# Mini_VFD_RevA.net
KiCad netlist of a schematic drawn in EAGLE
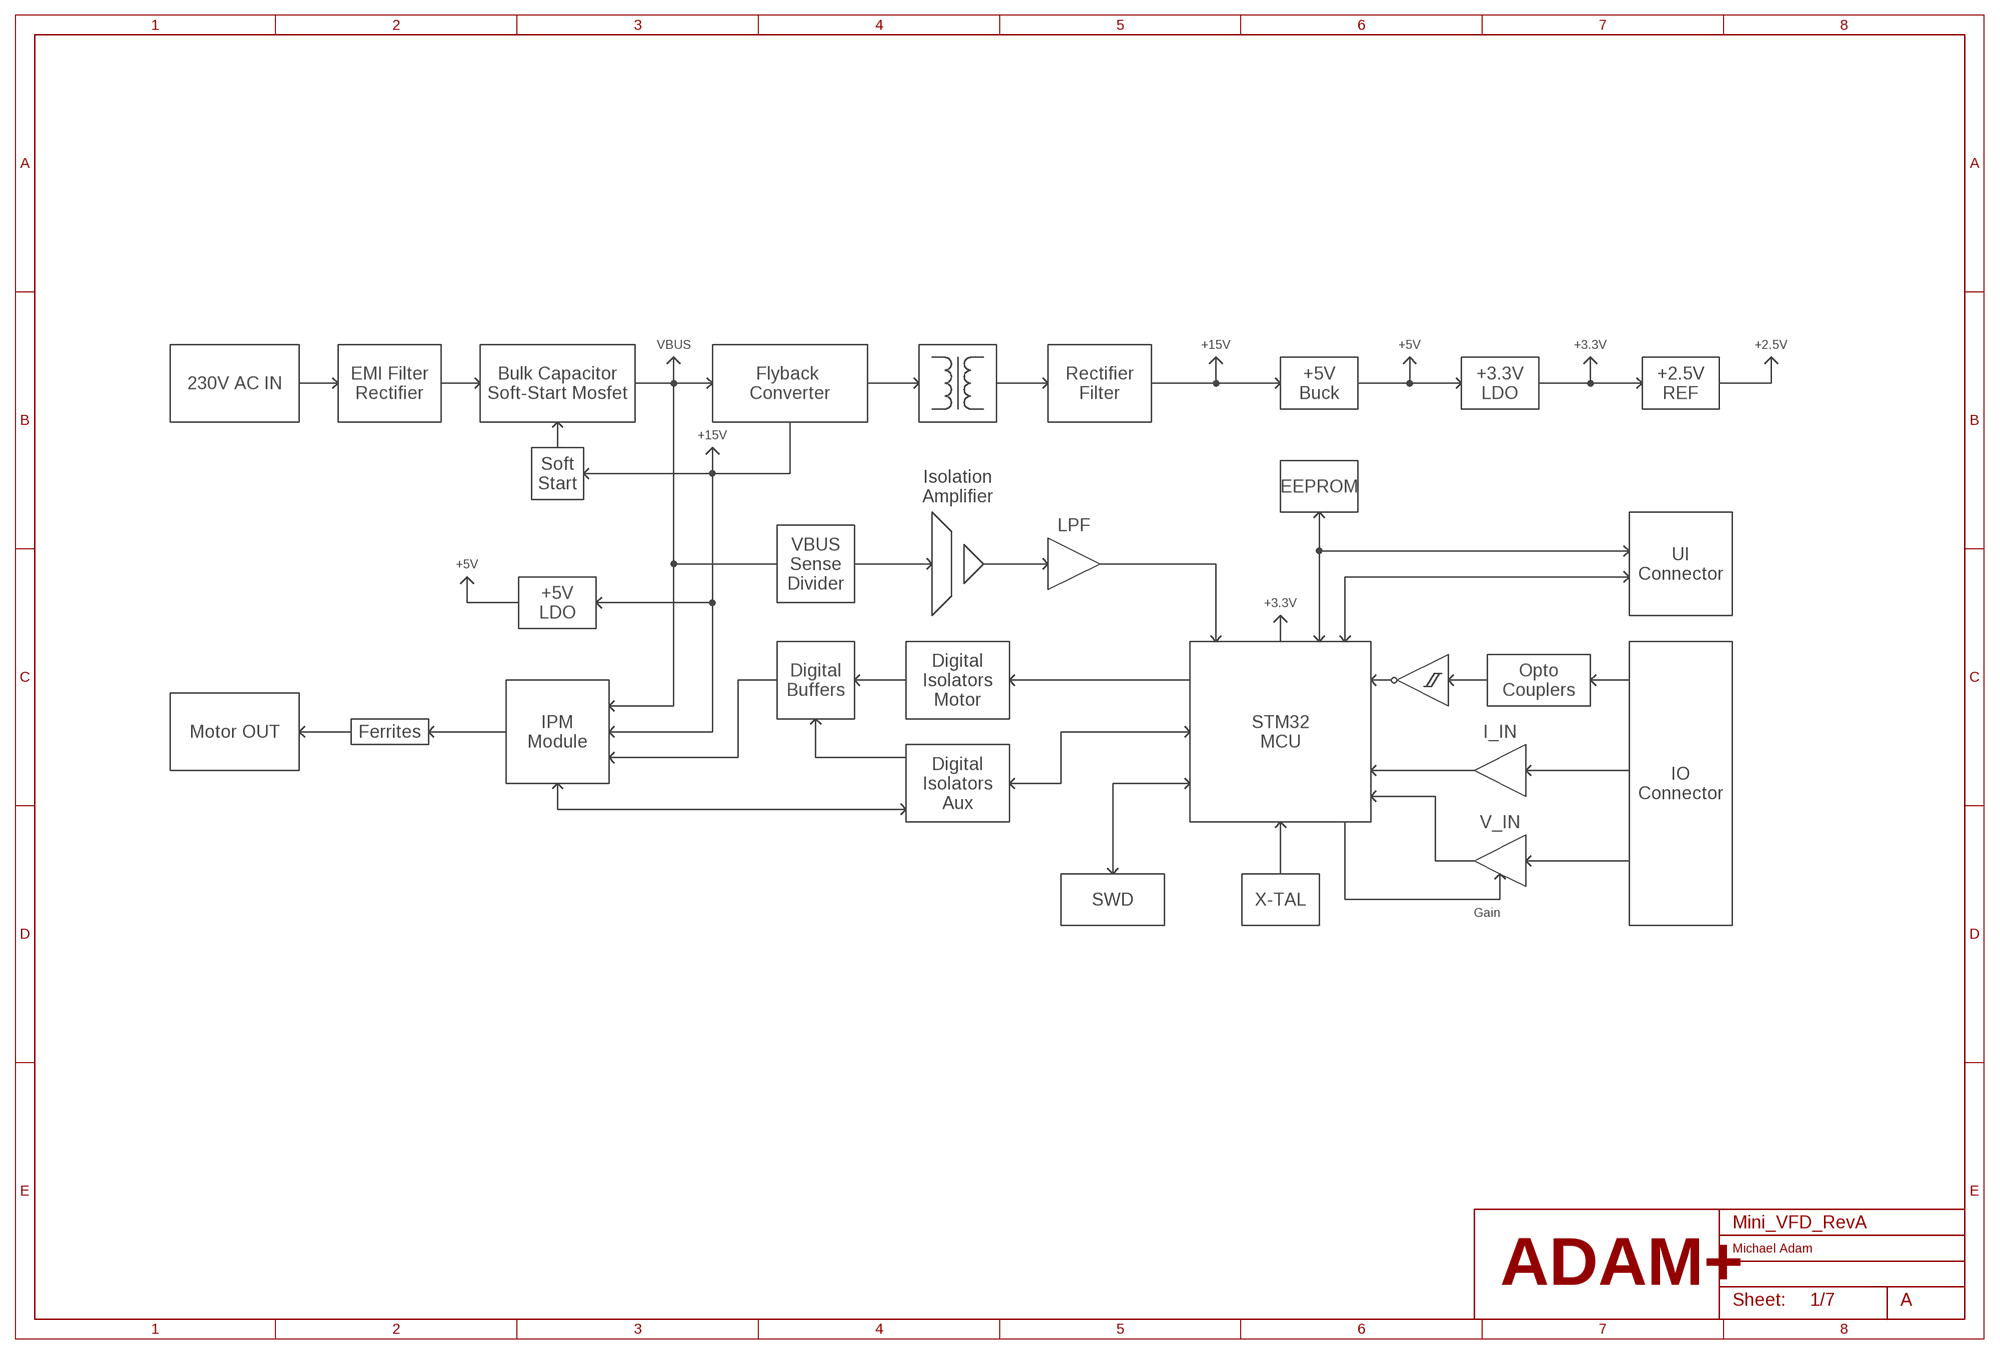
[diagram p0: schematic, sheet 1]
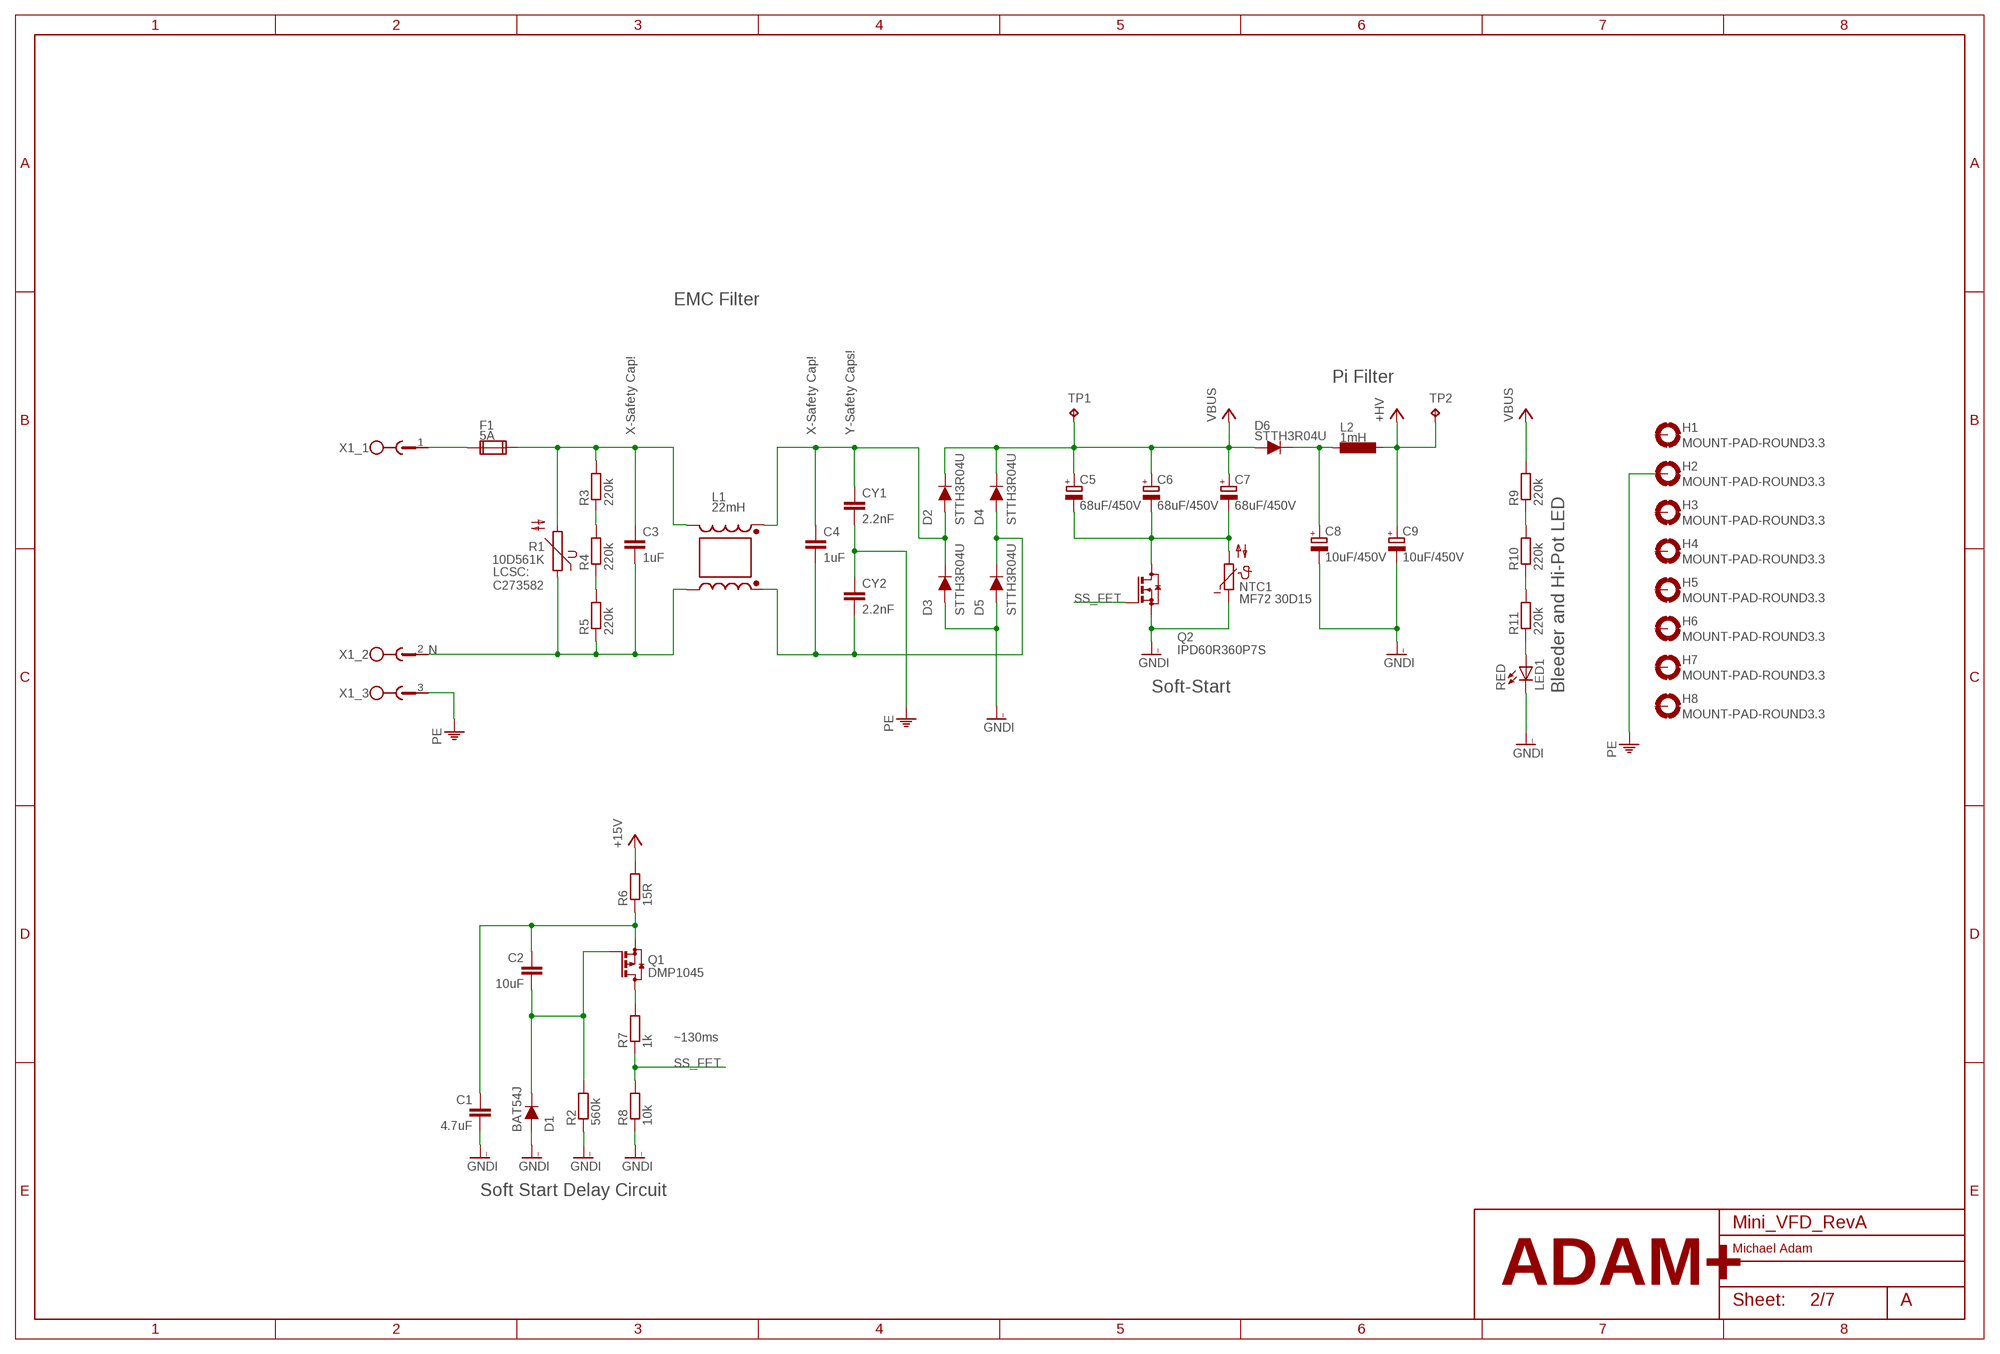
[diagram p1: schematic, sheet 2]
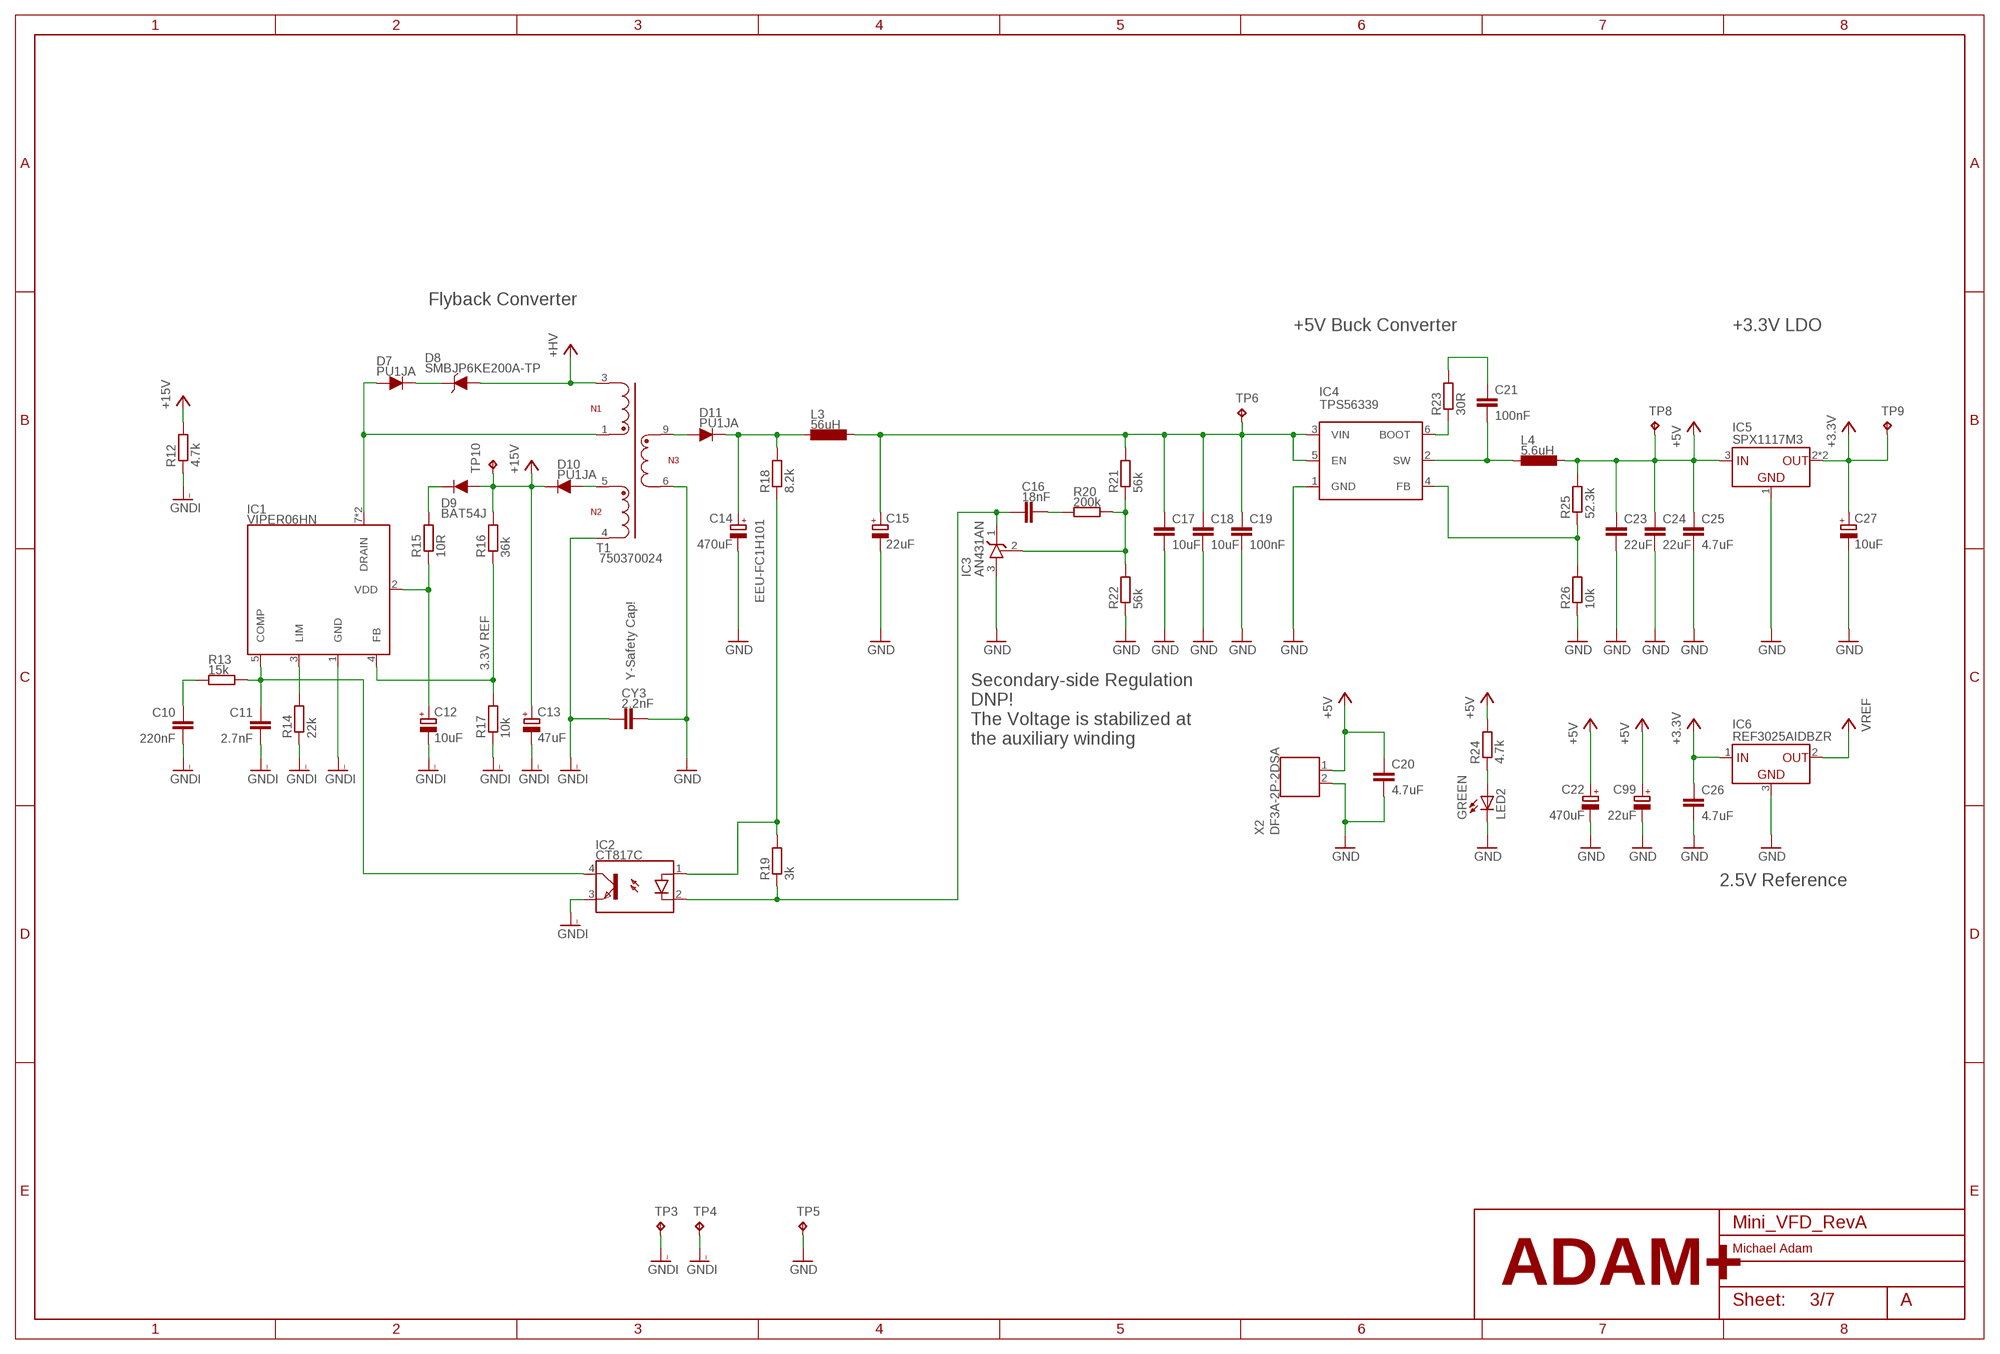
[diagram p2: schematic, sheet 3]
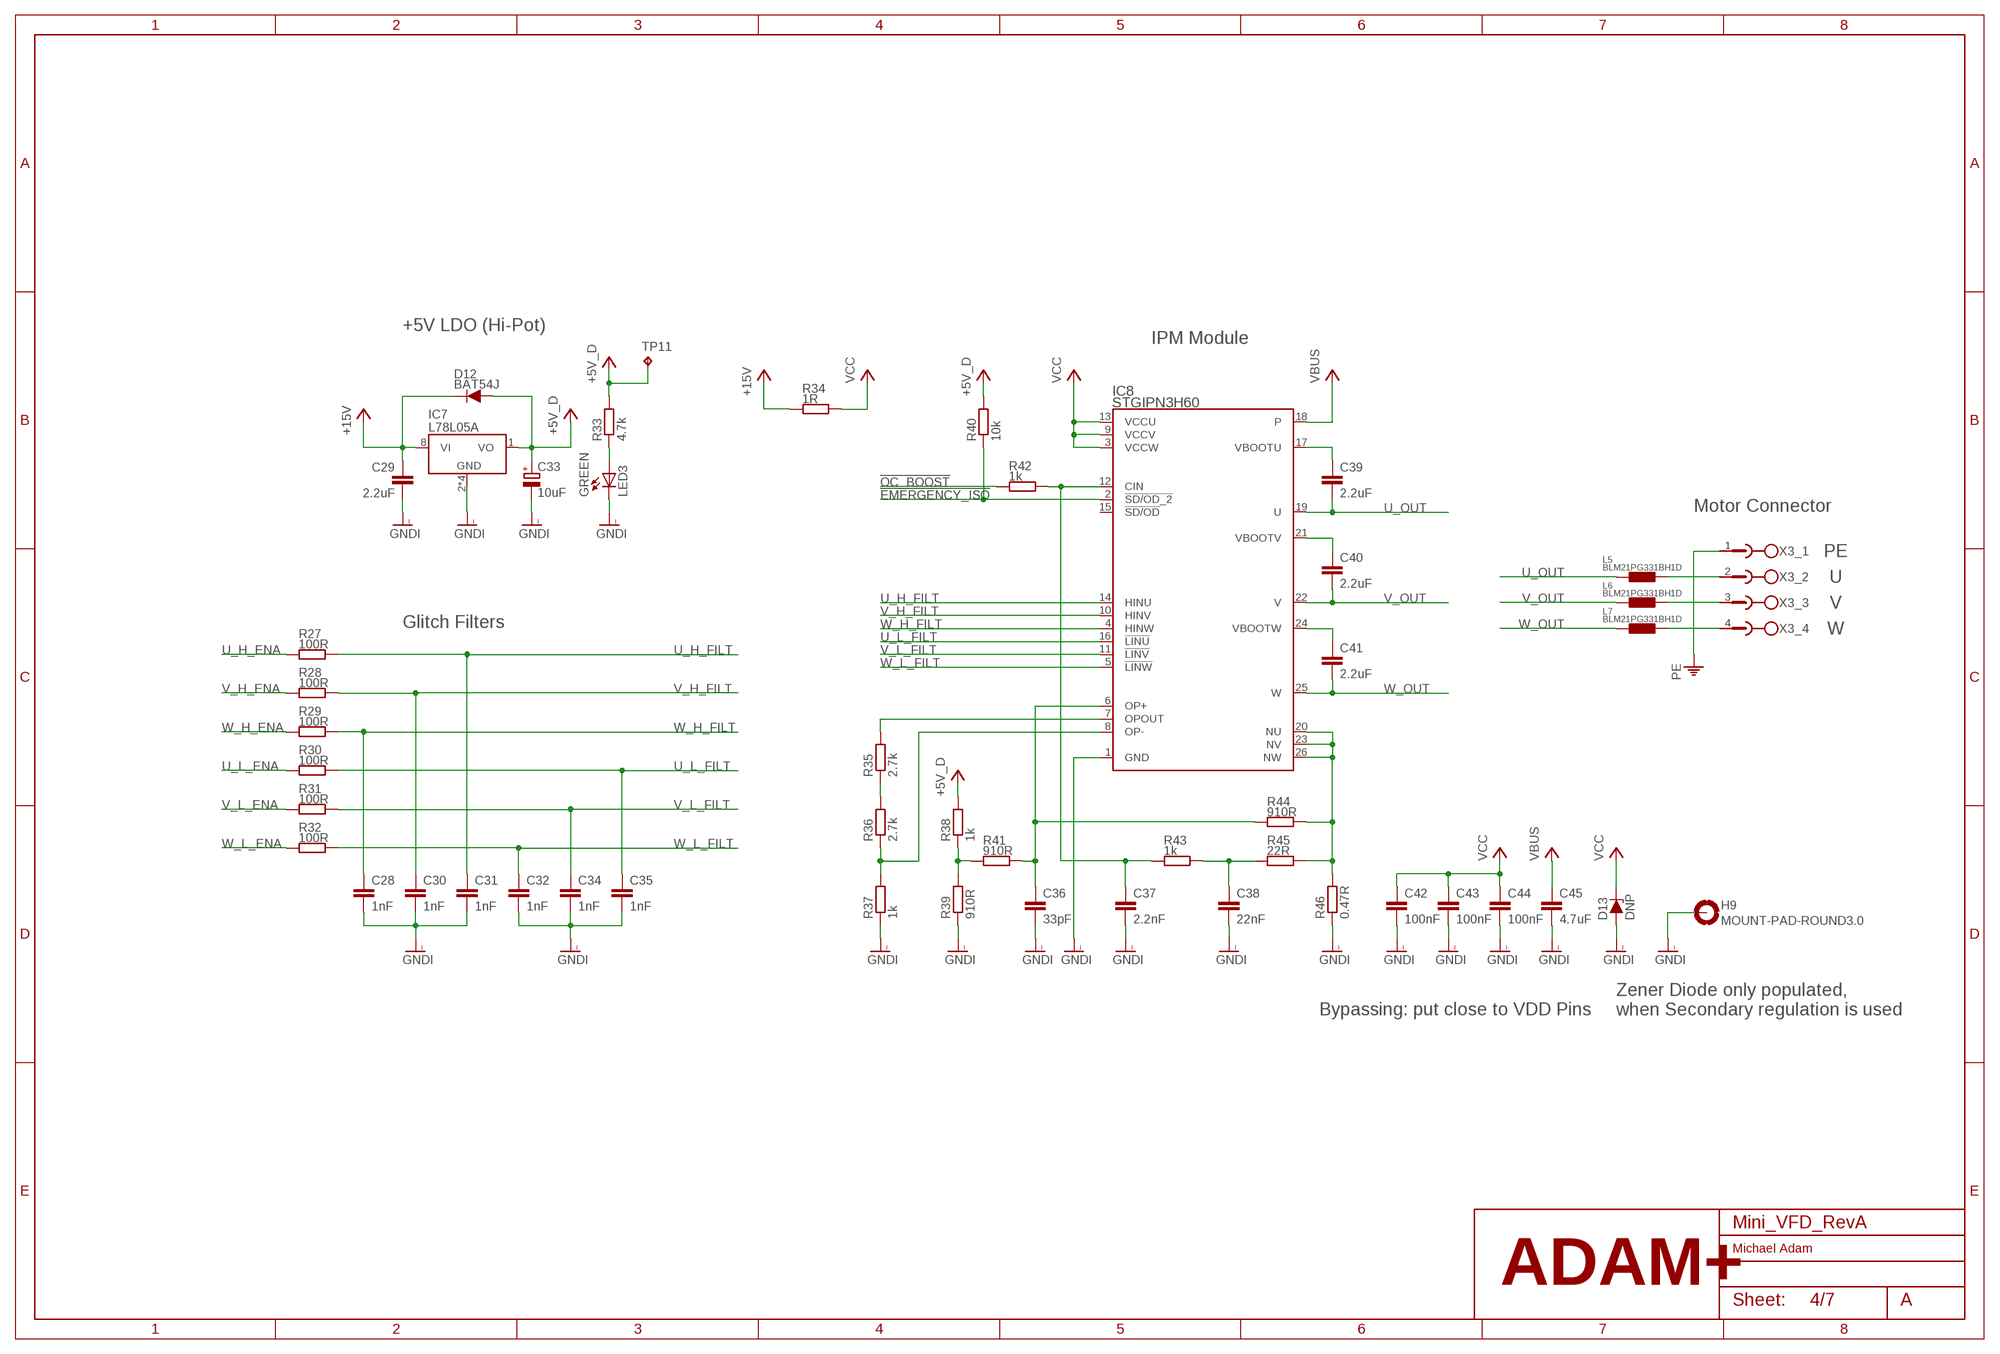
[diagram p3: schematic, sheet 4]
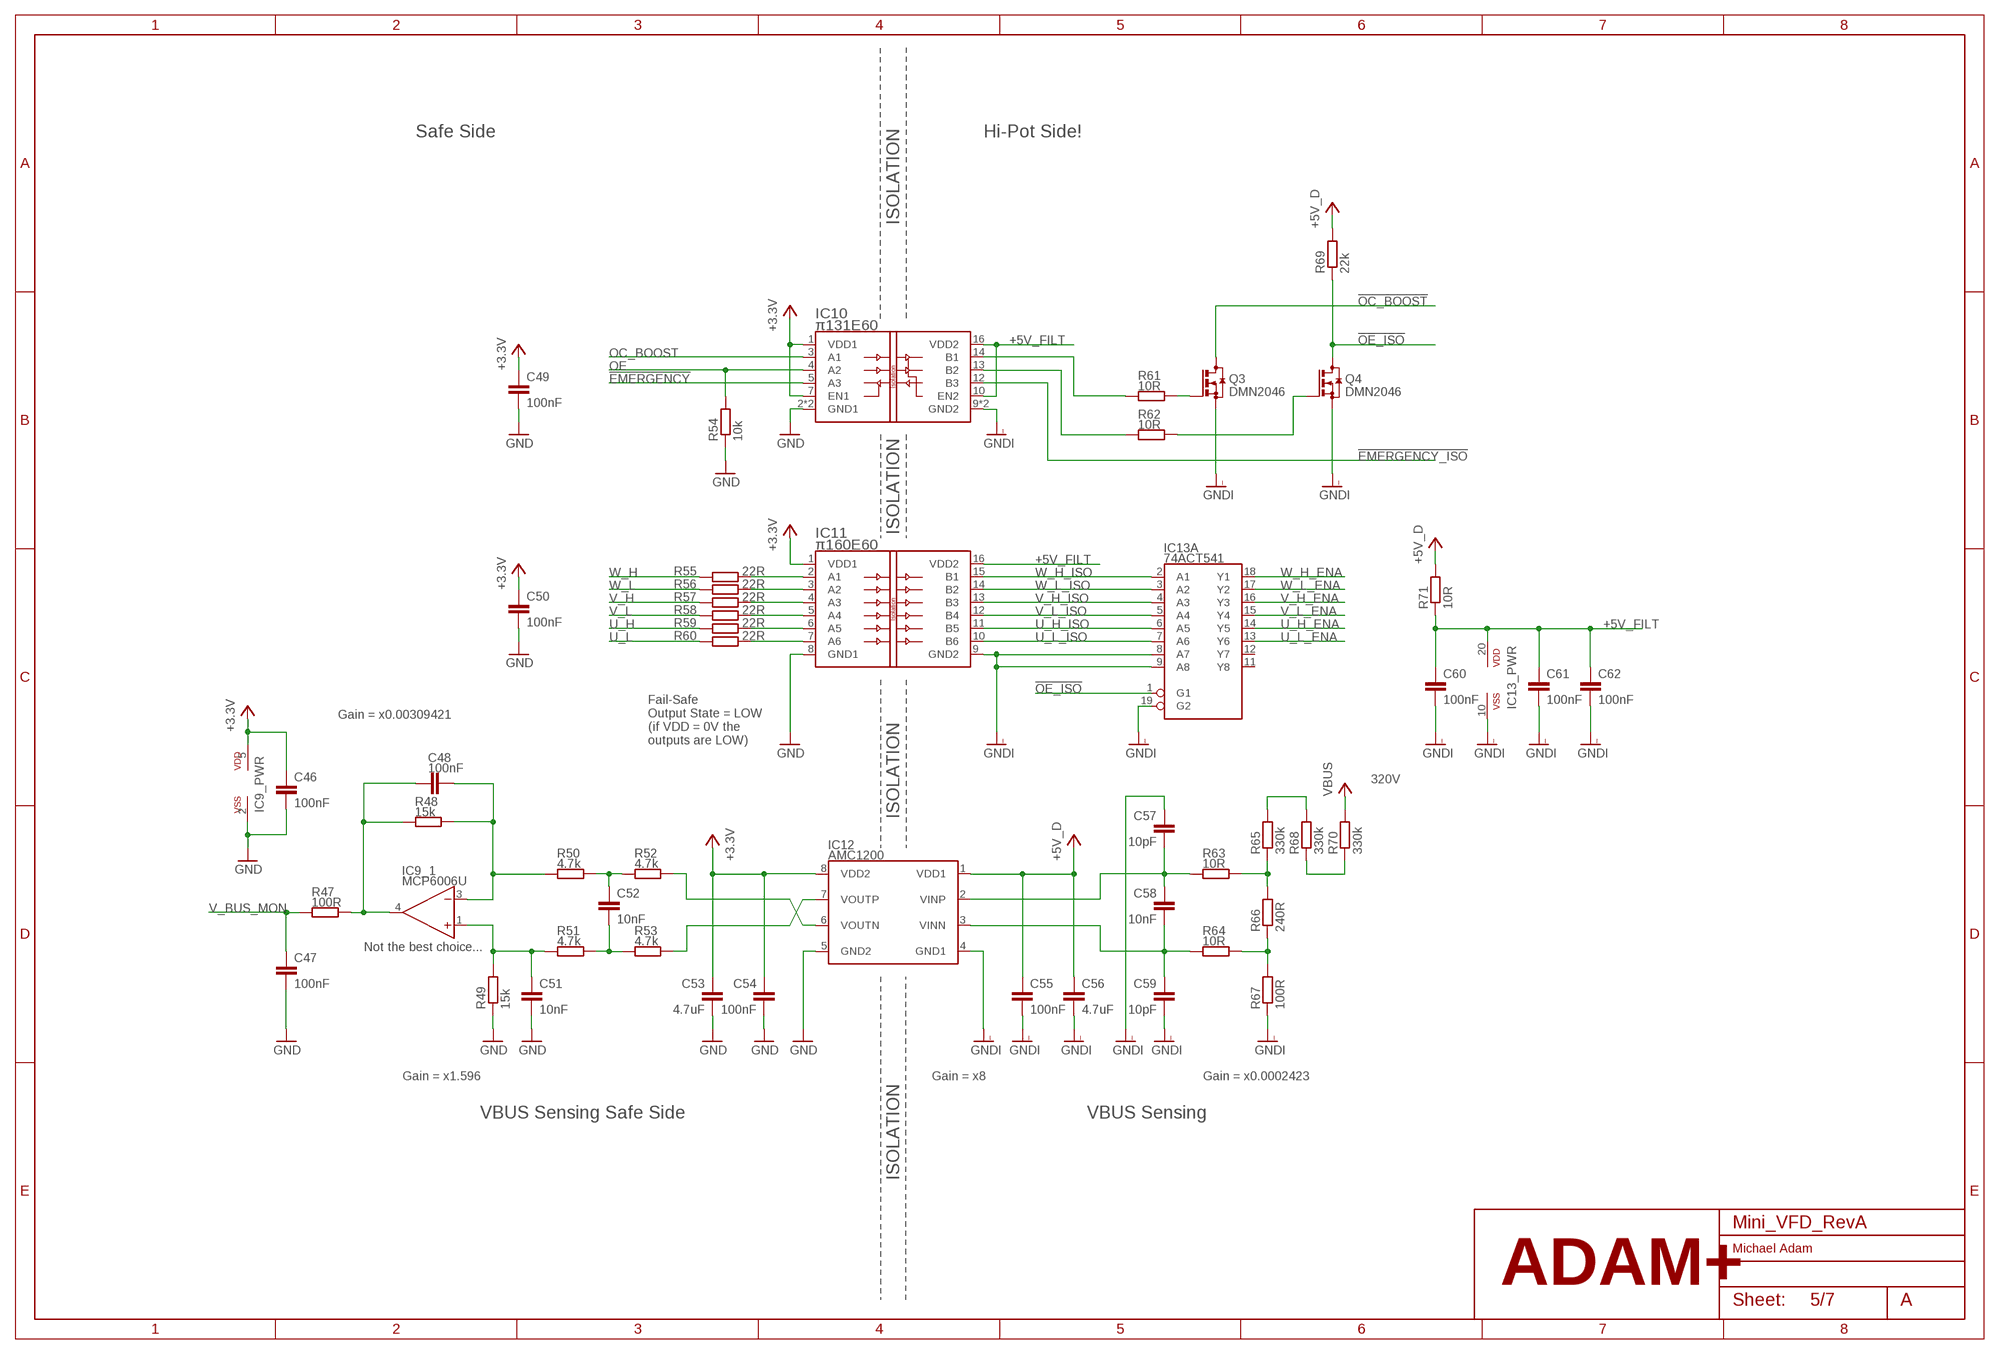
[diagram p4: schematic, sheet 5]
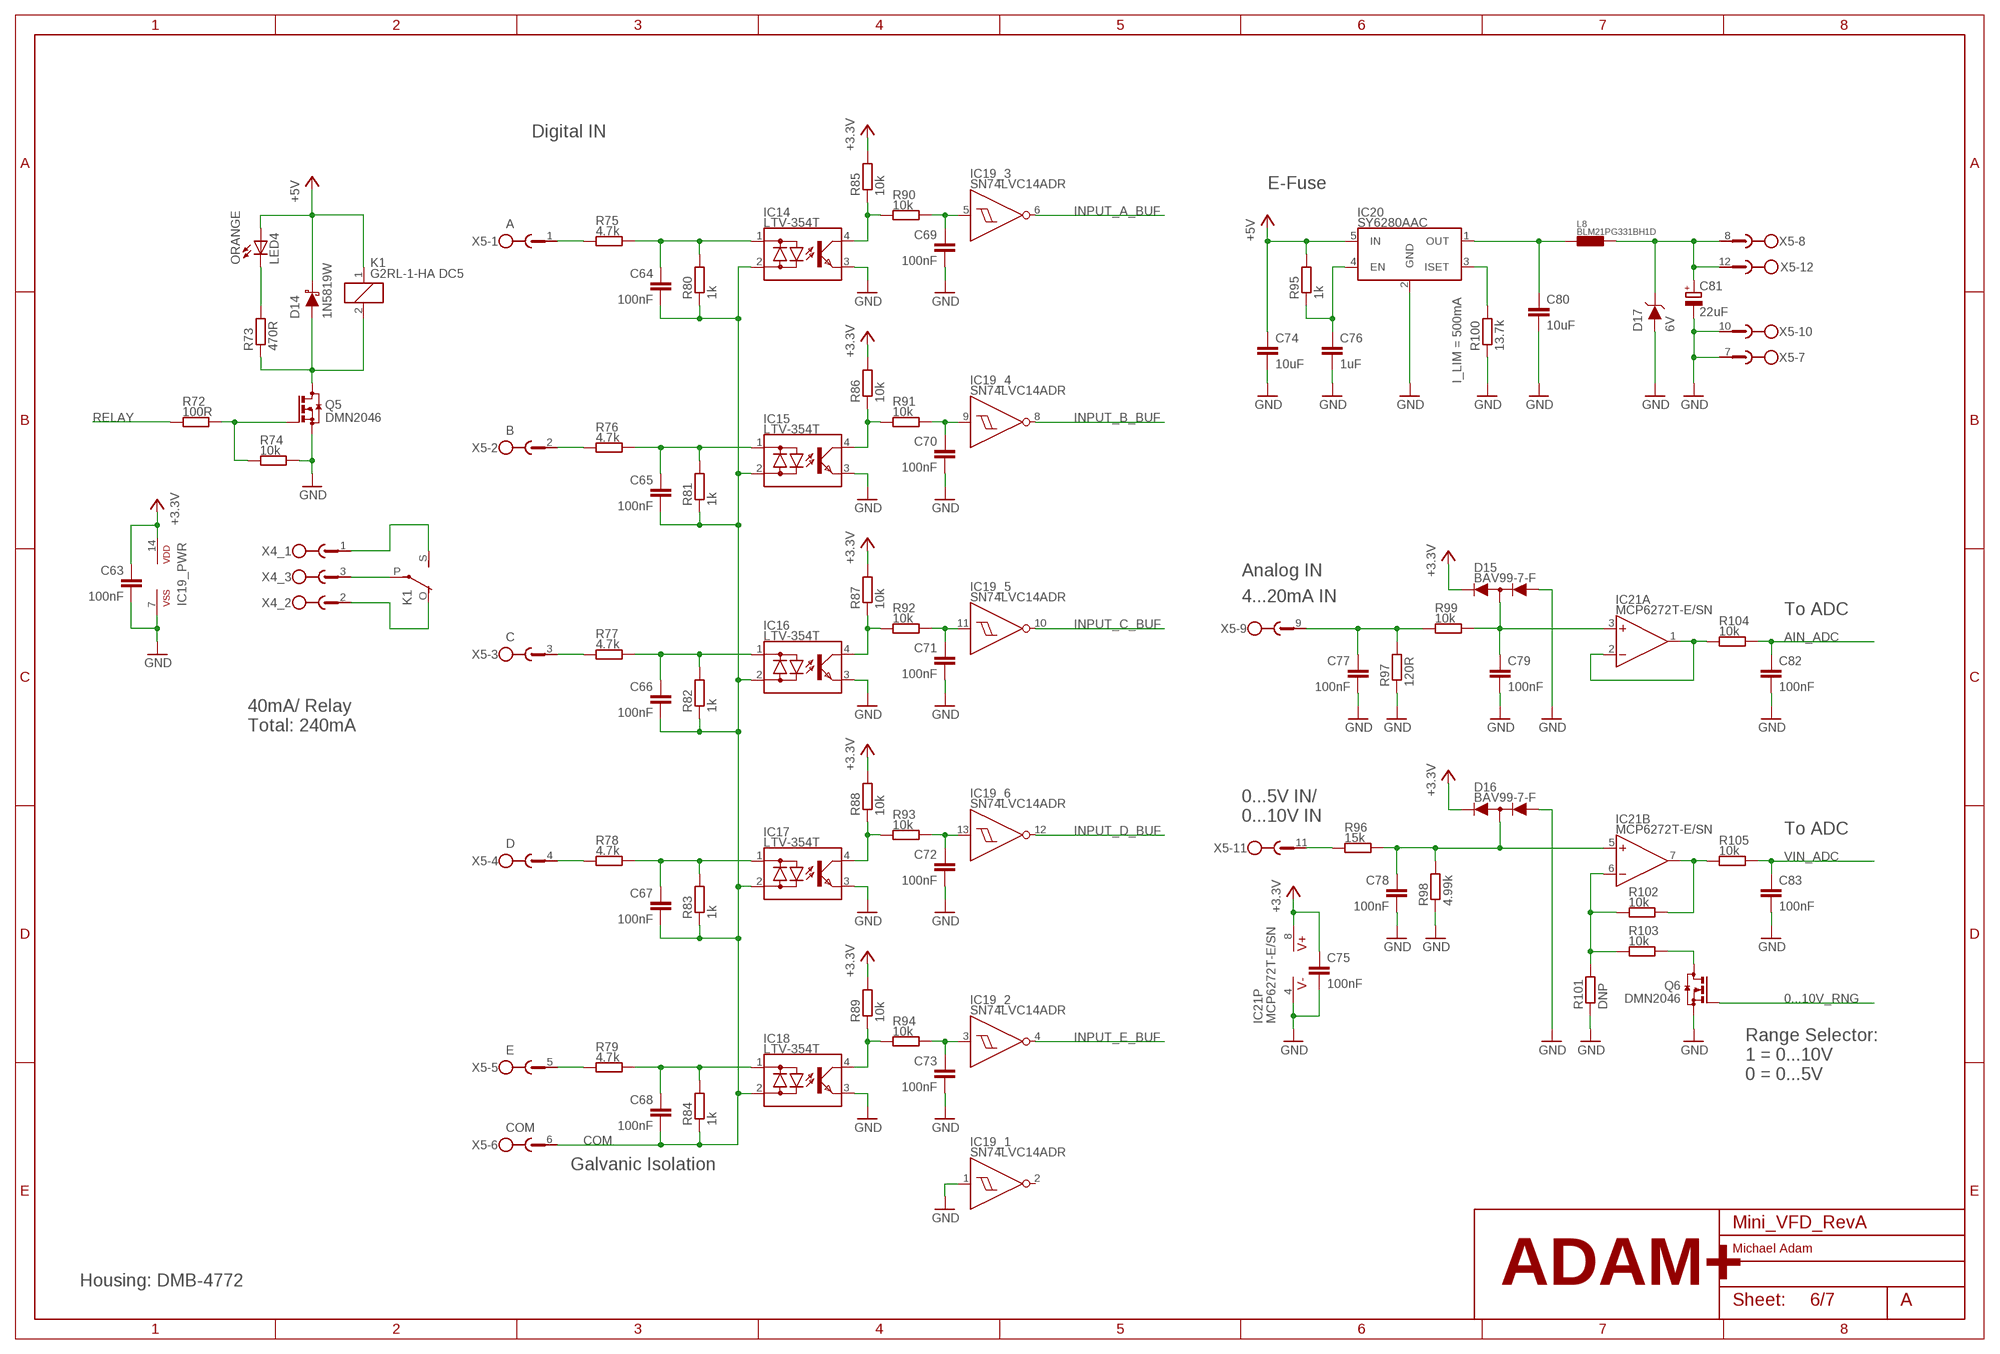
[diagram p5: schematic, sheet 6]
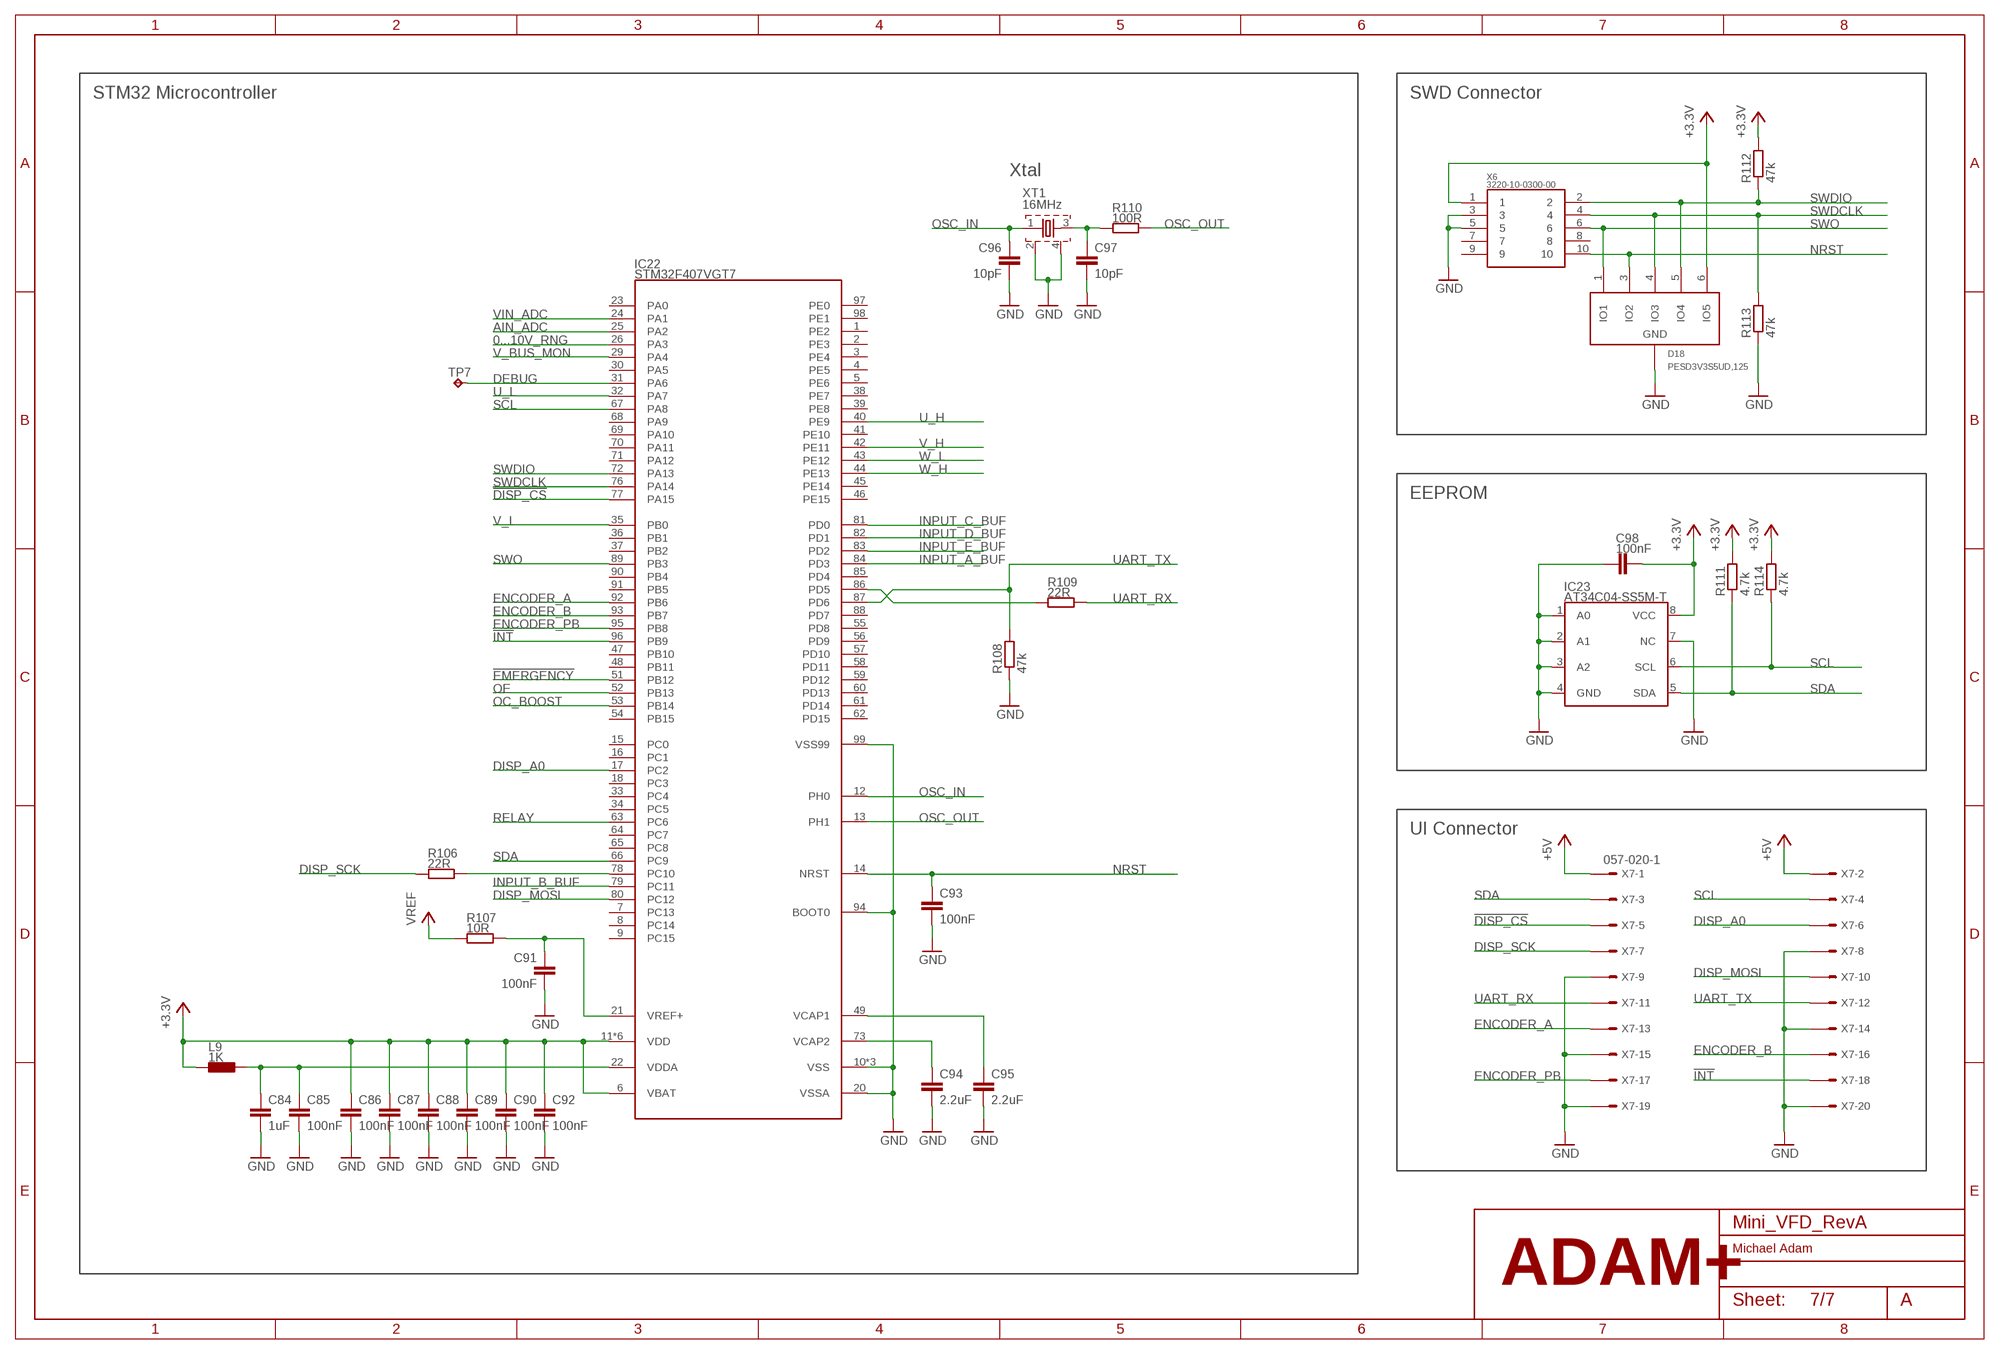
[diagram p6: schematic, sheet 7]

(export (version "E")
  (design (tool "Eeschema 10.0.6"))
  (components
    (comp (ref "C1")
      (value "4.7uF")
      (footprint "eagle-import:C0805")
      (libsource (lib "eagle-import") (part "C-EUC0805"))
    )
    (comp (ref "C2")
      (value "10uF")
      (footprint "eagle-import:C0805")
      (libsource (lib "eagle-import") (part "C-EUC0805"))
    )
    (comp (ref "C3")
      (value "1uF")
      (footprint "eagle-import:C102-082X133")
      (libsource (lib "eagle-import") (part "C-EU102-082X133"))
    )
    (comp (ref "C4")
      (value "1uF")
      (footprint "eagle-import:C102-082X133")
      (libsource (lib "eagle-import") (part "C-EU102-082X133"))
    )
    (comp (ref "C5")
      (value "68uF/450V")
      (footprint "eagle-import:E7,5-18")
      (libsource (lib "eagle-import") (part "CPOL-EUE7.5-18"))
    )
    (comp (ref "C6")
      (value "68uF/450V")
      (footprint "eagle-import:E7,5-18")
      (libsource (lib "eagle-import") (part "CPOL-EUE7.5-18"))
    )
    (comp (ref "C7")
      (value "68uF/450V")
      (footprint "eagle-import:E7,5-18")
      (libsource (lib "eagle-import") (part "CPOL-EUE7.5-18"))
    )
    (comp (ref "C8")
      (value "10uF/450V")
      (footprint "eagle-import:E5-10,5")
      (libsource (lib "eagle-import") (part "CPOL-EUE5-10.5"))
    )
    (comp (ref "C9")
      (value "10uF/450V")
      (footprint "eagle-import:E5-10,5")
      (libsource (lib "eagle-import") (part "CPOL-EUE5-10.5"))
    )
    (comp (ref "CY1")
      (value "2.2nF")
      (footprint "eagle-import:YC7B5")
      (libsource (lib "eagle-import") (part "CYYC7B5"))
    )
    (comp (ref "CY2")
      (value "2.2nF")
      (footprint "eagle-import:YC7B5")
      (libsource (lib "eagle-import") (part "CYYC7B5"))
    )
    (comp (ref "D1")
      (value "BAT54J")
      (footprint "eagle-import:SOD123")
      (libsource (lib "eagle-import") (part "DIODE"))
    )
    (comp (ref "D2")
      (value "STTH3R04U")
      (footprint "eagle-import:SMB")
      (libsource (lib "eagle-import") (part "DIODESMB"))
    )
    (comp (ref "D3")
      (value "STTH3R04U")
      (footprint "eagle-import:SMB")
      (libsource (lib "eagle-import") (part "DIODESMB"))
    )
    (comp (ref "D4")
      (value "STTH3R04U")
      (footprint "eagle-import:SMB")
      (libsource (lib "eagle-import") (part "DIODESMB"))
    )
    (comp (ref "D5")
      (value "STTH3R04U")
      (footprint "eagle-import:SMB")
      (libsource (lib "eagle-import") (part "DIODESMB"))
    )
    (comp (ref "D6")
      (value "STTH3R04U")
      (footprint "eagle-import:SMB")
      (libsource (lib "eagle-import") (part "DIODESMB"))
    )
    (comp (ref "F1")
      (value "5A")
      (footprint "eagle-import:SH25")
      (libsource (lib "eagle-import") (part "FUSESH25"))
    )
    (comp (ref "H1")
      (value "MOUNT-PAD-ROUND3.3")
      (footprint "eagle-import:3,3-PAD")
      (libsource (lib "eagle-import") (part "MOUNT-PAD-ROUND3.3"))
    )
    (comp (ref "H2")
      (value "MOUNT-PAD-ROUND3.3")
      (footprint "eagle-import:3,3-PAD")
      (libsource (lib "eagle-import") (part "MOUNT-PAD-ROUND3.3"))
    )
    (comp (ref "H3")
      (value "MOUNT-PAD-ROUND3.3")
      (footprint "eagle-import:3,3-PAD")
      (libsource (lib "eagle-import") (part "MOUNT-PAD-ROUND3.3"))
    )
    (comp (ref "H4")
      (value "MOUNT-PAD-ROUND3.3")
      (footprint "eagle-import:3,3-PAD")
      (libsource (lib "eagle-import") (part "MOUNT-PAD-ROUND3.3"))
    )
    (comp (ref "H5")
      (value "MOUNT-PAD-ROUND3.3")
      (footprint "eagle-import:3,3-PAD")
      (libsource (lib "eagle-import") (part "MOUNT-PAD-ROUND3.3"))
    )
    (comp (ref "H6")
      (value "MOUNT-PAD-ROUND3.3")
      (footprint "eagle-import:3,3-PAD")
      (libsource (lib "eagle-import") (part "MOUNT-PAD-ROUND3.3"))
    )
    (comp (ref "H7")
      (value "MOUNT-PAD-ROUND3.3")
      (footprint "eagle-import:3,3-PAD")
      (libsource (lib "eagle-import") (part "MOUNT-PAD-ROUND3.3"))
    )
    (comp (ref "H8")
      (value "MOUNT-PAD-ROUND3.3")
      (footprint "eagle-import:3,3-PAD")
      (libsource (lib "eagle-import") (part "MOUNT-PAD-ROUND3.3"))
    )
    (comp (ref "L1")
      (value "22mH")
      (footprint "eagle-import:CMC_PDMCAT18107")
      (libsource (lib "eagle-import") (part "COMMON_MODE_CHOKE_XRT16128B-223VFRL6"))
    )
    (comp (ref "L2")
      (value "1mH")
      (footprint "eagle-import:SLH0704")
      (libsource (lib "eagle-import") (part "COIL_1MH"))
    )
    (comp (ref "LED1")
      (value "RED")
      (footprint "eagle-import:LED_0805")
      (libsource (lib "eagle-import") (part "LED_0805"))
    )
    (comp (ref "NTC1")
      (value "MF72 30D15")
      (footprint "eagle-import:MF72")
      (libsource (lib "eagle-import") (part "NTC"))
    )
    (comp (ref "Q1")
      (value "DMP1045")
      (footprint "eagle-import:SOT23")
      (libsource (lib "eagle-import") (part "PMOS"))
    )
    (comp (ref "Q2")
      (value "IPD60R360P7S")
      (footprint "eagle-import:TO252")
      (libsource (lib "eagle-import") (part "NMOS_IPD60R360P7S"))
    )
    (comp (ref "R1")
      (value "10D561K")
      (footprint "eagle-import:S10K175")
      (libsource (lib "eagle-import") (part "S10K175"))
    )
    (comp (ref "R2")
      (value "560k")
      (footprint "eagle-import:R0603")
      (libsource (lib "eagle-import") (part "rcl_MICHAEL (1)_R-EU_R0603"))
    )
    (comp (ref "R3")
      (value "220k")
      (footprint "eagle-import:R1206")
      (libsource (lib "eagle-import") (part "R-EU_R1206"))
    )
    (comp (ref "R4")
      (value "220k")
      (footprint "eagle-import:R1206")
      (libsource (lib "eagle-import") (part "R-EU_R1206"))
    )
    (comp (ref "R5")
      (value "220k")
      (footprint "eagle-import:R1206")
      (libsource (lib "eagle-import") (part "R-EU_R1206"))
    )
    (comp (ref "R6")
      (value "15R")
      (footprint "eagle-import:0207_10")
      (libsource (lib "eagle-import") (part "R-EU_0207/10"))
    )
    (comp (ref "R7")
      (value "1k")
      (footprint "eagle-import:R0603")
      (libsource (lib "eagle-import") (part "rcl_MICHAEL (1)_R-EU_R0603"))
    )
    (comp (ref "R8")
      (value "10k")
      (footprint "eagle-import:R0603")
      (libsource (lib "eagle-import") (part "rcl_MICHAEL (1)_R-EU_R0603"))
    )
    (comp (ref "R9")
      (value "220k")
      (footprint "eagle-import:R1206")
      (libsource (lib "eagle-import") (part "R-EU_R1206"))
    )
    (comp (ref "R10")
      (value "220k")
      (footprint "eagle-import:R1206")
      (libsource (lib "eagle-import") (part "R-EU_R1206"))
    )
    (comp (ref "R11")
      (value "220k")
      (footprint "eagle-import:R1206")
      (libsource (lib "eagle-import") (part "R-EU_R1206"))
    )
    (comp (ref "TP1")
      (value "TPTP10R")
      (footprint "eagle-import:TP10R")
      (libsource (lib "eagle-import") (part "TPTP10R"))
    )
    (comp (ref "TP2")
      (value "TPTP10R")
      (footprint "eagle-import:TP10R")
      (libsource (lib "eagle-import") (part "TPTP10R"))
    )
    (comp (ref "X1")
      (value "MSTBV3")
      (footprint "eagle-import:MSTBV3")
      (libsource (lib "eagle-import") (part "MSTBV3"))
    )
    (comp (ref "C10")
      (value "220nF")
      (footprint "eagle-import:C0603")
      (libsource (lib "eagle-import") (part "C-EUC0603"))
    )
    (comp (ref "C11")
      (value "2.7nF")
      (footprint "eagle-import:C0603")
      (libsource (lib "eagle-import") (part "C-EUC0603"))
    )
    (comp (ref "C12")
      (value "10uF")
      (footprint "eagle-import:E2,5-5")
      (libsource (lib "eagle-import") (part "CPOL-EUE2.5-5"))
    )
    (comp (ref "C13")
      (value "47uF")
      (footprint "eagle-import:E2,5-7")
      (libsource (lib "eagle-import") (part "CPOL-EUE2.5-7"))
    )
    (comp (ref "C14")
      (value "470uF")
      (footprint "eagle-import:E5-10,5")
      (libsource (lib "eagle-import") (part "CPOL-EUE5-10.5"))
    )
    (comp (ref "C15")
      (value "22uF")
      (footprint "eagle-import:E2-5")
      (libsource (lib "eagle-import") (part "CPOL-EUE2-5"))
    )
    (comp (ref "C16")
      (value "18nF")
      (footprint "eagle-import:C0603")
      (libsource (lib "eagle-import") (part "C-EUC0603"))
    )
    (comp (ref "C17")
      (value "10uF")
      (footprint "eagle-import:C1206")
      (libsource (lib "eagle-import") (part "C-EUC1206"))
    )
    (comp (ref "C18")
      (value "10uF")
      (footprint "eagle-import:C1206")
      (libsource (lib "eagle-import") (part "C-EUC1206"))
    )
    (comp (ref "C19")
      (value "100nF")
      (footprint "eagle-import:C0603")
      (libsource (lib "eagle-import") (part "C-EUC0603"))
    )
    (comp (ref "C20")
      (value "4.7uF")
      (footprint "eagle-import:C0805")
      (libsource (lib "eagle-import") (part "C-EUC0805"))
    )
    (comp (ref "C21")
      (value "100nF")
      (footprint "eagle-import:C0603")
      (libsource (lib "eagle-import") (part "C-EUC0603"))
    )
    (comp (ref "C22")
      (value "470uF")
      (footprint "eagle-import:E5-10,5")
      (libsource (lib "eagle-import") (part "CPOL-EUE5-10.5"))
    )
    (comp (ref "C23")
      (value "22uF")
      (footprint "eagle-import:C1206")
      (libsource (lib "eagle-import") (part "C-EUC1206"))
    )
    (comp (ref "C24")
      (value "22uF")
      (footprint "eagle-import:C1206")
      (libsource (lib "eagle-import") (part "C-EUC1206"))
    )
    (comp (ref "C25")
      (value "4.7uF")
      (footprint "eagle-import:C0603")
      (libsource (lib "eagle-import") (part "C-EUC0603"))
    )
    (comp (ref "C26")
      (value "4.7uF")
      (footprint "eagle-import:C0603")
      (libsource (lib "eagle-import") (part "C-EUC0603"))
    )
    (comp (ref "C27")
      (value "10uF")
      (footprint "eagle-import:CT3528")
      (libsource (lib "eagle-import") (part "CPOL-EUCT3528"))
    )
    (comp (ref "C99")
      (value "22uF")
      (footprint "eagle-import:E2-5")
      (libsource (lib "eagle-import") (part "CPOL-EUE2-5"))
    )
    (comp (ref "CY3")
      (value "2.2nF")
      (footprint "eagle-import:YC7B5")
      (libsource (lib "eagle-import") (part "CYYC7B5"))
    )
    (comp (ref "D7")
      (value "PU1JA")
      (footprint "eagle-import:DO214AC")
      (libsource (lib "eagle-import") (part "DIODEDO214AC"))
    )
    (comp (ref "D8")
      (value "SMBJP6KE200A-TP")
      (footprint "eagle-import:SMB")
      (libsource (lib "eagle-import") (part "TVS_DIODE_UNISMB"))
    )
    (comp (ref "D9")
      (value "BAT54J")
      (footprint "eagle-import:SOD123")
      (libsource (lib "eagle-import") (part "DIODE"))
    )
    (comp (ref "D10")
      (value "PU1JA")
      (footprint "eagle-import:DO214AC")
      (libsource (lib "eagle-import") (part "DIODEDO214AC"))
    )
    (comp (ref "D11")
      (value "PU1JA")
      (footprint "eagle-import:DO214AC")
      (libsource (lib "eagle-import") (part "DIODEDO214AC"))
    )
    (comp (ref "IC1")
      (value "VIPER06HN")
      (footprint "eagle-import:DIL07")
      (libsource (lib "eagle-import") (part "VIPER06HN"))
    )
    (comp (ref "IC2")
      (value "CT817C")
      (footprint "eagle-import:SMD4")
      (libsource (lib "eagle-import") (part "CT817C"))
    )
    (comp (ref "IC3")
      (value "AN431AN")
      (footprint "eagle-import:SOT23")
      (libsource (lib "eagle-import") (part "431"))
    )
    (comp (ref "IC4")
      (value "TPS56339")
      (footprint "eagle-import:TSOT23-6")
      (libsource (lib "eagle-import") (part "TPS56339"))
    )
    (comp (ref "IC5")
      (value "SPX1117M3")
      (footprint "eagle-import:SOT223")
      (libsource (lib "eagle-import") (part "SPX1117_3V3"))
    )
    (comp (ref "IC6")
      (value "REF3025AIDBZR")
      (footprint "eagle-import:SOT23")
      (libsource (lib "eagle-import") (part "REF3025"))
    )
    (comp (ref "L3")
      (value "56uH")
      (footprint "eagle-import:PDPTAT")
      (libsource (lib "eagle-import") (part "COIL_56UH"))
    )
    (comp (ref "L4")
      (value "5.6uH")
      (footprint "eagle-import:DH0530H")
      (libsource (lib "eagle-import") (part "COIL_5R6"))
    )
    (comp (ref "LED2")
      (value "GREEN")
      (footprint "eagle-import:LED_0805")
      (libsource (lib "eagle-import") (part "LED_0805"))
    )
    (comp (ref "R12")
      (value "4.7k")
      (footprint "eagle-import:R1206")
      (libsource (lib "eagle-import") (part "R-EU_R1206"))
    )
    (comp (ref "R13")
      (value "15k")
      (footprint "eagle-import:R0603")
      (libsource (lib "eagle-import") (part "R-EU_R0603"))
    )
    (comp (ref "R14")
      (value "22k")
      (footprint "eagle-import:R0603")
      (libsource (lib "eagle-import") (part "R-EU_R0603"))
    )
    (comp (ref "R15")
      (value "10R")
      (footprint "eagle-import:R0805")
      (libsource (lib "eagle-import") (part "R-EU_R0805"))
    )
    (comp (ref "R16")
      (value "36k")
      (footprint "eagle-import:R0603")
      (libsource (lib "eagle-import") (part "R-EU_R0603"))
    )
    (comp (ref "R17")
      (value "10k")
      (footprint "eagle-import:R0603")
      (libsource (lib "eagle-import") (part "R-EU_R0603"))
    )
    (comp (ref "R18")
      (value "8.2k")
      (footprint "eagle-import:R0603")
      (libsource (lib "eagle-import") (part "R-EU_R0603"))
    )
    (comp (ref "R19")
      (value "3k")
      (footprint "eagle-import:R0603")
      (libsource (lib "eagle-import") (part "R-EU_R0603"))
    )
    (comp (ref "R20")
      (value "200k")
      (footprint "eagle-import:R0603")
      (libsource (lib "eagle-import") (part "R-EU_R0603"))
    )
    (comp (ref "R21")
      (value "56k")
      (footprint "eagle-import:R0603")
      (libsource (lib "eagle-import") (part "R-EU_R0603"))
    )
    (comp (ref "R22")
      (value "56k")
      (footprint "eagle-import:R0603")
      (libsource (lib "eagle-import") (part "R-EU_R0603"))
    )
    (comp (ref "R23")
      (value "30R")
      (footprint "eagle-import:R0603")
      (libsource (lib "eagle-import") (part "R-EU_R0603"))
    )
    (comp (ref "R24")
      (value "4.7k")
      (footprint "eagle-import:R0603")
      (libsource (lib "eagle-import") (part "R-EU_R0603"))
    )
    (comp (ref "R25")
      (value "52.3k")
      (footprint "eagle-import:R0603")
      (libsource (lib "eagle-import") (part "R-EU_R0603"))
    )
    (comp (ref "R26")
      (value "10k")
      (footprint "eagle-import:R0603")
      (libsource (lib "eagle-import") (part "R-EU_R0603"))
    )
    (comp (ref "T1")
      (value "750370024")
      (footprint "eagle-import:WE-OLSTM_EE13_L13.72W20.45H10.8")
      (libsource (lib "eagle-import") (part "750370024"))
    )
    (comp (ref "TP3")
      (value "TP_SOLDREYE")
      (footprint "eagle-import:SOLDER_EYE")
      (libsource (lib "eagle-import") (part "TP_SOLDREYE"))
    )
    (comp (ref "TP4")
      (value "TP_SOLDREYE")
      (footprint "eagle-import:SOLDER_EYE")
      (libsource (lib "eagle-import") (part "TP_SOLDREYE"))
    )
    (comp (ref "TP5")
      (value "TP_SOLDREYE")
      (footprint "eagle-import:SOLDER_EYE")
      (libsource (lib "eagle-import") (part "TP_SOLDREYE"))
    )
    (comp (ref "TP6")
      (value "TP_SOLDREYE")
      (footprint "eagle-import:SOLDER_EYE")
      (libsource (lib "eagle-import") (part "TP_SOLDREYE"))
    )
    (comp (ref "TP8")
      (value "TP_SOLDREYE")
      (footprint "eagle-import:SOLDER_EYE")
      (libsource (lib "eagle-import") (part "TP_SOLDREYE"))
    )
    (comp (ref "TP9")
      (value "TP_SOLDREYE")
      (footprint "eagle-import:SOLDER_EYE")
      (libsource (lib "eagle-import") (part "TP_SOLDREYE"))
    )
    (comp (ref "TP10")
      (value "TP_SOLDREYE")
      (footprint "eagle-import:SOLDER_EYE")
      (libsource (lib "eagle-import") (part "TP_SOLDREYE"))
    )
    (comp (ref "X2")
      (value "DF3A-2P-2DSA")
      (footprint "eagle-import:DF3A-2P-2DSA")
      (libsource (lib "eagle-import") (part "DF3E-2P-2V_THD"))
    )
    (comp (ref "C46")
      (value "100nF")
      (footprint "eagle-import:C0603")
      (libsource (lib "eagle-import") (part "C-EUC0603"))
    )
    (comp (ref "C47")
      (value "100nF")
      (footprint "eagle-import:C0603")
      (libsource (lib "eagle-import") (part "C-EUC0603"))
    )
    (comp (ref "C48")
      (value "100nF")
      (footprint "eagle-import:C0603")
      (libsource (lib "eagle-import") (part "C-EUC0603"))
    )
    (comp (ref "C49")
      (value "100nF")
      (footprint "eagle-import:C0603")
      (libsource (lib "eagle-import") (part "C-EUC0603"))
    )
    (comp (ref "C50")
      (value "100nF")
      (footprint "eagle-import:C0603")
      (libsource (lib "eagle-import") (part "C-EUC0603"))
    )
    (comp (ref "C51")
      (value "10nF")
      (footprint "eagle-import:C0603")
      (libsource (lib "eagle-import") (part "C-EUC0603"))
    )
    (comp (ref "C52")
      (value "10nF")
      (footprint "eagle-import:C0603")
      (libsource (lib "eagle-import") (part "C-EUC0603"))
    )
    (comp (ref "C53")
      (value "4.7uF")
      (footprint "eagle-import:C0603")
      (libsource (lib "eagle-import") (part "C-EUC0603"))
    )
    (comp (ref "C54")
      (value "100nF")
      (footprint "eagle-import:C0603")
      (libsource (lib "eagle-import") (part "C-EUC0603"))
    )
    (comp (ref "C55")
      (value "100nF")
      (footprint "eagle-import:C0603")
      (libsource (lib "eagle-import") (part "C-EUC0603"))
    )
    (comp (ref "C56")
      (value "4.7uF")
      (footprint "eagle-import:C0603")
      (libsource (lib "eagle-import") (part "C-EUC0603"))
    )
    (comp (ref "C57")
      (value "10pF")
      (footprint "eagle-import:C0603")
      (libsource (lib "eagle-import") (part "C-EUC0603"))
    )
    (comp (ref "C58")
      (value "10nF")
      (footprint "eagle-import:C0603")
      (libsource (lib "eagle-import") (part "C-EUC0603"))
    )
    (comp (ref "C59")
      (value "10pF")
      (footprint "eagle-import:C0603")
      (libsource (lib "eagle-import") (part "C-EUC0603"))
    )
    (comp (ref "C60")
      (value "100nF")
      (footprint "eagle-import:C0603")
      (libsource (lib "eagle-import") (part "C-EUC0603"))
    )
    (comp (ref "C61")
      (value "100nF")
      (footprint "eagle-import:C0603")
      (libsource (lib "eagle-import") (part "C-EUC0603"))
    )
    (comp (ref "C62")
      (value "100nF")
      (footprint "eagle-import:C0603")
      (libsource (lib "eagle-import") (part "C-EUC0603"))
    )
    (comp (ref "IC9")
      (value "MCP6006U")
      (footprint "eagle-import:SOT23-5")
      (libsource (lib "eagle-import") (part "LM321"))
    )
    (comp (ref "IC10")
      (value "π131E60")
      (footprint "eagle-import:SOIC16R")
      (libsource (lib "eagle-import") (part "π131E60"))
    )
    (comp (ref "IC11")
      (value "π160E60")
      (footprint "eagle-import:SOIC16R")
      (libsource (lib "eagle-import") (part "π160E60"))
    )
    (comp (ref "IC12")
      (value "AMC1200")
      (footprint "eagle-import:SOIC8_W")
      (libsource (lib "eagle-import") (part "AMC1200"))
    )
    (comp (ref "IC13")
      (value "74ACT541")
      (footprint "eagle-import:SOIC20NS")
      (libsource (lib "eagle-import") (part "74541"))
    )
    (comp (ref "Q3")
      (value "DMN2046")
      (footprint "eagle-import:SOT23")
      (libsource (lib "eagle-import") (part "NMOS_DMN2046"))
    )
    (comp (ref "Q4")
      (value "DMN2046")
      (footprint "eagle-import:SOT23")
      (libsource (lib "eagle-import") (part "NMOS_DMN2046"))
    )
    (comp (ref "R47")
      (value "100R")
      (footprint "eagle-import:R0603")
      (libsource (lib "eagle-import") (part "rcl_MICHAEL (1)_R-EU_R0603"))
    )
    (comp (ref "R48")
      (value "15k")
      (footprint "eagle-import:R0603")
      (libsource (lib "eagle-import") (part "rcl_MICHAEL (1)_R-EU_R0603"))
    )
    (comp (ref "R49")
      (value "15k")
      (footprint "eagle-import:R0603")
      (libsource (lib "eagle-import") (part "rcl_MICHAEL (1)_R-EU_R0603"))
    )
    (comp (ref "R50")
      (value "4.7k")
      (footprint "eagle-import:R0603")
      (libsource (lib "eagle-import") (part "rcl_MICHAEL (1)_R-EU_R0603"))
    )
    (comp (ref "R51")
      (value "4.7k")
      (footprint "eagle-import:R0603")
      (libsource (lib "eagle-import") (part "rcl_MICHAEL (1)_R-EU_R0603"))
    )
    (comp (ref "R52")
      (value "4.7k")
      (footprint "eagle-import:R0603")
      (libsource (lib "eagle-import") (part "rcl_MICHAEL (1)_R-EU_R0603"))
    )
    (comp (ref "R53")
      (value "4.7k")
      (footprint "eagle-import:R0603")
      (libsource (lib "eagle-import") (part "rcl_MICHAEL (1)_R-EU_R0603"))
    )
    (comp (ref "R54")
      (value "10k")
      (footprint "eagle-import:R0603")
      (libsource (lib "eagle-import") (part "rcl_MICHAEL (1)_R-EU_R0603"))
    )
    (comp (ref "R55")
      (value "22R")
      (footprint "eagle-import:R0603")
      (libsource (lib "eagle-import") (part "rcl_MICHAEL (1)_R-EU_R0603"))
    )
    (comp (ref "R56")
      (value "22R")
      (footprint "eagle-import:R0603")
      (libsource (lib "eagle-import") (part "rcl_MICHAEL (1)_R-EU_R0603"))
    )
    (comp (ref "R57")
      (value "22R")
      (footprint "eagle-import:R0603")
      (libsource (lib "eagle-import") (part "rcl_MICHAEL (1)_R-EU_R0603"))
    )
    (comp (ref "R58")
      (value "22R")
      (footprint "eagle-import:R0603")
      (libsource (lib "eagle-import") (part "rcl_MICHAEL (1)_R-EU_R0603"))
    )
    (comp (ref "R59")
      (value "22R")
      (footprint "eagle-import:R0603")
      (libsource (lib "eagle-import") (part "rcl_MICHAEL (1)_R-EU_R0603"))
    )
    (comp (ref "R60")
      (value "22R")
      (footprint "eagle-import:R0603")
      (libsource (lib "eagle-import") (part "rcl_MICHAEL (1)_R-EU_R0603"))
    )
    (comp (ref "R61")
      (value "10R")
      (footprint "eagle-import:R0603")
      (libsource (lib "eagle-import") (part "rcl_MICHAEL (1)_R-EU_R0603"))
    )
    (comp (ref "R62")
      (value "10R")
      (footprint "eagle-import:R0603")
      (libsource (lib "eagle-import") (part "rcl_MICHAEL (1)_R-EU_R0603"))
    )
    (comp (ref "R63")
      (value "10R")
      (footprint "eagle-import:R0603")
      (libsource (lib "eagle-import") (part "rcl_MICHAEL (1)_R-EU_R0603"))
    )
    (comp (ref "R64")
      (value "10R")
      (footprint "eagle-import:R0603")
      (libsource (lib "eagle-import") (part "rcl_MICHAEL (1)_R-EU_R0603"))
    )
    (comp (ref "R65")
      (value "330k")
      (footprint "eagle-import:R1206")
      (libsource (lib "eagle-import") (part "R-EU_R1206"))
    )
    (comp (ref "R66")
      (value "240R")
      (footprint "eagle-import:R0603")
      (libsource (lib "eagle-import") (part "rcl_MICHAEL (1)_R-EU_R0603"))
    )
    (comp (ref "R67")
      (value "100R")
      (footprint "eagle-import:R0603")
      (libsource (lib "eagle-import") (part "rcl_MICHAEL (1)_R-EU_R0603"))
    )
    (comp (ref "R68")
      (value "330k")
      (footprint "eagle-import:R1206")
      (libsource (lib "eagle-import") (part "R-EU_R1206"))
    )
    (comp (ref "R69")
      (value "22k")
      (footprint "eagle-import:R0603")
      (libsource (lib "eagle-import") (part "rcl_MICHAEL (1)_R-EU_R0603"))
    )
    (comp (ref "R70")
      (value "330k")
      (footprint "eagle-import:R1206")
      (libsource (lib "eagle-import") (part "R-EU_R1206"))
    )
    (comp (ref "R71")
      (value "10R")
      (footprint "eagle-import:R0603")
      (libsource (lib "eagle-import") (part "rcl_MICHAEL (1)_R-EU_R0603"))
    )
    (comp (ref "C28")
      (value "1nF")
      (footprint "eagle-import:C0603")
      (libsource (lib "eagle-import") (part "C-EUC0603"))
    )
    (comp (ref "C29")
      (value "2.2uF")
      (footprint "eagle-import:C0805")
      (libsource (lib "eagle-import") (part "C-EUC0805"))
    )
    (comp (ref "C30")
      (value "1nF")
      (footprint "eagle-import:C0603")
      (libsource (lib "eagle-import") (part "C-EUC0603"))
    )
    (comp (ref "C31")
      (value "1nF")
      (footprint "eagle-import:C0603")
      (libsource (lib "eagle-import") (part "C-EUC0603"))
    )
    (comp (ref "C32")
      (value "1nF")
      (footprint "eagle-import:C0603")
      (libsource (lib "eagle-import") (part "C-EUC0603"))
    )
    (comp (ref "C33")
      (value "10uF")
      (footprint "eagle-import:CT3528")
      (libsource (lib "eagle-import") (part "CPOL-EUCT3528"))
    )
    (comp (ref "C34")
      (value "1nF")
      (footprint "eagle-import:C0603")
      (libsource (lib "eagle-import") (part "C-EUC0603"))
    )
    (comp (ref "C35")
      (value "1nF")
      (footprint "eagle-import:C0603")
      (libsource (lib "eagle-import") (part "C-EUC0603"))
    )
    (comp (ref "C36")
      (value "33pF")
      (footprint "eagle-import:C0603")
      (libsource (lib "eagle-import") (part "C-EUC0603"))
    )
    (comp (ref "C37")
      (value "2.2nF")
      (footprint "eagle-import:C0603")
      (libsource (lib "eagle-import") (part "C-EUC0603"))
    )
    (comp (ref "C38")
      (value "22nF")
      (footprint "eagle-import:C0603")
      (libsource (lib "eagle-import") (part "C-EUC0603"))
    )
    (comp (ref "C39")
      (value "2.2uF")
      (footprint "eagle-import:C0805")
      (libsource (lib "eagle-import") (part "C-EUC0805"))
    )
    (comp (ref "C40")
      (value "2.2uF")
      (footprint "eagle-import:C0805")
      (libsource (lib "eagle-import") (part "C-EUC0805"))
    )
    (comp (ref "C41")
      (value "2.2uF")
      (footprint "eagle-import:C0805")
      (libsource (lib "eagle-import") (part "C-EUC0805"))
    )
    (comp (ref "C42")
      (value "100nF")
      (footprint "eagle-import:C0603")
      (libsource (lib "eagle-import") (part "C-EUC0603"))
    )
    (comp (ref "C43")
      (value "100nF")
      (footprint "eagle-import:C0603")
      (libsource (lib "eagle-import") (part "C-EUC0603"))
    )
    (comp (ref "C44")
      (value "100nF")
      (footprint "eagle-import:C0603")
      (libsource (lib "eagle-import") (part "C-EUC0603"))
    )
    (comp (ref "C45")
      (value "4.7uF")
      (footprint "eagle-import:C275-126X316")
      (libsource (lib "eagle-import") (part "C-EU275-126X316"))
    )
    (comp (ref "D12")
      (value "BAT54J")
      (footprint "eagle-import:SOD123")
      (libsource (lib "eagle-import") (part "DIODE"))
    )
    (comp (ref "D13")
      (value "DNP")
      (footprint "eagle-import:DO214AC")
      (libsource (lib "eagle-import") (part "ZENERSMA"))
    )
    (comp (ref "H9")
      (value "MOUNT-PAD-ROUND3.0")
      (footprint "eagle-import:3,0-PAD")
      (libsource (lib "eagle-import") (part "MOUNT-PAD-ROUND3.0"))
    )
    (comp (ref "IC7")
      (value "L78L05A")
      (footprint "eagle-import:SOIC8")
      (libsource (lib "eagle-import") (part "78L05"))
    )
    (comp (ref "IC8")
      (value "STGIPN3H60")
      (footprint "eagle-import:NDIP26_12P45X29P25_STM")
      (libsource (lib "eagle-import") (part "STGIPN3H60"))
    )
    (comp (ref "L5")
      (value "BLM21PG331BH1D")
      (footprint "eagle-import:R0805")
      (libsource (lib "eagle-import") (part "BEAD0805"))
    )
    (comp (ref "L6")
      (value "BLM21PG331BH1D")
      (footprint "eagle-import:R0805")
      (libsource (lib "eagle-import") (part "BEAD0805"))
    )
    (comp (ref "L7")
      (value "BLM21PG331BH1D")
      (footprint "eagle-import:R0805")
      (libsource (lib "eagle-import") (part "BEAD0805"))
    )
    (comp (ref "LED3")
      (value "GREEN")
      (footprint "eagle-import:LED_0805")
      (libsource (lib "eagle-import") (part "LED_0805"))
    )
    (comp (ref "R27")
      (value "100R")
      (footprint "eagle-import:R0603")
      (libsource (lib "eagle-import") (part "rcl_MICHAEL (1)_R-EU_R0603"))
    )
    (comp (ref "R28")
      (value "100R")
      (footprint "eagle-import:R0603")
      (libsource (lib "eagle-import") (part "rcl_MICHAEL (1)_R-EU_R0603"))
    )
    (comp (ref "R29")
      (value "100R")
      (footprint "eagle-import:R0603")
      (libsource (lib "eagle-import") (part "rcl_MICHAEL (1)_R-EU_R0603"))
    )
    (comp (ref "R30")
      (value "100R")
      (footprint "eagle-import:R0603")
      (libsource (lib "eagle-import") (part "rcl_MICHAEL (1)_R-EU_R0603"))
    )
    (comp (ref "R31")
      (value "100R")
      (footprint "eagle-import:R0603")
      (libsource (lib "eagle-import") (part "rcl_MICHAEL (1)_R-EU_R0603"))
    )
    (comp (ref "R32")
      (value "100R")
      (footprint "eagle-import:R0603")
      (libsource (lib "eagle-import") (part "rcl_MICHAEL (1)_R-EU_R0603"))
    )
    (comp (ref "R33")
      (value "4.7k")
      (footprint "eagle-import:R0603")
      (libsource (lib "eagle-import") (part "R-EU_R0603"))
    )
    (comp (ref "R34")
      (value "1R")
      (footprint "eagle-import:R0805")
      (libsource (lib "eagle-import") (part "R-EU_R0805"))
    )
    (comp (ref "R35")
      (value "2.7k")
      (footprint "eagle-import:R0603")
      (libsource (lib "eagle-import") (part "rcl_MICHAEL (1)_R-EU_R0603"))
    )
    (comp (ref "R36")
      (value "2.7k")
      (footprint "eagle-import:R0603")
      (libsource (lib "eagle-import") (part "rcl_MICHAEL (1)_R-EU_R0603"))
    )
    (comp (ref "R37")
      (value "1k")
      (footprint "eagle-import:R0603")
      (libsource (lib "eagle-import") (part "rcl_MICHAEL (1)_R-EU_R0603"))
    )
    (comp (ref "R38")
      (value "1k")
      (footprint "eagle-import:R0603")
      (libsource (lib "eagle-import") (part "rcl_MICHAEL (1)_R-EU_R0603"))
    )
    (comp (ref "R39")
      (value "910R")
      (footprint "eagle-import:R0603")
      (libsource (lib "eagle-import") (part "rcl_MICHAEL (1)_R-EU_R0603"))
    )
    (comp (ref "R40")
      (value "10k")
      (footprint "eagle-import:R0603")
      (libsource (lib "eagle-import") (part "rcl_MICHAEL (1)_R-EU_R0603"))
    )
    (comp (ref "R41")
      (value "910R")
      (footprint "eagle-import:R0603")
      (libsource (lib "eagle-import") (part "rcl_MICHAEL (1)_R-EU_R0603"))
    )
    (comp (ref "R42")
      (value "1k")
      (footprint "eagle-import:R0603")
      (libsource (lib "eagle-import") (part "rcl_MICHAEL (1)_R-EU_R0603"))
    )
    (comp (ref "R43")
      (value "1k")
      (footprint "eagle-import:R0603")
      (libsource (lib "eagle-import") (part "rcl_MICHAEL (1)_R-EU_R0603"))
    )
    (comp (ref "R44")
      (value "910R")
      (footprint "eagle-import:R0603")
      (libsource (lib "eagle-import") (part "rcl_MICHAEL (1)_R-EU_R0603"))
    )
    (comp (ref "R45")
      (value "22R")
      (footprint "eagle-import:R0603")
      (libsource (lib "eagle-import") (part "rcl_MICHAEL (1)_R-EU_R0603"))
    )
    (comp (ref "R46")
      (value "0.47R")
      (footprint "eagle-import:R2512")
      (libsource (lib "eagle-import") (part "R-EU_R2512"))
    )
    (comp (ref "TP11")
      (value "TP_SOLDREYE")
      (footprint "eagle-import:SOLDER_EYE")
      (libsource (lib "eagle-import") (part "TP_SOLDREYE"))
    )
    (comp (ref "X3")
      (value "MSTBV4MTSV")
      (footprint "eagle-import:MSTBV4")
      (libsource (lib "eagle-import") (part "MSTBV4MTSV"))
    )
    (comp (ref "C84")
      (value "1uF")
      (footprint "eagle-import:C0603")
      (libsource (lib "eagle-import") (part "C-EUC0603"))
    )
    (comp (ref "C85")
      (value "100nF")
      (footprint "eagle-import:C0603")
      (libsource (lib "eagle-import") (part "C-EUC0603"))
    )
    (comp (ref "C86")
      (value "100nF")
      (footprint "eagle-import:C0603")
      (libsource (lib "eagle-import") (part "C-EUC0603"))
    )
    (comp (ref "C87")
      (value "100nF")
      (footprint "eagle-import:C0603")
      (libsource (lib "eagle-import") (part "C-EUC0603"))
    )
    (comp (ref "C88")
      (value "100nF")
      (footprint "eagle-import:C0603")
      (libsource (lib "eagle-import") (part "C-EUC0603"))
    )
    (comp (ref "C89")
      (value "100nF")
      (footprint "eagle-import:C0603")
      (libsource (lib "eagle-import") (part "C-EUC0603"))
    )
    (comp (ref "C90")
      (value "100nF")
      (footprint "eagle-import:C0603")
      (libsource (lib "eagle-import") (part "C-EUC0603"))
    )
    (comp (ref "C91")
      (value "100nF")
      (footprint "eagle-import:C0603")
      (libsource (lib "eagle-import") (part "C-EUC0603"))
    )
    (comp (ref "C92")
      (value "100nF")
      (footprint "eagle-import:C0603")
      (libsource (lib "eagle-import") (part "C-EUC0603"))
    )
    (comp (ref "C93")
      (value "100nF")
      (footprint "eagle-import:C0603")
      (libsource (lib "eagle-import") (part "rcl_MICHAEL (1)_C-EUC0603"))
    )
    (comp (ref "C94")
      (value "2.2uF")
      (footprint "eagle-import:C0603")
      (libsource (lib "eagle-import") (part "C-EUC0603"))
    )
    (comp (ref "C95")
      (value "2.2uF")
      (footprint "eagle-import:C0603")
      (libsource (lib "eagle-import") (part "C-EUC0603"))
    )
    (comp (ref "C96")
      (value "10pF")
      (footprint "eagle-import:C0603")
      (libsource (lib "eagle-import") (part "C-EUC0603"))
    )
    (comp (ref "C97")
      (value "10pF")
      (footprint "eagle-import:C0603")
      (libsource (lib "eagle-import") (part "C-EUC0603"))
    )
    (comp (ref "C98")
      (value "100nF")
      (footprint "eagle-import:C0603")
      (libsource (lib "eagle-import") (part "rcl_MICHAEL (1)_C-EUC0603"))
    )
    (comp (ref "D18")
      (value "PESD3V3S5UD,125")
      (footprint "eagle-import:TSOP-6")
      (libsource (lib "eagle-import") (part "PESD3V3S5UD,125"))
    )
    (comp (ref "IC22")
      (value "STM32F407VGT7")
      (footprint "eagle-import:LQFP100")
      (libsource (lib "eagle-import") (part "STM32F407VGT6"))
    )
    (comp (ref "IC23")
      (value "AT34C04-SS5M-T")
      (footprint "eagle-import:SOIC8")
      (libsource (lib "eagle-import") (part "AT34C04-X5M-T_SOIC"))
    )
    (comp (ref "L9")
      (value "1K")
      (footprint "eagle-import:R0603")
      (libsource (lib "eagle-import") (part "BEAD0603"))
    )
    (comp (ref "R106")
      (value "22R")
      (footprint "eagle-import:R0603")
      (libsource (lib "eagle-import") (part "rcl_MICHAEL (1)_R-EU_R0603"))
    )
    (comp (ref "R107")
      (value "10R")
      (footprint "eagle-import:R0603")
      (libsource (lib "eagle-import") (part "rcl_MICHAEL (1)_R-EU_R0603"))
    )
    (comp (ref "R108")
      (value "47k")
      (footprint "eagle-import:R0603")
      (libsource (lib "eagle-import") (part "rcl_MICHAEL (1)_R-EU_R0603"))
    )
    (comp (ref "R109")
      (value "22R")
      (footprint "eagle-import:R0603")
      (libsource (lib "eagle-import") (part "rcl_MICHAEL (1)_R-EU_R0603"))
    )
    (comp (ref "R110")
      (value "100R")
      (footprint "eagle-import:R0603")
      (libsource (lib "eagle-import") (part "rcl_MICHAEL (1)_R-EU_R0603"))
    )
    (comp (ref "R111")
      (value "4.7k")
      (footprint "eagle-import:R0603")
      (libsource (lib "eagle-import") (part "rcl_MICHAEL (1)_R-EU_R0603"))
    )
    (comp (ref "R112")
      (value "47k")
      (footprint "eagle-import:R0603")
      (libsource (lib "eagle-import") (part "rcl_MICHAEL (1)_R-EU_R0603"))
    )
    (comp (ref "R113")
      (value "47k")
      (footprint "eagle-import:R0603")
      (libsource (lib "eagle-import") (part "rcl_MICHAEL (1)_R-EU_R0603"))
    )
    (comp (ref "R114")
      (value "4.7k")
      (footprint "eagle-import:R0603")
      (libsource (lib "eagle-import") (part "rcl_MICHAEL (1)_R-EU_R0603"))
    )
    (comp (ref "TP7")
      (value "TP_SOLDREYE")
      (footprint "eagle-import:SOLDER_EYE")
      (libsource (lib "eagle-import") (part "TP_SOLDREYE"))
    )
    (comp (ref "X6")
      (value "3220-10-0300-00")
      (footprint "eagle-import:3220-10-0300-00")
      (libsource (lib "eagle-import") (part "3220-10-0300-00"))
    )
    (comp (ref "X7")
      (value "057-020-1")
      (footprint "eagle-import:057-020-1")
      (libsource (lib "eagle-import") (part "057-020-1"))
    )
    (comp (ref "XT1")
      (value "16MHz")
      (footprint "eagle-import:3225_4P")
      (libsource (lib "eagle-import") (part "CRYSTAL_322516MHZ"))
    )
    (comp (ref "C63")
      (value "100nF")
      (footprint "eagle-import:C0603")
      (libsource (lib "eagle-import") (part "rcl_MICHAEL (1)_C-EUC0603"))
    )
    (comp (ref "C64")
      (value "100nF")
      (footprint "eagle-import:C0603")
      (libsource (lib "eagle-import") (part "rcl_MICHAEL (1)_C-EUC0603"))
    )
    (comp (ref "C65")
      (value "100nF")
      (footprint "eagle-import:C0603")
      (libsource (lib "eagle-import") (part "rcl_MICHAEL (1)_C-EUC0603"))
    )
    (comp (ref "C66")
      (value "100nF")
      (footprint "eagle-import:C0603")
      (libsource (lib "eagle-import") (part "rcl_MICHAEL (1)_C-EUC0603"))
    )
    (comp (ref "C67")
      (value "100nF")
      (footprint "eagle-import:C0603")
      (libsource (lib "eagle-import") (part "rcl_MICHAEL (1)_C-EUC0603"))
    )
    (comp (ref "C68")
      (value "100nF")
      (footprint "eagle-import:C0603")
      (libsource (lib "eagle-import") (part "rcl_MICHAEL (1)_C-EUC0603"))
    )
    (comp (ref "C69")
      (value "100nF")
      (footprint "eagle-import:C0603")
      (libsource (lib "eagle-import") (part "rcl_MICHAEL (1)_C-EUC0603"))
    )
    (comp (ref "C70")
      (value "100nF")
      (footprint "eagle-import:C0603")
      (libsource (lib "eagle-import") (part "rcl_MICHAEL (1)_C-EUC0603"))
    )
    (comp (ref "C71")
      (value "100nF")
      (footprint "eagle-import:C0603")
      (libsource (lib "eagle-import") (part "rcl_MICHAEL (1)_C-EUC0603"))
    )
    (comp (ref "C72")
      (value "100nF")
      (footprint "eagle-import:C0603")
      (libsource (lib "eagle-import") (part "rcl_MICHAEL (1)_C-EUC0603"))
    )
    (comp (ref "C73")
      (value "100nF")
      (footprint "eagle-import:C0603")
      (libsource (lib "eagle-import") (part "rcl_MICHAEL (1)_C-EUC0603"))
    )
    (comp (ref "C74")
      (value "10uF")
      (footprint "eagle-import:C0805")
      (libsource (lib "eagle-import") (part "rcl_MICHAEL (1)_C-EUC0805"))
    )
    (comp (ref "C75")
      (value "100nF")
      (footprint "eagle-import:C0603")
      (libsource (lib "eagle-import") (part "rcl_MICHAEL (1)_C-EUC0603"))
    )
    (comp (ref "C76")
      (value "1uF")
      (footprint "eagle-import:C0603")
      (libsource (lib "eagle-import") (part "rcl_MICHAEL (1)_C-EUC0603"))
    )
    (comp (ref "C77")
      (value "100nF")
      (footprint "eagle-import:C0603")
      (libsource (lib "eagle-import") (part "rcl_MICHAEL (1)_C-EUC0603"))
    )
    (comp (ref "C78")
      (value "100nF")
      (footprint "eagle-import:C0603")
      (libsource (lib "eagle-import") (part "rcl_MICHAEL (1)_C-EUC0603"))
    )
    (comp (ref "C79")
      (value "100nF")
      (footprint "eagle-import:C0603")
      (libsource (lib "eagle-import") (part "rcl_MICHAEL (1)_C-EUC0603"))
    )
    (comp (ref "C80")
      (value "10uF")
      (footprint "eagle-import:C0805")
      (libsource (lib "eagle-import") (part "rcl_MICHAEL (1)_C-EUC0805"))
    )
    (comp (ref "C81")
      (value "22uF")
      (footprint "eagle-import:E2-5")
      (libsource (lib "eagle-import") (part "CPOL-EUE2-5"))
    )
    (comp (ref "C82")
      (value "100nF")
      (footprint "eagle-import:C0603")
      (libsource (lib "eagle-import") (part "rcl_MICHAEL (1)_C-EUC0603"))
    )
    (comp (ref "C83")
      (value "100nF")
      (footprint "eagle-import:C0603")
      (libsource (lib "eagle-import") (part "rcl_MICHAEL (1)_C-EUC0603"))
    )
    (comp (ref "D14")
      (value "1N5819W")
      (footprint "eagle-import:SOD123")
      (libsource (lib "eagle-import") (part "1N5819W"))
    )
    (comp (ref "D15")
      (value "BAV99-7-F")
      (footprint "eagle-import:SOT23")
      (libsource (lib "eagle-import") (part "BAV99SOT23"))
    )
    (comp (ref "D16")
      (value "BAV99-7-F")
      (footprint "eagle-import:SOT23")
      (libsource (lib "eagle-import") (part "BAV99SOT23"))
    )
    (comp (ref "D17")
      (value "6V")
      (footprint "eagle-import:DO214AC")
      (libsource (lib "eagle-import") (part "TVS_DIODE_UNISMA"))
    )
    (comp (ref "IC14")
      (value "LTV-354T")
      (footprint "eagle-import:SOP04")
      (libsource (lib "eagle-import") (part "LTV354"))
    )
    (comp (ref "IC15")
      (value "LTV-354T")
      (footprint "eagle-import:SOP04")
      (libsource (lib "eagle-import") (part "LTV354"))
    )
    (comp (ref "IC16")
      (value "LTV-354T")
      (footprint "eagle-import:SOP04")
      (libsource (lib "eagle-import") (part "LTV354"))
    )
    (comp (ref "IC17")
      (value "LTV-354T")
      (footprint "eagle-import:SOP04")
      (libsource (lib "eagle-import") (part "LTV354"))
    )
    (comp (ref "IC18")
      (value "LTV-354T")
      (footprint "eagle-import:SOP04")
      (libsource (lib "eagle-import") (part "LTV354"))
    )
    (comp (ref "IC19")
      (value "SN74LVC14ADR")
      (footprint "eagle-import:SO14")
      (libsource (lib "eagle-import") (part "SN74AC14PWR_SOIC"))
    )
    (comp (ref "IC20")
      (value "SY6280AAC")
      (footprint "eagle-import:SOT23-5")
      (libsource (lib "eagle-import") (part "SY6280AAC"))
    )
    (comp (ref "IC21")
      (value "MCP6272T-E/SN")
      (footprint "eagle-import:SO08")
      (libsource (lib "eagle-import") (part "LM358D"))
    )
    (comp (ref "K1")
      (value "G2RL-1-HA DC5")
      (footprint "eagle-import:E3206S")
      (libsource (lib "eagle-import") (part "E3206S"))
    )
    (comp (ref "L8")
      (value "BLM21PG331BH1D")
      (footprint "eagle-import:R0805")
      (libsource (lib "eagle-import") (part "BEAD0805"))
    )
    (comp (ref "LED4")
      (value "ORANGE")
      (footprint "eagle-import:LED_0603")
      (libsource (lib "eagle-import") (part "LED_0603"))
    )
    (comp (ref "Q5")
      (value "DMN2046")
      (footprint "eagle-import:SOT23")
      (libsource (lib "eagle-import") (part "NMOS_DMN2046"))
    )
    (comp (ref "Q6")
      (value "DMN2046")
      (footprint "eagle-import:SOT23")
      (libsource (lib "eagle-import") (part "NMOS_DMN2046"))
    )
    (comp (ref "R72")
      (value "100R")
      (footprint "eagle-import:R0603")
      (libsource (lib "eagle-import") (part "rcl_MICHAEL (1)_R-EU_R0603"))
    )
    (comp (ref "R73")
      (value "470R")
      (footprint "eagle-import:R0603")
      (libsource (lib "eagle-import") (part "rcl_MICHAEL (1)_R-EU_R0603"))
    )
    (comp (ref "R74")
      (value "10k")
      (footprint "eagle-import:R0603")
      (libsource (lib "eagle-import") (part "rcl_MICHAEL (1)_R-EU_R0603"))
    )
    (comp (ref "R75")
      (value "4.7k")
      (footprint "eagle-import:R0805")
      (libsource (lib "eagle-import") (part "rcl_MICHAEL (1)_R-EU_R0805"))
    )
    (comp (ref "R76")
      (value "4.7k")
      (footprint "eagle-import:R0805")
      (libsource (lib "eagle-import") (part "rcl_MICHAEL (1)_R-EU_R0805"))
    )
    (comp (ref "R77")
      (value "4.7k")
      (footprint "eagle-import:R0805")
      (libsource (lib "eagle-import") (part "rcl_MICHAEL (1)_R-EU_R0805"))
    )
    (comp (ref "R78")
      (value "4.7k")
      (footprint "eagle-import:R0805")
      (libsource (lib "eagle-import") (part "rcl_MICHAEL (1)_R-EU_R0805"))
    )
    (comp (ref "R79")
      (value "4.7k")
      (footprint "eagle-import:R0805")
      (libsource (lib "eagle-import") (part "rcl_MICHAEL (1)_R-EU_R0805"))
    )
    (comp (ref "R80")
      (value "1k")
      (footprint "eagle-import:R0603")
      (libsource (lib "eagle-import") (part "rcl_MICHAEL (1)_R-EU_R0603"))
    )
    (comp (ref "R81")
      (value "1k")
      (footprint "eagle-import:R0603")
      (libsource (lib "eagle-import") (part "rcl_MICHAEL (1)_R-EU_R0603"))
    )
    (comp (ref "R82")
      (value "1k")
      (footprint "eagle-import:R0603")
      (libsource (lib "eagle-import") (part "rcl_MICHAEL (1)_R-EU_R0603"))
    )
    (comp (ref "R83")
      (value "1k")
      (footprint "eagle-import:R0603")
      (libsource (lib "eagle-import") (part "rcl_MICHAEL (1)_R-EU_R0603"))
    )
    (comp (ref "R84")
      (value "1k")
      (footprint "eagle-import:R0603")
      (libsource (lib "eagle-import") (part "rcl_MICHAEL (1)_R-EU_R0603"))
    )
    (comp (ref "R85")
      (value "10k")
      (footprint "eagle-import:R0603")
      (libsource (lib "eagle-import") (part "rcl_MICHAEL (1)_R-EU_R0603"))
    )
    (comp (ref "R86")
      (value "10k")
      (footprint "eagle-import:R0603")
      (libsource (lib "eagle-import") (part "rcl_MICHAEL (1)_R-EU_R0603"))
    )
    (comp (ref "R87")
      (value "10k")
      (footprint "eagle-import:R0603")
      (libsource (lib "eagle-import") (part "rcl_MICHAEL (1)_R-EU_R0603"))
    )
    (comp (ref "R88")
      (value "10k")
      (footprint "eagle-import:R0603")
      (libsource (lib "eagle-import") (part "rcl_MICHAEL (1)_R-EU_R0603"))
    )
    (comp (ref "R89")
      (value "10k")
      (footprint "eagle-import:R0603")
      (libsource (lib "eagle-import") (part "rcl_MICHAEL (1)_R-EU_R0603"))
    )
    (comp (ref "R90")
      (value "10k")
      (footprint "eagle-import:R0603")
      (libsource (lib "eagle-import") (part "rcl_MICHAEL (1)_R-EU_R0603"))
    )
    (comp (ref "R91")
      (value "10k")
      (footprint "eagle-import:R0603")
      (libsource (lib "eagle-import") (part "rcl_MICHAEL (1)_R-EU_R0603"))
    )
    (comp (ref "R92")
      (value "10k")
      (footprint "eagle-import:R0603")
      (libsource (lib "eagle-import") (part "rcl_MICHAEL (1)_R-EU_R0603"))
    )
    (comp (ref "R93")
      (value "10k")
      (footprint "eagle-import:R0603")
      (libsource (lib "eagle-import") (part "rcl_MICHAEL (1)_R-EU_R0603"))
    )
    (comp (ref "R94")
      (value "10k")
      (footprint "eagle-import:R0603")
      (libsource (lib "eagle-import") (part "rcl_MICHAEL (1)_R-EU_R0603"))
    )
    (comp (ref "R95")
      (value "1k")
      (footprint "eagle-import:R0603")
      (libsource (lib "eagle-import") (part "rcl_MICHAEL (1)_R-EU_R0603"))
    )
    (comp (ref "R96")
      (value "15k")
      (footprint "eagle-import:R0603")
      (libsource (lib "eagle-import") (part "rcl_MICHAEL (1)_R-EU_R0603"))
    )
    (comp (ref "R97")
      (value "120R")
      (footprint "eagle-import:R1206")
      (libsource (lib "eagle-import") (part "rcl_MICHAEL (1)_R-EU_R1206"))
    )
    (comp (ref "R98")
      (value "4.99k")
      (footprint "eagle-import:R0603")
      (libsource (lib "eagle-import") (part "rcl_MICHAEL (1)_R-EU_R0603"))
    )
    (comp (ref "R99")
      (value "10k")
      (footprint "eagle-import:R0603")
      (libsource (lib "eagle-import") (part "rcl_MICHAEL (1)_R-EU_R0603"))
    )
    (comp (ref "R100")
      (value "13.7k")
      (footprint "eagle-import:R0603")
      (libsource (lib "eagle-import") (part "rcl_MICHAEL (1)_R-EU_R0603"))
    )
    (comp (ref "R101")
      (value "DNP")
      (footprint "eagle-import:R0603")
      (libsource (lib "eagle-import") (part "rcl_MICHAEL (1)_R-EU_R0603"))
    )
    (comp (ref "R102")
      (value "10k")
      (footprint "eagle-import:R0603")
      (libsource (lib "eagle-import") (part "rcl_MICHAEL (1)_R-EU_R0603"))
    )
    (comp (ref "R103")
      (value "10k")
      (footprint "eagle-import:R0603")
      (libsource (lib "eagle-import") (part "rcl_MICHAEL (1)_R-EU_R0603"))
    )
    (comp (ref "R104")
      (value "10k")
      (footprint "eagle-import:R0603")
      (libsource (lib "eagle-import") (part "rcl_MICHAEL (1)_R-EU_R0603"))
    )
    (comp (ref "R105")
      (value "10k")
      (footprint "eagle-import:R0603")
      (libsource (lib "eagle-import") (part "rcl_MICHAEL (1)_R-EU_R0603"))
    )
    (comp (ref "X4")
      (value "MSTBV3")
      (footprint "eagle-import:MSTBV3")
      (libsource (lib "eagle-import") (part "MSTBV3"))
    )
    (comp (ref "X5")
      (value "MSTBV12")
      (footprint "eagle-import:MSTBV12")
      (libsource (lib "eagle-import") (part "MSTBV12"))
    )
  )
  (nets
    (net (code "1") (name "+3.3V") (class "Default")
      (node (ref "C26") (pin "1") (pinfunction "1_1") (pintype "passive"))
      (node (ref "C27") (pin "+") (pinfunction "+_+") (pintype "passive"))
      (node (ref "C46") (pin "1") (pinfunction "1_1") (pintype "passive"))
      (node (ref "C49") (pin "1") (pinfunction "1_1") (pintype "passive"))
      (node (ref "C50") (pin "1") (pinfunction "1_1") (pintype "passive"))
      (node (ref "C53") (pin "1") (pinfunction "1_1") (pintype "passive"))
      (node (ref "C54") (pin "1") (pinfunction "1_1") (pintype "passive"))
      (node (ref "C63") (pin "1") (pinfunction "1_1") (pintype "passive"))
      (node (ref "C75") (pin "1") (pinfunction "1_1") (pintype "passive"))
      (node (ref "C86") (pin "1") (pinfunction "1_1") (pintype "passive"))
      (node (ref "C87") (pin "1") (pinfunction "1_1") (pintype "passive"))
      (node (ref "C88") (pin "1") (pinfunction "1_1") (pintype "passive"))
      (node (ref "C89") (pin "1") (pinfunction "1_1") (pintype "passive"))
      (node (ref "C90") (pin "1") (pinfunction "1_1") (pintype "passive"))
      (node (ref "C92") (pin "1") (pinfunction "1_1") (pintype "passive"))
      (node (ref "C98") (pin "2") (pinfunction "2_2") (pintype "passive"))
      (node (ref "D15") (pin "2") (pinfunction "C_2") (pintype "passive"))
      (node (ref "D16") (pin "2") (pinfunction "C_2") (pintype "passive"))
      (node (ref "D18") (pin "6") (pinfunction "IO5_6") (pintype "bidirectional"))
      (node (ref "IC10") (pin "1") (pinfunction "VDD1_1") (pintype "passive"))
      (node (ref "IC10") (pin "7") (pinfunction "EN1_7") (pintype "input"))
      (node (ref "IC11") (pin "1") (pinfunction "VDD1_1") (pintype "passive"))
      (node (ref "IC12") (pin "8") (pinfunction "VDD2_8") (pintype "bidirectional"))
      (node (ref "IC19") (pin "14") (pinfunction "VDD_14") (pintype "input"))
      (node (ref "IC21") (pin "8") (pinfunction "V+_8") (pintype "input"))
      (node (ref "IC22") (pin "100") (pinfunction "VDD_100") (pintype "bidirectional"))
      (node (ref "IC22") (pin "11") (pinfunction "VDD_11") (pintype "bidirectional"))
      (node (ref "IC22") (pin "19") (pinfunction "VDD_19") (pintype "bidirectional"))
      (node (ref "IC22") (pin "28") (pinfunction "VDD_28") (pintype "bidirectional"))
      (node (ref "IC22") (pin "50") (pinfunction "VDD_50") (pintype "bidirectional"))
      (node (ref "IC22") (pin "6") (pinfunction "VBAT_6") (pintype "bidirectional"))
      (node (ref "IC22") (pin "75") (pinfunction "VDD_75") (pintype "bidirectional"))
      (node (ref "IC23") (pin "8") (pinfunction "VCC_8") (pintype "bidirectional"))
      (node (ref "IC5") (pin "2") (pinfunction "VOUT_2") (pintype "input"))
      (node (ref "IC5") (pin "4") (pinfunction "VOUT_4") (pintype "input"))
      (node (ref "IC6") (pin "1") (pinfunction "VIN_1") (pintype "input"))
      (node (ref "IC9") (pin "5") (pinfunction "VDD_5") (pintype "input"))
      (node (ref "L9") (pin "2") (pinfunction "2_2") (pintype "passive"))
      (node (ref "R111") (pin "2") (pinfunction "2_2") (pintype "passive"))
      (node (ref "R112") (pin "2") (pinfunction "2_2") (pintype "passive"))
      (node (ref "R114") (pin "2") (pinfunction "2_2") (pintype "passive"))
      (node (ref "R85") (pin "2") (pinfunction "2_2") (pintype "passive"))
      (node (ref "R86") (pin "2") (pinfunction "2_2") (pintype "passive"))
      (node (ref "R87") (pin "2") (pinfunction "2_2") (pintype "passive"))
      (node (ref "R88") (pin "2") (pinfunction "2_2") (pintype "passive"))
      (node (ref "R89") (pin "2") (pinfunction "2_2") (pintype "passive"))
      (node (ref "TP9") (pin "1") (pinfunction "TP_1") (pintype "input"))
      (node (ref "X6") (pin "1") (pinfunction "1_1") (pintype "bidirectional"))
    )
    (net (code "2") (name "+5V") (class "Default")
      (node (ref "C20") (pin "1") (pinfunction "1_1") (pintype "passive"))
      (node (ref "C22") (pin "+") (pinfunction "+_+") (pintype "passive"))
      (node (ref "C23") (pin "1") (pinfunction "1_1") (pintype "passive"))
      (node (ref "C24") (pin "1") (pinfunction "1_1") (pintype "passive"))
      (node (ref "C25") (pin "1") (pinfunction "1_1") (pintype "passive"))
      (node (ref "C74") (pin "1") (pinfunction "1_1") (pintype "passive"))
      (node (ref "C99") (pin "+") (pinfunction "+_+") (pintype "passive"))
      (node (ref "D14") (pin "1") (pinfunction "C_1") (pintype "passive"))
      (node (ref "IC20") (pin "5") (pinfunction "IN_5") (pintype "bidirectional"))
      (node (ref "IC5") (pin "3") (pinfunction "VIN_3") (pintype "input"))
      (node (ref "K1") (pin "1") (pinfunction "1_1") (pintype "passive"))
      (node (ref "L4") (pin "P$1") (pinfunction "1_P$1") (pintype "passive"))
      (node (ref "LED4") (pin "A") (pinfunction "A_A") (pintype "passive"))
      (node (ref "R24") (pin "2") (pinfunction "2_2") (pintype "passive"))
      (node (ref "R25") (pin "2") (pinfunction "2_2") (pintype "passive"))
      (node (ref "R95") (pin "2") (pinfunction "2_2") (pintype "passive"))
      (node (ref "TP8") (pin "1") (pinfunction "TP_1") (pintype "input"))
      (node (ref "X2") (pin "1") (pinfunction "1_1") (pintype "passive"))
      (node (ref "X7") (pin "1") (pinfunction "S_1") (pintype "passive"))
      (node (ref "X7") (pin "2") (pinfunction "S_2") (pintype "passive"))
    )
    (net (code "3") (name "+5V_D") (class "Default")
      (node (ref "C33") (pin "+") (pinfunction "+_+") (pintype "passive"))
      (node (ref "C55") (pin "1") (pinfunction "1_1") (pintype "passive"))
      (node (ref "C56") (pin "1") (pinfunction "1_1") (pintype "passive"))
      (node (ref "D12") (pin "2") (pinfunction "A_2") (pintype "passive"))
      (node (ref "IC12") (pin "1") (pinfunction "VDD1_1") (pintype "bidirectional"))
      (node (ref "IC7") (pin "1") (pinfunction "VO_1") (pintype "passive"))
      (node (ref "R33") (pin "2") (pinfunction "2_2") (pintype "passive"))
      (node (ref "R38") (pin "2") (pinfunction "2_2") (pintype "passive"))
      (node (ref "R40") (pin "2") (pinfunction "2_2") (pintype "passive"))
      (node (ref "R69") (pin "2") (pinfunction "2_2") (pintype "passive"))
      (node (ref "R71") (pin "2") (pinfunction "2_2") (pintype "passive"))
      (node (ref "TP11") (pin "1") (pinfunction "TP_1") (pintype "input"))
    )
    (net (code "4") (name "+5V_FILT") (class "Default")
      (node (ref "C60") (pin "1") (pinfunction "1_1") (pintype "passive"))
      (node (ref "C61") (pin "1") (pinfunction "1_1") (pintype "passive"))
      (node (ref "C62") (pin "1") (pinfunction "1_1") (pintype "passive"))
      (node (ref "IC10") (pin "10") (pinfunction "EN2_10") (pintype "input"))
      (node (ref "IC10") (pin "16") (pinfunction "VDD2_16") (pintype "passive"))
      (node (ref "IC11") (pin "16") (pinfunction "VDD2_16") (pintype "passive"))
      (node (ref "IC13") (pin "20") (pinfunction "VDD_20") (pintype "input"))
      (node (ref "R71") (pin "1") (pinfunction "1_1") (pintype "passive"))
    )
    (net (code "5") (name "+15V") (class "Default")
      (node (ref "C13") (pin "+") (pinfunction "+_+") (pintype "passive"))
      (node (ref "C29") (pin "1") (pinfunction "1_1") (pintype "passive"))
      (node (ref "D10") (pin "C") (pinfunction "C_C") (pintype "passive"))
      (node (ref "D12") (pin "1") (pinfunction "C_1") (pintype "passive"))
      (node (ref "D9") (pin "2") (pinfunction "A_2") (pintype "passive"))
      (node (ref "IC7") (pin "8") (pinfunction "VI_8") (pintype "input"))
      (node (ref "R12") (pin "2") (pinfunction "2_2") (pintype "passive"))
      (node (ref "R16") (pin "2") (pinfunction "2_2") (pintype "passive"))
      (node (ref "R34") (pin "1") (pinfunction "1_1") (pintype "passive"))
      (node (ref "R6") (pin "2") (pinfunction "2_2") (pintype "passive"))
      (node (ref "TP10") (pin "1") (pinfunction "TP_1") (pintype "input"))
    )
    (net (code "6") (name "+HV") (class "Default")
      (node (ref "C9") (pin "+") (pinfunction "+_+") (pintype "passive"))
      (node (ref "D8") (pin "A") (pinfunction "A_A") (pintype "passive"))
      (node (ref "L2") (pin "1") (pinfunction "1_1") (pintype "passive"))
      (node (ref "T1") (pin "3") (pinfunction "3_3") (pintype "passive"))
      (node (ref "TP2") (pin "TP") (pinfunction "TP_TP") (pintype "input"))
    )
    (net (code "7") (name "0...10V_RNG") (class "Default")
      (node (ref "IC22") (pin "26") (pinfunction "PA3_26") (pintype "bidirectional"))
      (node (ref "Q6") (pin "1") (pinfunction "G_1") (pintype "passive"))
    )
    (net (code "8") (name "AIN_ADC") (class "Default")
      (node (ref "C82") (pin "1") (pinfunction "1_1") (pintype "passive"))
      (node (ref "IC22") (pin "25") (pinfunction "PA2_25") (pintype "bidirectional"))
      (node (ref "R104") (pin "2") (pinfunction "2_2") (pintype "passive"))
    )
    (net (code "9") (name "COM") (class "Default")
      (node (ref "C64") (pin "2") (pinfunction "2_2") (pintype "passive"))
      (node (ref "C65") (pin "2") (pinfunction "2_2") (pintype "passive"))
      (node (ref "C66") (pin "2") (pinfunction "2_2") (pintype "passive"))
      (node (ref "C67") (pin "2") (pinfunction "2_2") (pintype "passive"))
      (node (ref "C68") (pin "2") (pinfunction "2_2") (pintype "passive"))
      (node (ref "IC14") (pin "2") (pinfunction "AC2_2") (pintype "passive"))
      (node (ref "IC15") (pin "2") (pinfunction "AC2_2") (pintype "passive"))
      (node (ref "IC16") (pin "2") (pinfunction "AC2_2") (pintype "passive"))
      (node (ref "IC17") (pin "2") (pinfunction "AC2_2") (pintype "passive"))
      (node (ref "IC18") (pin "2") (pinfunction "AC2_2") (pintype "passive"))
      (node (ref "R80") (pin "1") (pinfunction "1_1") (pintype "passive"))
      (node (ref "R81") (pin "1") (pinfunction "1_1") (pintype "passive"))
      (node (ref "R82") (pin "1") (pinfunction "1_1") (pintype "passive"))
      (node (ref "R83") (pin "1") (pinfunction "1_1") (pintype "passive"))
      (node (ref "R84") (pin "1") (pinfunction "1_1") (pintype "passive"))
      (node (ref "X5") (pin "6") (pinfunction "SK_6") (pintype "passive"))
    )
    (net (code "10") (name "DEBUG") (class "Default")
      (node (ref "IC22") (pin "31") (pinfunction "PA6_31") (pintype "bidirectional"))
      (node (ref "TP7") (pin "1") (pinfunction "TP_1") (pintype "input"))
    )
    (net (code "11") (name "DISP_A0") (class "Default")
      (node (ref "IC22") (pin "17") (pinfunction "PC2_17") (pintype "bidirectional"))
      (node (ref "X7") (pin "6") (pinfunction "S_6") (pintype "passive"))
    )
    (net (code "12") (name "DISP_MOSI") (class "Default")
      (node (ref "IC22") (pin "80") (pinfunction "PC12_80") (pintype "bidirectional"))
      (node (ref "X7") (pin "10") (pinfunction "S_10") (pintype "passive"))
    )
    (net (code "13") (name "DISP_SCK") (class "Default")
      (node (ref "R106") (pin "1") (pinfunction "1_1") (pintype "passive"))
      (node (ref "X7") (pin "7") (pinfunction "S_7") (pintype "passive"))
    )
    (net (code "14") (name "ENCODER_A") (class "Default")
      (node (ref "IC22") (pin "92") (pinfunction "PB6_92") (pintype "bidirectional"))
      (node (ref "X7") (pin "13") (pinfunction "S_13") (pintype "passive"))
    )
    (net (code "15") (name "ENCODER_B") (class "Default")
      (node (ref "IC22") (pin "93") (pinfunction "PB7_93") (pintype "bidirectional"))
      (node (ref "X7") (pin "16") (pinfunction "S_16") (pintype "passive"))
    )
    (net (code "16") (name "ENCODER_PB") (class "Default")
      (node (ref "IC22") (pin "95") (pinfunction "PB8_95") (pintype "bidirectional"))
      (node (ref "X7") (pin "17") (pinfunction "S_17") (pintype "passive"))
    )
    (net (code "17") (name "GND") (class "Default")
      (node (ref "C14") (pin "-") (pinfunction "-_-") (pintype "passive"))
      (node (ref "C15") (pin "-") (pinfunction "-_-") (pintype "passive"))
      (node (ref "C17") (pin "2") (pinfunction "2_2") (pintype "passive"))
      (node (ref "C18") (pin "2") (pinfunction "2_2") (pintype "passive"))
      (node (ref "C19") (pin "2") (pinfunction "2_2") (pintype "passive"))
      (node (ref "C20") (pin "2") (pinfunction "2_2") (pintype "passive"))
      (node (ref "C22") (pin "-") (pinfunction "-_-") (pintype "passive"))
      (node (ref "C23") (pin "2") (pinfunction "2_2") (pintype "passive"))
      (node (ref "C24") (pin "2") (pinfunction "2_2") (pintype "passive"))
      (node (ref "C25") (pin "2") (pinfunction "2_2") (pintype "passive"))
      (node (ref "C26") (pin "2") (pinfunction "2_2") (pintype "passive"))
      (node (ref "C27") (pin "-") (pinfunction "-_-") (pintype "passive"))
      (node (ref "C46") (pin "2") (pinfunction "2_2") (pintype "passive"))
      (node (ref "C47") (pin "2") (pinfunction "2_2") (pintype "passive"))
      (node (ref "C49") (pin "2") (pinfunction "2_2") (pintype "passive"))
      (node (ref "C50") (pin "2") (pinfunction "2_2") (pintype "passive"))
      (node (ref "C51") (pin "2") (pinfunction "2_2") (pintype "passive"))
      (node (ref "C53") (pin "2") (pinfunction "2_2") (pintype "passive"))
      (node (ref "C54") (pin "2") (pinfunction "2_2") (pintype "passive"))
      (node (ref "C63") (pin "2") (pinfunction "2_2") (pintype "passive"))
      (node (ref "C69") (pin "2") (pinfunction "2_2") (pintype "passive"))
      (node (ref "C70") (pin "2") (pinfunction "2_2") (pintype "passive"))
      (node (ref "C71") (pin "2") (pinfunction "2_2") (pintype "passive"))
      (node (ref "C72") (pin "2") (pinfunction "2_2") (pintype "passive"))
      (node (ref "C73") (pin "2") (pinfunction "2_2") (pintype "passive"))
      (node (ref "C74") (pin "2") (pinfunction "2_2") (pintype "passive"))
      (node (ref "C75") (pin "2") (pinfunction "2_2") (pintype "passive"))
      (node (ref "C76") (pin "2") (pinfunction "2_2") (pintype "passive"))
      (node (ref "C77") (pin "2") (pinfunction "2_2") (pintype "passive"))
      (node (ref "C78") (pin "2") (pinfunction "2_2") (pintype "passive"))
      (node (ref "C79") (pin "2") (pinfunction "2_2") (pintype "passive"))
      (node (ref "C80") (pin "2") (pinfunction "2_2") (pintype "passive"))
      (node (ref "C81") (pin "-") (pinfunction "-_-") (pintype "passive"))
      (node (ref "C82") (pin "2") (pinfunction "2_2") (pintype "passive"))
      (node (ref "C83") (pin "2") (pinfunction "2_2") (pintype "passive"))
      (node (ref "C84") (pin "2") (pinfunction "2_2") (pintype "passive"))
      (node (ref "C85") (pin "2") (pinfunction "2_2") (pintype "passive"))
      (node (ref "C86") (pin "2") (pinfunction "2_2") (pintype "passive"))
      (node (ref "C87") (pin "2") (pinfunction "2_2") (pintype "passive"))
      (node (ref "C88") (pin "2") (pinfunction "2_2") (pintype "passive"))
      (node (ref "C89") (pin "2") (pinfunction "2_2") (pintype "passive"))
      (node (ref "C90") (pin "2") (pinfunction "2_2") (pintype "passive"))
      (node (ref "C91") (pin "2") (pinfunction "2_2") (pintype "passive"))
      (node (ref "C92") (pin "2") (pinfunction "2_2") (pintype "passive"))
      (node (ref "C93") (pin "2") (pinfunction "2_2") (pintype "passive"))
      (node (ref "C94") (pin "2") (pinfunction "2_2") (pintype "passive"))
      (node (ref "C95") (pin "2") (pinfunction "2_2") (pintype "passive"))
      (node (ref "C96") (pin "2") (pinfunction "2_2") (pintype "passive"))
      (node (ref "C97") (pin "2") (pinfunction "2_2") (pintype "passive"))
      (node (ref "C98") (pin "1") (pinfunction "1_1") (pintype "passive"))
      (node (ref "C99") (pin "-") (pinfunction "-_-") (pintype "passive"))
      (node (ref "CY3") (pin "2") (pinfunction "2_2") (pintype "passive"))
      (node (ref "D15") (pin "1") (pinfunction "A_1") (pintype "passive"))
      (node (ref "D16") (pin "1") (pinfunction "A_1") (pintype "passive"))
      (node (ref "D17") (pin "A") (pinfunction "A_A") (pintype "passive"))
      (node (ref "D18") (pin "2") (pinfunction "GND_2") (pintype "power_in"))
      (node (ref "IC10") (pin "2") (pinfunction "GND1_2") (pintype "passive"))
      (node (ref "IC10") (pin "8") (pinfunction "GND1_8") (pintype "passive"))
      (node (ref "IC11") (pin "8") (pinfunction "GND1_8") (pintype "passive"))
      (node (ref "IC12") (pin "5") (pinfunction "GND2_5") (pintype "bidirectional"))
      (node (ref "IC14") (pin "3") (pinfunction "E_3") (pintype "passive"))
      (node (ref "IC15") (pin "3") (pinfunction "E_3") (pintype "passive"))
      (node (ref "IC16") (pin "3") (pinfunction "E_3") (pintype "passive"))
      (node (ref "IC17") (pin "3") (pinfunction "E_3") (pintype "passive"))
      (node (ref "IC18") (pin "3") (pinfunction "E_3") (pintype "passive"))
      (node (ref "IC19") (pin "1") (pinfunction "I_1") (pintype "input"))
      (node (ref "IC19") (pin "7") (pinfunction "VSS_7") (pintype "input"))
      (node (ref "IC20") (pin "2") (pinfunction "GND_2") (pintype "bidirectional"))
      (node (ref "IC21") (pin "4") (pinfunction "V-_4") (pintype "input"))
      (node (ref "IC22") (pin "10") (pinfunction "VSS_10") (pintype "bidirectional"))
      (node (ref "IC22") (pin "20") (pinfunction "VSSA_20") (pintype "bidirectional"))
      (node (ref "IC22") (pin "27") (pinfunction "VSS_27") (pintype "bidirectional"))
      (node (ref "IC22") (pin "74") (pinfunction "VSS_74") (pintype "bidirectional"))
      (node (ref "IC22") (pin "94") (pinfunction "BOOT0_94") (pintype "bidirectional"))
      (node (ref "IC22") (pin "99") (pinfunction "VSS99_99") (pintype "bidirectional"))
      (node (ref "IC23") (pin "1") (pinfunction "A0_1") (pintype "bidirectional"))
      (node (ref "IC23") (pin "2") (pinfunction "A1_2") (pintype "bidirectional"))
      (node (ref "IC23") (pin "3") (pinfunction "A2_3") (pintype "bidirectional"))
      (node (ref "IC23") (pin "4") (pinfunction "GND_4") (pintype "bidirectional"))
      (node (ref "IC23") (pin "7") (pinfunction "NC_7") (pintype "bidirectional"))
      (node (ref "IC3") (pin "3") (pinfunction "A_3") (pintype "passive"))
      (node (ref "IC4") (pin "1") (pinfunction "GND_1") (pintype "bidirectional"))
      (node (ref "IC5") (pin "1") (pinfunction "GND_1") (pintype "input"))
      (node (ref "IC6") (pin "3") (pinfunction "GND_3") (pintype "input"))
      (node (ref "IC9") (pin "2") (pinfunction "VSS_2") (pintype "input"))
      (node (ref "LED2") (pin "C") (pinfunction "C_C") (pintype "passive"))
      (node (ref "Q5") (pin "2") (pinfunction "S_2") (pintype "passive"))
      (node (ref "Q6") (pin "2") (pinfunction "S_2") (pintype "passive"))
      (node (ref "R100") (pin "1") (pinfunction "1_1") (pintype "passive"))
      (node (ref "R101") (pin "1") (pinfunction "1_1") (pintype "passive"))
      (node (ref "R108") (pin "1") (pinfunction "1_1") (pintype "passive"))
      (node (ref "R113") (pin "1") (pinfunction "1_1") (pintype "passive"))
      (node (ref "R22") (pin "1") (pinfunction "1_1") (pintype "passive"))
      (node (ref "R26") (pin "1") (pinfunction "1_1") (pintype "passive"))
      (node (ref "R49") (pin "1") (pinfunction "1_1") (pintype "passive"))
      (node (ref "R54") (pin "1") (pinfunction "1_1") (pintype "passive"))
      (node (ref "R74") (pin "2") (pinfunction "2_2") (pintype "passive"))
      (node (ref "R97") (pin "1") (pinfunction "1_1") (pintype "passive"))
      (node (ref "R98") (pin "1") (pinfunction "1_1") (pintype "passive"))
      (node (ref "T1") (pin "6") (pinfunction "6_6") (pintype "passive"))
      (node (ref "TP5") (pin "1") (pinfunction "TP_1") (pintype "input"))
      (node (ref "X2") (pin "2") (pinfunction "2_2") (pintype "passive"))
      (node (ref "X5") (pin "10") (pinfunction "SK_10") (pintype "passive"))
      (node (ref "X5") (pin "7") (pinfunction "SK_7") (pintype "passive"))
      (node (ref "X6") (pin "3") (pinfunction "3_3") (pintype "bidirectional"))
      (node (ref "X6") (pin "5") (pinfunction "5_5") (pintype "bidirectional"))
      (node (ref "X7") (pin "14") (pinfunction "S_14") (pintype "passive"))
      (node (ref "X7") (pin "15") (pinfunction "S_15") (pintype "passive"))
      (node (ref "X7") (pin "19") (pinfunction "S_19") (pintype "passive"))
      (node (ref "X7") (pin "20") (pinfunction "S_20") (pintype "passive"))
      (node (ref "X7") (pin "8") (pinfunction "S_8") (pintype "passive"))
      (node (ref "X7") (pin "9") (pinfunction "S_9") (pintype "passive"))
      (node (ref "XT1") (pin "2") (pinfunction "2_2") (pintype "passive"))
      (node (ref "XT1") (pin "4") (pinfunction "4_4") (pintype "passive"))
    )
    (net (code "18") (name "GNDI") (class "Default")
      (node (ref "C1") (pin "2") (pinfunction "2_2") (pintype "passive"))
      (node (ref "C10") (pin "2") (pinfunction "2_2") (pintype "passive"))
      (node (ref "C11") (pin "2") (pinfunction "2_2") (pintype "passive"))
      (node (ref "C12") (pin "-") (pinfunction "-_-") (pintype "passive"))
      (node (ref "C13") (pin "-") (pinfunction "-_-") (pintype "passive"))
      (node (ref "C28") (pin "2") (pinfunction "2_2") (pintype "passive"))
      (node (ref "C29") (pin "2") (pinfunction "2_2") (pintype "passive"))
      (node (ref "C30") (pin "2") (pinfunction "2_2") (pintype "passive"))
      (node (ref "C31") (pin "2") (pinfunction "2_2") (pintype "passive"))
      (node (ref "C32") (pin "2") (pinfunction "2_2") (pintype "passive"))
      (node (ref "C33") (pin "-") (pinfunction "-_-") (pintype "passive"))
      (node (ref "C34") (pin "2") (pinfunction "2_2") (pintype "passive"))
      (node (ref "C35") (pin "2") (pinfunction "2_2") (pintype "passive"))
      (node (ref "C36") (pin "2") (pinfunction "2_2") (pintype "passive"))
      (node (ref "C37") (pin "2") (pinfunction "2_2") (pintype "passive"))
      (node (ref "C38") (pin "2") (pinfunction "2_2") (pintype "passive"))
      (node (ref "C42") (pin "2") (pinfunction "2_2") (pintype "passive"))
      (node (ref "C43") (pin "2") (pinfunction "2_2") (pintype "passive"))
      (node (ref "C44") (pin "2") (pinfunction "2_2") (pintype "passive"))
      (node (ref "C45") (pin "2") (pinfunction "2_2") (pintype "passive"))
      (node (ref "C55") (pin "2") (pinfunction "2_2") (pintype "passive"))
      (node (ref "C56") (pin "2") (pinfunction "2_2") (pintype "passive"))
      (node (ref "C57") (pin "1") (pinfunction "1_1") (pintype "passive"))
      (node (ref "C59") (pin "2") (pinfunction "2_2") (pintype "passive"))
      (node (ref "C60") (pin "2") (pinfunction "2_2") (pintype "passive"))
      (node (ref "C61") (pin "2") (pinfunction "2_2") (pintype "passive"))
      (node (ref "C62") (pin "2") (pinfunction "2_2") (pintype "passive"))
      (node (ref "C8") (pin "-") (pinfunction "-_-") (pintype "passive"))
      (node (ref "C9") (pin "-") (pinfunction "-_-") (pintype "passive"))
      (node (ref "CY3") (pin "1") (pinfunction "1_1") (pintype "passive"))
      (node (ref "D1") (pin "2") (pinfunction "A_2") (pintype "passive"))
      (node (ref "D13") (pin "A") (pinfunction "A_A") (pintype "passive"))
      (node (ref "D3") (pin "A") (pinfunction "A_A") (pintype "passive"))
      (node (ref "D5") (pin "A") (pinfunction "A_A") (pintype "passive"))
      (node (ref "H9") (pin "B3,0") (pinfunction "MOUNT_B3,0") (pintype "passive"))
      (node (ref "IC1") (pin "1") (pinfunction "GND_1") (pintype "bidirectional"))
      (node (ref "IC10") (pin "15") (pinfunction "GND2_15") (pintype "passive"))
      (node (ref "IC10") (pin "9") (pinfunction "GND2_9") (pintype "passive"))
      (node (ref "IC11") (pin "9") (pinfunction "GND2_9") (pintype "passive"))
      (node (ref "IC12") (pin "4") (pinfunction "GND1_4") (pintype "bidirectional"))
      (node (ref "IC13") (pin "10") (pinfunction "VSS_10") (pintype "input"))
      (node (ref "IC13") (pin "19") (pinfunction "G2_19") (pintype "input"))
      (node (ref "IC13") (pin "8") (pinfunction "A7_8") (pintype "input"))
      (node (ref "IC13") (pin "9") (pinfunction "A8_9") (pintype "input"))
      (node (ref "IC2") (pin "3") (pinfunction "EMIT_3") (pintype "passive"))
      (node (ref "IC7") (pin "2") (pinfunction "GND_2") (pintype "passive"))
      (node (ref "IC7") (pin "3") (pinfunction "GND_3") (pintype "passive"))
      (node (ref "IC7") (pin "6") (pinfunction "GND_6") (pintype "passive"))
      (node (ref "IC7") (pin "7") (pinfunction "GND_7") (pintype "passive"))
      (node (ref "IC8") (pin "1") (pinfunction "GND_1") (pintype "input"))
      (node (ref "LED1") (pin "C") (pinfunction "C_C") (pintype "passive"))
      (node (ref "LED3") (pin "C") (pinfunction "C_C") (pintype "passive"))
      (node (ref "NTC1") (pin "1") (pinfunction "1_1") (pintype "passive"))
      (node (ref "Q2") (pin "2") (pinfunction "S_2") (pintype "passive"))
      (node (ref "Q3") (pin "2") (pinfunction "S_2") (pintype "passive"))
      (node (ref "Q4") (pin "2") (pinfunction "S_2") (pintype "passive"))
      (node (ref "R12") (pin "1") (pinfunction "1_1") (pintype "passive"))
      (node (ref "R14") (pin "1") (pinfunction "1_1") (pintype "passive"))
      (node (ref "R17") (pin "1") (pinfunction "1_1") (pintype "passive"))
      (node (ref "R2") (pin "1") (pinfunction "1_1") (pintype "passive"))
      (node (ref "R37") (pin "1") (pinfunction "1_1") (pintype "passive"))
      (node (ref "R39") (pin "1") (pinfunction "1_1") (pintype "passive"))
      (node (ref "R46") (pin "1") (pinfunction "1_1") (pintype "passive"))
      (node (ref "R67") (pin "1") (pinfunction "1_1") (pintype "passive"))
      (node (ref "R8") (pin "1") (pinfunction "1_1") (pintype "passive"))
      (node (ref "T1") (pin "4") (pinfunction "4_4") (pintype "passive"))
      (node (ref "TP3") (pin "1") (pinfunction "TP_1") (pintype "input"))
      (node (ref "TP4") (pin "1") (pinfunction "TP_1") (pintype "input"))
    )
    (net (code "19") (name "INPUT_A_BUF") (class "Default")
      (node (ref "IC19") (pin "6") (pinfunction "O_6") (pintype "output"))
      (node (ref "IC22") (pin "84") (pinfunction "PD3_84") (pintype "bidirectional"))
    )
    (net (code "20") (name "INPUT_B_BUF") (class "Default")
      (node (ref "IC19") (pin "8") (pinfunction "O_8") (pintype "output"))
      (node (ref "IC22") (pin "79") (pinfunction "PC11_79") (pintype "bidirectional"))
    )
    (net (code "21") (name "INPUT_C_BUF") (class "Default")
      (node (ref "IC19") (pin "10") (pinfunction "O_10") (pintype "output"))
      (node (ref "IC22") (pin "81") (pinfunction "PD0_81") (pintype "bidirectional"))
    )
    (net (code "22") (name "INPUT_D_BUF") (class "Default")
      (node (ref "IC19") (pin "12") (pinfunction "O_12") (pintype "output"))
      (node (ref "IC22") (pin "82") (pinfunction "PD1_82") (pintype "bidirectional"))
    )
    (net (code "23") (name "INPUT_E_BUF") (class "Default")
      (node (ref "IC19") (pin "4") (pinfunction "O_4") (pintype "output"))
      (node (ref "IC22") (pin "83") (pinfunction "PD2_83") (pintype "bidirectional"))
    )
    (net (code "24") (name "N") (class "Default")
      (node (ref "C3") (pin "2") (pinfunction "2_2") (pintype "passive"))
      (node (ref "L1") (pin "OUT2") (pinfunction "OUT2_OUT2") (pintype "passive"))
      (node (ref "R1") (pin "1") (pinfunction "1_1") (pintype "passive"))
      (node (ref "R5") (pin "1") (pinfunction "1_1") (pintype "passive"))
      (node (ref "X1") (pin "2") (pinfunction "SK_2") (pintype "passive"))
    )
    (net (code "25") (name "NRST") (class "Default")
      (node (ref "C93") (pin "1") (pinfunction "1_1") (pintype "passive"))
      (node (ref "D18") (pin "3") (pinfunction "IO2_3") (pintype "bidirectional"))
      (node (ref "IC22") (pin "14") (pinfunction "NRST_14") (pintype "bidirectional"))
      (node (ref "X6") (pin "10") (pinfunction "10_10") (pintype "bidirectional"))
    )
    (net (code "26") (name "Net-(C3-Pad1)") (class "Default")
      (node (ref "C3") (pin "1") (pinfunction "1_1") (pintype "passive"))
      (node (ref "F1") (pin "2") (pinfunction "2_2") (pintype "passive"))
      (node (ref "L1") (pin "OUT1") (pinfunction "OUT1_OUT1") (pintype "passive"))
      (node (ref "R1") (pin "2") (pinfunction "2_2") (pintype "passive"))
      (node (ref "R3") (pin "2") (pinfunction "2_2") (pintype "passive"))
    )
    (net (code "27") (name "Net-(C4-Pad1)") (class "Default")
      (node (ref "C4") (pin "1") (pinfunction "1_1") (pintype "passive"))
      (node (ref "CY1") (pin "1") (pinfunction "1_1") (pintype "passive"))
      (node (ref "D2") (pin "A") (pinfunction "A_A") (pintype "passive"))
      (node (ref "D3") (pin "C") (pinfunction "C_C") (pintype "passive"))
      (node (ref "L1") (pin "IN1") (pinfunction "IN1_IN1") (pintype "passive"))
    )
    (net (code "28") (name "Net-(C4-Pad2)") (class "Default")
      (node (ref "C4") (pin "2") (pinfunction "2_2") (pintype "passive"))
      (node (ref "CY2") (pin "2") (pinfunction "2_2") (pintype "passive"))
      (node (ref "D4") (pin "A") (pinfunction "A_A") (pintype "passive"))
      (node (ref "D5") (pin "C") (pinfunction "C_C") (pintype "passive"))
      (node (ref "L1") (pin "IN2") (pinfunction "IN2_IN2") (pintype "passive"))
    )
    (net (code "29") (name "Net-(C8-Pad+)") (class "Default")
      (node (ref "C8") (pin "+") (pinfunction "+_+") (pintype "passive"))
      (node (ref "D6") (pin "C") (pinfunction "C_C") (pintype "passive"))
      (node (ref "L2") (pin "2") (pinfunction "2_2") (pintype "passive"))
    )
    (net (code "30") (name "Net-(C10-Pad1)") (class "Default")
      (node (ref "C10") (pin "1") (pinfunction "1_1") (pintype "passive"))
      (node (ref "R13") (pin "1") (pinfunction "1_1") (pintype "passive"))
    )
    (net (code "31") (name "Net-(C14-Pad+)") (class "Default")
      (node (ref "C14") (pin "+") (pinfunction "+_+") (pintype "passive"))
      (node (ref "D11") (pin "C") (pinfunction "C_C") (pintype "passive"))
      (node (ref "L3") (pin "2") (pinfunction "2_2") (pintype "passive"))
      (node (ref "R18") (pin "2") (pinfunction "2_2") (pintype "passive"))
    )
    (net (code "32") (name "Net-(C16-Pad2)") (class "Default")
      (node (ref "C16") (pin "2") (pinfunction "2_2") (pintype "passive"))
      (node (ref "R20") (pin "1") (pinfunction "1_1") (pintype "passive"))
    )
    (net (code "33") (name "Net-(C21-Pad1)") (class "Default")
      (node (ref "C21") (pin "1") (pinfunction "1_1") (pintype "passive"))
      (node (ref "R23") (pin "2") (pinfunction "2_2") (pintype "passive"))
    )
    (net (code "34") (name "Net-(C38-Pad1)") (class "Default")
      (node (ref "C38") (pin "1") (pinfunction "1_1") (pintype "passive"))
      (node (ref "R43") (pin "2") (pinfunction "2_2") (pintype "passive"))
      (node (ref "R45") (pin "1") (pinfunction "1_1") (pintype "passive"))
    )
    (net (code "35") (name "Net-(C52-Pad1)") (class "Default")
      (node (ref "C52") (pin "1") (pinfunction "1_1") (pintype "passive"))
      (node (ref "R50") (pin "1") (pinfunction "1_1") (pintype "passive"))
      (node (ref "R52") (pin "2") (pinfunction "2_2") (pintype "passive"))
    )
    (net (code "36") (name "Net-(C52-Pad2)") (class "Default")
      (node (ref "C52") (pin "2") (pinfunction "2_2") (pintype "passive"))
      (node (ref "R51") (pin "1") (pinfunction "1_1") (pintype "passive"))
      (node (ref "R53") (pin "2") (pinfunction "2_2") (pintype "passive"))
    )
    (net (code "37") (name "Net-(C97-Pad1)") (class "Default")
      (node (ref "C97") (pin "1") (pinfunction "1_1") (pintype "passive"))
      (node (ref "R110") (pin "1") (pinfunction "1_1") (pintype "passive"))
      (node (ref "XT1") (pin "3") (pinfunction "3_3") (pintype "passive"))
    )
    (net (code "38") (name "Net-(D1-C)") (class "Default")
      (node (ref "C2") (pin "2") (pinfunction "2_2") (pintype "passive"))
      (node (ref "D1") (pin "1") (pinfunction "C_1") (pintype "passive"))
      (node (ref "Q1") (pin "1") (pinfunction "G_1") (pintype "passive"))
      (node (ref "R2") (pin "2") (pinfunction "2_2") (pintype "passive"))
    )
    (net (code "39") (name "Net-(D7-PadA)") (class "Default")
      (node (ref "D7") (pin "A") (pinfunction "A_A") (pintype "passive"))
      (node (ref "IC1") (pin "7") (pinfunction "DRAIN_7") (pintype "bidirectional"))
      (node (ref "IC1") (pin "8") (pinfunction "DRAIN_8") (pintype "bidirectional"))
      (node (ref "T1") (pin "1") (pinfunction "1_1") (pintype "passive"))
    )
    (net (code "40") (name "Net-(D7-PadC)") (class "Default")
      (node (ref "D7") (pin "C") (pinfunction "C_C") (pintype "passive"))
      (node (ref "D8") (pin "C") (pinfunction "C_C") (pintype "passive"))
    )
    (net (code "41") (name "Net-(D9-C)") (class "Default")
      (node (ref "D9") (pin "1") (pinfunction "C_1") (pintype "passive"))
      (node (ref "R15") (pin "2") (pinfunction "2_2") (pintype "passive"))
    )
    (net (code "42") (name "Net-(D10-PadA)") (class "Default")
      (node (ref "D10") (pin "A") (pinfunction "A_A") (pintype "passive"))
      (node (ref "T1") (pin "5") (pinfunction "5_5") (pintype "passive"))
    )
    (net (code "43") (name "Net-(D11-PadA)") (class "Default")
      (node (ref "D11") (pin "A") (pinfunction "A_A") (pintype "passive"))
      (node (ref "T1") (pin "9") (pinfunction "9_9") (pintype "passive"))
    )
    (net (code "44") (name "Net-(D14-A)") (class "Default")
      (node (ref "D14") (pin "2") (pinfunction "A_2") (pintype "passive"))
      (node (ref "K1") (pin "2") (pinfunction "2_2") (pintype "passive"))
      (node (ref "Q5") (pin "3") (pinfunction "D_3") (pintype "passive"))
      (node (ref "R73") (pin "1") (pinfunction "1_1") (pintype "passive"))
    )
    (net (code "45") (name "Net-(D15-AC)") (class "Default")
      (node (ref "C79") (pin "1") (pinfunction "1_1") (pintype "passive"))
      (node (ref "D15") (pin "3") (pinfunction "AC_3") (pintype "passive"))
      (node (ref "IC21") (pin "3") (pinfunction "+IN_3") (pintype "input"))
      (node (ref "R99") (pin "2") (pinfunction "2_2") (pintype "passive"))
    )
    (net (code "46") (name "Net-(D16-AC)") (class "Default")
      (node (ref "C78") (pin "1") (pinfunction "1_1") (pintype "passive"))
      (node (ref "D16") (pin "3") (pinfunction "AC_3") (pintype "passive"))
      (node (ref "IC21") (pin "5") (pinfunction "+IN_5") (pintype "input"))
      (node (ref "R96") (pin "2") (pinfunction "2_2") (pintype "passive"))
      (node (ref "R98") (pin "2") (pinfunction "2_2") (pintype "passive"))
    )
    (net (code "47") (name "Net-(IC1-COMP)") (class "Default")
      (node (ref "C11") (pin "1") (pinfunction "1_1") (pintype "passive"))
      (node (ref "IC1") (pin "5") (pinfunction "COMP_5") (pintype "bidirectional"))
      (node (ref "IC2") (pin "4") (pinfunction "COL_4") (pintype "passive"))
      (node (ref "R13") (pin "2") (pinfunction "2_2") (pintype "passive"))
    )
    (net (code "48") (name "Net-(IC1-FB)") (class "Default")
      (node (ref "IC1") (pin "4") (pinfunction "FB_4") (pintype "bidirectional"))
      (node (ref "R16") (pin "1") (pinfunction "1_1") (pintype "passive"))
      (node (ref "R17") (pin "2") (pinfunction "2_2") (pintype "passive"))
    )
    (net (code "49") (name "Net-(IC1-LIM)") (class "Default")
      (node (ref "IC1") (pin "3") (pinfunction "LIM_3") (pintype "bidirectional"))
      (node (ref "R14") (pin "2") (pinfunction "2_2") (pintype "passive"))
    )
    (net (code "50") (name "Net-(IC1-VDD)") (class "Default")
      (node (ref "C12") (pin "+") (pinfunction "+_+") (pintype "passive"))
      (node (ref "IC1") (pin "2") (pinfunction "VDD_2") (pintype "bidirectional"))
      (node (ref "R15") (pin "1") (pinfunction "1_1") (pintype "passive"))
    )
    (net (code "51") (name "Net-(IC2-A)") (class "Default")
      (node (ref "IC2") (pin "1") (pinfunction "A_1") (pintype "passive"))
      (node (ref "R18") (pin "1") (pinfunction "1_1") (pintype "passive"))
      (node (ref "R19") (pin "2") (pinfunction "2_2") (pintype "passive"))
    )
    (net (code "52") (name "Net-(IC2-C)") (class "Default")
      (node (ref "C16") (pin "1") (pinfunction "1_1") (pintype "passive"))
      (node (ref "IC2") (pin "2") (pinfunction "C_2") (pintype "passive"))
      (node (ref "IC3") (pin "1") (pinfunction "C_1") (pintype "passive"))
      (node (ref "R19") (pin "1") (pinfunction "1_1") (pintype "passive"))
    )
    (net (code "53") (name "Net-(IC3-R)") (class "Default")
      (node (ref "IC3") (pin "2") (pinfunction "R_2") (pintype "passive"))
      (node (ref "R20") (pin "2") (pinfunction "2_2") (pintype "passive"))
      (node (ref "R21") (pin "1") (pinfunction "1_1") (pintype "passive"))
      (node (ref "R22") (pin "2") (pinfunction "2_2") (pintype "passive"))
    )
    (net (code "54") (name "Net-(IC4-BOOT)") (class "Default")
      (node (ref "IC4") (pin "6") (pinfunction "BOOT_6") (pintype "bidirectional"))
      (node (ref "R23") (pin "1") (pinfunction "1_1") (pintype "passive"))
    )
    (net (code "55") (name "Net-(IC4-EN)") (class "Default")
      (node (ref "C15") (pin "+") (pinfunction "+_+") (pintype "passive"))
      (node (ref "C17") (pin "1") (pinfunction "1_1") (pintype "passive"))
      (node (ref "C18") (pin "1") (pinfunction "1_1") (pintype "passive"))
      (node (ref "C19") (pin "1") (pinfunction "1_1") (pintype "passive"))
      (node (ref "IC4") (pin "3") (pinfunction "VIN_3") (pintype "bidirectional"))
      (node (ref "IC4") (pin "5") (pinfunction "EN_5") (pintype "bidirectional"))
      (node (ref "L3") (pin "1") (pinfunction "1_1") (pintype "passive"))
      (node (ref "R21") (pin "2") (pinfunction "2_2") (pintype "passive"))
      (node (ref "TP6") (pin "1") (pinfunction "TP_1") (pintype "input"))
    )
    (net (code "56") (name "Net-(IC4-FB)") (class "Default")
      (node (ref "IC4") (pin "4") (pinfunction "FB_4") (pintype "bidirectional"))
      (node (ref "R25") (pin "1") (pinfunction "1_1") (pintype "passive"))
      (node (ref "R26") (pin "2") (pinfunction "2_2") (pintype "passive"))
    )
    (net (code "57") (name "Net-(IC4-SW)") (class "Default")
      (node (ref "C21") (pin "2") (pinfunction "2_2") (pintype "passive"))
      (node (ref "IC4") (pin "2") (pinfunction "SW_2") (pintype "bidirectional"))
      (node (ref "L4") (pin "P$2") (pinfunction "2_P$2") (pintype "passive"))
    )
    (net (code "58") (name "Net-(IC8-CIN)") (class "Default")
      (node (ref "C37") (pin "1") (pinfunction "1_1") (pintype "passive"))
      (node (ref "IC8") (pin "12") (pinfunction "CIN_12") (pintype "input"))
      (node (ref "R42") (pin "2") (pinfunction "2_2") (pintype "passive"))
      (node (ref "R43") (pin "1") (pinfunction "1_1") (pintype "passive"))
    )
    (net (code "59") (name "Net-(IC8-NU)") (class "Default")
      (node (ref "IC8") (pin "20") (pinfunction "NU_20") (pintype "input"))
      (node (ref "IC8") (pin "23") (pinfunction "NV_23") (pintype "input"))
      (node (ref "IC8") (pin "26") (pinfunction "NW_26") (pintype "input"))
      (node (ref "R44") (pin "2") (pinfunction "2_2") (pintype "passive"))
      (node (ref "R45") (pin "2") (pinfunction "2_2") (pintype "passive"))
      (node (ref "R46") (pin "2") (pinfunction "2_2") (pintype "passive"))
    )
    (net (code "60") (name "Net-(IC8-OP+)") (class "Default")
      (node (ref "C36") (pin "1") (pinfunction "1_1") (pintype "passive"))
      (node (ref "IC8") (pin "6") (pinfunction "OP+_6") (pintype "input"))
      (node (ref "R41") (pin "2") (pinfunction "2_2") (pintype "passive"))
      (node (ref "R44") (pin "1") (pinfunction "1_1") (pintype "passive"))
    )
    (net (code "61") (name "Net-(IC8-OP-)") (class "Default")
      (node (ref "IC8") (pin "8") (pinfunction "OP-_8") (pintype "input"))
      (node (ref "R36") (pin "1") (pinfunction "1_1") (pintype "passive"))
      (node (ref "R37") (pin "2") (pinfunction "2_2") (pintype "passive"))
    )
    (net (code "62") (name "Net-(IC8-OPOUT)") (class "Default")
      (node (ref "IC8") (pin "7") (pinfunction "OPOUT_7") (pintype "output"))
      (node (ref "R35") (pin "2") (pinfunction "2_2") (pintype "passive"))
    )
    (net (code "63") (name "Net-(IC8-VBOOTU)") (class "Default")
      (node (ref "C39") (pin "1") (pinfunction "1_1") (pintype "passive"))
      (node (ref "IC8") (pin "17") (pinfunction "VBOOTU_17") (pintype "passive"))
    )
    (net (code "64") (name "Net-(IC8-VBOOTV)") (class "Default")
      (node (ref "C40") (pin "1") (pinfunction "1_1") (pintype "passive"))
      (node (ref "IC8") (pin "21") (pinfunction "VBOOTV_21") (pintype "passive"))
    )
    (net (code "65") (name "Net-(IC8-VBOOTW)") (class "Default")
      (node (ref "C41") (pin "1") (pinfunction "1_1") (pintype "passive"))
      (node (ref "IC8") (pin "24") (pinfunction "VBOOTW_24") (pintype "passive"))
    )
    (net (code "66") (name "Net-(IC9A-+IN)") (class "Default")
      (node (ref "C51") (pin "1") (pinfunction "1_1") (pintype "passive"))
      (node (ref "IC9") (pin "1") (pinfunction "+IN_1") (pintype "input"))
      (node (ref "R49") (pin "2") (pinfunction "2_2") (pintype "passive"))
      (node (ref "R51") (pin "2") (pinfunction "2_2") (pintype "passive"))
    )
    (net (code "67") (name "Net-(IC9A--IN)") (class "Default")
      (node (ref "C48") (pin "2") (pinfunction "2_2") (pintype "passive"))
      (node (ref "IC9") (pin "3") (pinfunction "-IN_3") (pintype "input"))
      (node (ref "R48") (pin "1") (pinfunction "1_1") (pintype "passive"))
      (node (ref "R50") (pin "2") (pinfunction "2_2") (pintype "passive"))
    )
    (net (code "68") (name "Net-(IC9A-OUT)") (class "Default")
      (node (ref "C48") (pin "1") (pinfunction "1_1") (pintype "passive"))
      (node (ref "IC9") (pin "4") (pinfunction "OUT_4") (pintype "bidirectional"))
      (node (ref "R47") (pin "1") (pinfunction "1_1") (pintype "passive"))
      (node (ref "R48") (pin "2") (pinfunction "2_2") (pintype "passive"))
    )
    (net (code "69") (name "Net-(IC10-B1)") (class "Default")
      (node (ref "IC10") (pin "14") (pinfunction "B1_14") (pintype "output"))
      (node (ref "R61") (pin "1") (pinfunction "1_1") (pintype "passive"))
    )
    (net (code "70") (name "Net-(IC10-B2)") (class "Default")
      (node (ref "IC10") (pin "13") (pinfunction "B2_13") (pintype "output"))
      (node (ref "R62") (pin "1") (pinfunction "1_1") (pintype "passive"))
    )
    (net (code "71") (name "Net-(IC11-A1)") (class "Default")
      (node (ref "IC11") (pin "2") (pinfunction "A1_2") (pintype "input"))
      (node (ref "R55") (pin "2") (pinfunction "2_2") (pintype "passive"))
    )
    (net (code "72") (name "Net-(IC11-A2)") (class "Default")
      (node (ref "IC11") (pin "3") (pinfunction "A2_3") (pintype "input"))
      (node (ref "R56") (pin "2") (pinfunction "2_2") (pintype "passive"))
    )
    (net (code "73") (name "Net-(IC11-A3)") (class "Default")
      (node (ref "IC11") (pin "4") (pinfunction "A3_4") (pintype "input"))
      (node (ref "R57") (pin "2") (pinfunction "2_2") (pintype "passive"))
    )
    (net (code "74") (name "Net-(IC11-A4)") (class "Default")
      (node (ref "IC11") (pin "5") (pinfunction "A4_5") (pintype "input"))
      (node (ref "R58") (pin "2") (pinfunction "2_2") (pintype "passive"))
    )
    (net (code "75") (name "Net-(IC11-A5)") (class "Default")
      (node (ref "IC11") (pin "6") (pinfunction "A5_6") (pintype "input"))
      (node (ref "R59") (pin "2") (pinfunction "2_2") (pintype "passive"))
    )
    (net (code "76") (name "Net-(IC11-A6)") (class "Default")
      (node (ref "IC11") (pin "7") (pinfunction "A6_7") (pintype "input"))
      (node (ref "R60") (pin "2") (pinfunction "2_2") (pintype "passive"))
    )
    (net (code "77") (name "Net-(IC12-VINN)") (class "Default")
      (node (ref "C58") (pin "2") (pinfunction "2_2") (pintype "passive"))
      (node (ref "C59") (pin "1") (pinfunction "1_1") (pintype "passive"))
      (node (ref "IC12") (pin "3") (pinfunction "VINN_3") (pintype "bidirectional"))
      (node (ref "R64") (pin "2") (pinfunction "2_2") (pintype "passive"))
    )
    (net (code "78") (name "Net-(IC12-VINP)") (class "Default")
      (node (ref "C57") (pin "2") (pinfunction "2_2") (pintype "passive"))
      (node (ref "C58") (pin "1") (pinfunction "1_1") (pintype "passive"))
      (node (ref "IC12") (pin "2") (pinfunction "VINP_2") (pintype "bidirectional"))
      (node (ref "R63") (pin "2") (pinfunction "2_2") (pintype "passive"))
    )
    (net (code "79") (name "Net-(IC12-VOUTN)") (class "Default")
      (node (ref "IC12") (pin "6") (pinfunction "VOUTN_6") (pintype "bidirectional"))
      (node (ref "R52") (pin "1") (pinfunction "1_1") (pintype "passive"))
    )
    (net (code "80") (name "Net-(IC12-VOUTP)") (class "Default")
      (node (ref "IC12") (pin "7") (pinfunction "VOUTP_7") (pintype "bidirectional"))
      (node (ref "R53") (pin "1") (pinfunction "1_1") (pintype "passive"))
    )
    (net (code "81") (name "Net-(IC14-AC1)") (class "Default")
      (node (ref "C64") (pin "1") (pinfunction "1_1") (pintype "passive"))
      (node (ref "IC14") (pin "1") (pinfunction "AC1_1") (pintype "passive"))
      (node (ref "R75") (pin "2") (pinfunction "2_2") (pintype "passive"))
      (node (ref "R80") (pin "2") (pinfunction "2_2") (pintype "passive"))
    )
    (net (code "82") (name "Net-(IC14-C)") (class "Default")
      (node (ref "IC14") (pin "4") (pinfunction "C_4") (pintype "passive"))
      (node (ref "R85") (pin "1") (pinfunction "1_1") (pintype "passive"))
      (node (ref "R90") (pin "1") (pinfunction "1_1") (pintype "passive"))
    )
    (net (code "83") (name "Net-(IC15-AC1)") (class "Default")
      (node (ref "C65") (pin "1") (pinfunction "1_1") (pintype "passive"))
      (node (ref "IC15") (pin "1") (pinfunction "AC1_1") (pintype "passive"))
      (node (ref "R76") (pin "2") (pinfunction "2_2") (pintype "passive"))
      (node (ref "R81") (pin "2") (pinfunction "2_2") (pintype "passive"))
    )
    (net (code "84") (name "Net-(IC15-C)") (class "Default")
      (node (ref "IC15") (pin "4") (pinfunction "C_4") (pintype "passive"))
      (node (ref "R86") (pin "1") (pinfunction "1_1") (pintype "passive"))
      (node (ref "R91") (pin "1") (pinfunction "1_1") (pintype "passive"))
    )
    (net (code "85") (name "Net-(IC16-AC1)") (class "Default")
      (node (ref "C66") (pin "1") (pinfunction "1_1") (pintype "passive"))
      (node (ref "IC16") (pin "1") (pinfunction "AC1_1") (pintype "passive"))
      (node (ref "R77") (pin "2") (pinfunction "2_2") (pintype "passive"))
      (node (ref "R82") (pin "2") (pinfunction "2_2") (pintype "passive"))
    )
    (net (code "86") (name "Net-(IC16-C)") (class "Default")
      (node (ref "IC16") (pin "4") (pinfunction "C_4") (pintype "passive"))
      (node (ref "R87") (pin "1") (pinfunction "1_1") (pintype "passive"))
      (node (ref "R92") (pin "1") (pinfunction "1_1") (pintype "passive"))
    )
    (net (code "87") (name "Net-(IC17-AC1)") (class "Default")
      (node (ref "C67") (pin "1") (pinfunction "1_1") (pintype "passive"))
      (node (ref "IC17") (pin "1") (pinfunction "AC1_1") (pintype "passive"))
      (node (ref "R78") (pin "2") (pinfunction "2_2") (pintype "passive"))
      (node (ref "R83") (pin "2") (pinfunction "2_2") (pintype "passive"))
    )
    (net (code "88") (name "Net-(IC17-C)") (class "Default")
      (node (ref "IC17") (pin "4") (pinfunction "C_4") (pintype "passive"))
      (node (ref "R88") (pin "1") (pinfunction "1_1") (pintype "passive"))
      (node (ref "R93") (pin "1") (pinfunction "1_1") (pintype "passive"))
    )
    (net (code "89") (name "Net-(IC18-AC1)") (class "Default")
      (node (ref "C68") (pin "1") (pinfunction "1_1") (pintype "passive"))
      (node (ref "IC18") (pin "1") (pinfunction "AC1_1") (pintype "passive"))
      (node (ref "R79") (pin "2") (pinfunction "2_2") (pintype "passive"))
      (node (ref "R84") (pin "2") (pinfunction "2_2") (pintype "passive"))
    )
    (net (code "90") (name "Net-(IC18-C)") (class "Default")
      (node (ref "IC18") (pin "4") (pinfunction "C_4") (pintype "passive"))
      (node (ref "R89") (pin "1") (pinfunction "1_1") (pintype "passive"))
      (node (ref "R94") (pin "1") (pinfunction "1_1") (pintype "passive"))
    )
    (net (code "91") (name "Net-(IC19B-I)") (class "Default")
      (node (ref "C73") (pin "1") (pinfunction "1_1") (pintype "passive"))
      (node (ref "IC19") (pin "3") (pinfunction "I_3") (pintype "input"))
      (node (ref "R94") (pin "2") (pinfunction "2_2") (pintype "passive"))
    )
    (net (code "92") (name "Net-(IC19C-I)") (class "Default")
      (node (ref "C69") (pin "1") (pinfunction "1_1") (pintype "passive"))
      (node (ref "IC19") (pin "5") (pinfunction "I_5") (pintype "input"))
      (node (ref "R90") (pin "2") (pinfunction "2_2") (pintype "passive"))
    )
    (net (code "93") (name "Net-(IC19D-I)") (class "Default")
      (node (ref "C70") (pin "1") (pinfunction "1_1") (pintype "passive"))
      (node (ref "IC19") (pin "9") (pinfunction "I_9") (pintype "input"))
      (node (ref "R91") (pin "2") (pinfunction "2_2") (pintype "passive"))
    )
    (net (code "94") (name "Net-(IC19E-I)") (class "Default")
      (node (ref "C71") (pin "1") (pinfunction "1_1") (pintype "passive"))
      (node (ref "IC19") (pin "11") (pinfunction "I_11") (pintype "input"))
      (node (ref "R92") (pin "2") (pinfunction "2_2") (pintype "passive"))
    )
    (net (code "95") (name "Net-(IC19F-I)") (class "Default")
      (node (ref "C72") (pin "1") (pinfunction "1_1") (pintype "passive"))
      (node (ref "IC19") (pin "13") (pinfunction "I_13") (pintype "input"))
      (node (ref "R93") (pin "2") (pinfunction "2_2") (pintype "passive"))
    )
    (net (code "96") (name "Net-(IC20-EN)") (class "Default")
      (node (ref "C76") (pin "1") (pinfunction "1_1") (pintype "passive"))
      (node (ref "IC20") (pin "4") (pinfunction "EN_4") (pintype "bidirectional"))
      (node (ref "R95") (pin "1") (pinfunction "1_1") (pintype "passive"))
    )
    (net (code "97") (name "Net-(IC20-ISET)") (class "Default")
      (node (ref "IC20") (pin "3") (pinfunction "ISET_3") (pintype "bidirectional"))
      (node (ref "R100") (pin "2") (pinfunction "2_2") (pintype "passive"))
    )
    (net (code "98") (name "Net-(IC20-OUT)") (class "Default")
      (node (ref "C80") (pin "1") (pinfunction "1_1") (pintype "passive"))
      (node (ref "IC20") (pin "1") (pinfunction "OUT_1") (pintype "bidirectional"))
      (node (ref "L8") (pin "1") (pinfunction "1_1") (pintype "passive"))
    )
    (net (code "99") (name "Net-(IC21A--IN)") (class "Default")
      (node (ref "IC21") (pin "1") (pinfunction "OUT_1") (pintype "bidirectional"))
      (node (ref "IC21") (pin "2") (pinfunction "-IN_2") (pintype "input"))
      (node (ref "R104") (pin "1") (pinfunction "1_1") (pintype "passive"))
    )
    (net (code "100") (name "Net-(IC21B--IN)") (class "Default")
      (node (ref "IC21") (pin "6") (pinfunction "-IN_6") (pintype "input"))
      (node (ref "R101") (pin "2") (pinfunction "2_2") (pintype "passive"))
      (node (ref "R102") (pin "1") (pinfunction "1_1") (pintype "passive"))
      (node (ref "R103") (pin "2") (pinfunction "2_2") (pintype "passive"))
    )
    (net (code "101") (name "Net-(IC21B-OUT)") (class "Default")
      (node (ref "IC21") (pin "7") (pinfunction "OUT_7") (pintype "bidirectional"))
      (node (ref "R102") (pin "2") (pinfunction "2_2") (pintype "passive"))
      (node (ref "R105") (pin "1") (pinfunction "1_1") (pintype "passive"))
    )
    (net (code "102") (name "Net-(IC22-PC10)") (class "Default")
      (node (ref "IC22") (pin "78") (pinfunction "PC10_78") (pintype "bidirectional"))
      (node (ref "R106") (pin "2") (pinfunction "2_2") (pintype "passive"))
    )
    (net (code "103") (name "Net-(IC22-PD5)") (class "Default")
      (node (ref "IC22") (pin "86") (pinfunction "PD5_86") (pintype "bidirectional"))
      (node (ref "R109") (pin "1") (pinfunction "1_1") (pintype "passive"))
    )
    (net (code "104") (name "Net-(IC22-VCAP1)") (class "Default")
      (node (ref "C95") (pin "1") (pinfunction "1_1") (pintype "passive"))
      (node (ref "IC22") (pin "49") (pinfunction "VCAP1_49") (pintype "bidirectional"))
    )
    (net (code "105") (name "Net-(IC22-VCAP2)") (class "Default")
      (node (ref "C94") (pin "1") (pinfunction "1_1") (pintype "passive"))
      (node (ref "IC22") (pin "73") (pinfunction "VCAP2_73") (pintype "bidirectional"))
    )
    (net (code "106") (name "Net-(IC22-VDDA)") (class "Default")
      (node (ref "C84") (pin "1") (pinfunction "1_1") (pintype "passive"))
      (node (ref "C85") (pin "1") (pinfunction "1_1") (pintype "passive"))
      (node (ref "IC22") (pin "22") (pinfunction "VDDA_22") (pintype "bidirectional"))
      (node (ref "L9") (pin "1") (pinfunction "1_1") (pintype "passive"))
    )
    (net (code "107") (name "Net-(IC22-VREF+)") (class "Default")
      (node (ref "C91") (pin "1") (pinfunction "1_1") (pintype "passive"))
      (node (ref "IC22") (pin "21") (pinfunction "VREF+_21") (pintype "bidirectional"))
      (node (ref "R107") (pin "2") (pinfunction "2_2") (pintype "passive"))
    )
    (net (code "108") (name "Net-(LED1-PadA)") (class "Default")
      (node (ref "LED1") (pin "A") (pinfunction "A_A") (pintype "passive"))
      (node (ref "R11") (pin "1") (pinfunction "1_1") (pintype "passive"))
    )
    (net (code "109") (name "Net-(LED2-PadA)") (class "Default")
      (node (ref "LED2") (pin "A") (pinfunction "A_A") (pintype "passive"))
      (node (ref "R24") (pin "1") (pinfunction "1_1") (pintype "passive"))
    )
    (net (code "110") (name "Net-(LED3-PadA)") (class "Default")
      (node (ref "LED3") (pin "A") (pinfunction "A_A") (pintype "passive"))
      (node (ref "R33") (pin "1") (pinfunction "1_1") (pintype "passive"))
    )
    (net (code "111") (name "Net-(LED4-PadC)") (class "Default")
      (node (ref "LED4") (pin "C") (pinfunction "C_C") (pintype "passive"))
      (node (ref "R73") (pin "2") (pinfunction "2_2") (pintype "passive"))
    )
    (net (code "112") (name "Net-(Q1-D)") (class "Default")
      (node (ref "Q1") (pin "3") (pinfunction "D_3") (pintype "passive"))
      (node (ref "R7") (pin "2") (pinfunction "2_2") (pintype "passive"))
    )
    (net (code "113") (name "Net-(Q1-S)") (class "Default")
      (node (ref "C1") (pin "1") (pinfunction "1_1") (pintype "passive"))
      (node (ref "C2") (pin "1") (pinfunction "1_1") (pintype "passive"))
      (node (ref "Q1") (pin "2") (pinfunction "S_2") (pintype "passive"))
      (node (ref "R6") (pin "1") (pinfunction "1_1") (pintype "passive"))
    )
    (net (code "114") (name "Net-(Q2-D)") (class "Default")
      (node (ref "C5") (pin "-") (pinfunction "-_-") (pintype "passive"))
      (node (ref "C6") (pin "-") (pinfunction "-_-") (pintype "passive"))
      (node (ref "C7") (pin "-") (pinfunction "-_-") (pintype "passive"))
      (node (ref "NTC1") (pin "2") (pinfunction "2_2") (pintype "passive"))
      (node (ref "Q2") (pin "3") (pinfunction "D_3") (pintype "passive"))
    )
    (net (code "115") (name "Net-(Q3-G)") (class "Default")
      (node (ref "Q3") (pin "1") (pinfunction "G_1") (pintype "passive"))
      (node (ref "R61") (pin "2") (pinfunction "2_2") (pintype "passive"))
    )
    (net (code "116") (name "Net-(Q4-G)") (class "Default")
      (node (ref "Q4") (pin "1") (pinfunction "G_1") (pintype "passive"))
      (node (ref "R62") (pin "2") (pinfunction "2_2") (pintype "passive"))
    )
    (net (code "117") (name "Net-(Q5-G)") (class "Default")
      (node (ref "Q5") (pin "1") (pinfunction "G_1") (pintype "passive"))
      (node (ref "R72") (pin "2") (pinfunction "2_2") (pintype "passive"))
      (node (ref "R74") (pin "1") (pinfunction "1_1") (pintype "passive"))
    )
    (net (code "118") (name "Net-(Q6-D)") (class "Default")
      (node (ref "Q6") (pin "3") (pinfunction "D_3") (pintype "passive"))
      (node (ref "R103") (pin "1") (pinfunction "1_1") (pintype "passive"))
    )
    (net (code "119") (name "Net-(R3-Pad1)") (class "Default")
      (node (ref "R3") (pin "1") (pinfunction "1_1") (pintype "passive"))
      (node (ref "R4") (pin "2") (pinfunction "2_2") (pintype "passive"))
    )
    (net (code "120") (name "Net-(R4-Pad1)") (class "Default")
      (node (ref "R4") (pin "1") (pinfunction "1_1") (pintype "passive"))
      (node (ref "R5") (pin "2") (pinfunction "2_2") (pintype "passive"))
    )
    (net (code "121") (name "Net-(R10-Pad1)") (class "Default")
      (node (ref "R10") (pin "1") (pinfunction "1_1") (pintype "passive"))
      (node (ref "R11") (pin "2") (pinfunction "2_2") (pintype "passive"))
    )
    (net (code "122") (name "Net-(R10-Pad2)") (class "Default")
      (node (ref "R10") (pin "2") (pinfunction "2_2") (pintype "passive"))
      (node (ref "R9") (pin "1") (pinfunction "1_1") (pintype "passive"))
    )
    (net (code "123") (name "Net-(R35-Pad1)") (class "Default")
      (node (ref "R35") (pin "1") (pinfunction "1_1") (pintype "passive"))
      (node (ref "R36") (pin "2") (pinfunction "2_2") (pintype "passive"))
    )
    (net (code "124") (name "Net-(R38-Pad1)") (class "Default")
      (node (ref "R38") (pin "1") (pinfunction "1_1") (pintype "passive"))
      (node (ref "R39") (pin "2") (pinfunction "2_2") (pintype "passive"))
      (node (ref "R41") (pin "1") (pinfunction "1_1") (pintype "passive"))
    )
    (net (code "125") (name "Net-(R63-Pad1)") (class "Default")
      (node (ref "R63") (pin "1") (pinfunction "1_1") (pintype "passive"))
      (node (ref "R65") (pin "1") (pinfunction "1_1") (pintype "passive"))
      (node (ref "R66") (pin "2") (pinfunction "2_2") (pintype "passive"))
    )
    (net (code "126") (name "Net-(R64-Pad1)") (class "Default")
      (node (ref "R64") (pin "1") (pinfunction "1_1") (pintype "passive"))
      (node (ref "R66") (pin "1") (pinfunction "1_1") (pintype "passive"))
      (node (ref "R67") (pin "2") (pinfunction "2_2") (pintype "passive"))
    )
    (net (code "127") (name "Net-(R65-Pad2)") (class "Default")
      (node (ref "R65") (pin "2") (pinfunction "2_2") (pintype "passive"))
      (node (ref "R68") (pin "2") (pinfunction "2_2") (pintype "passive"))
    )
    (net (code "128") (name "Net-(R68-Pad1)") (class "Default")
      (node (ref "R68") (pin "1") (pinfunction "1_1") (pintype "passive"))
      (node (ref "R70") (pin "1") (pinfunction "1_1") (pintype "passive"))
    )
    (net (code "129") (name "Net-(X1A-SK)") (class "Default")
      (node (ref "F1") (pin "1") (pinfunction "1_1") (pintype "passive"))
      (node (ref "X1") (pin "1") (pinfunction "SK_1") (pintype "passive"))
    )
    (net (code "130") (name "Net-(X3B-SK)") (class "Default")
      (node (ref "L5") (pin "2") (pinfunction "2_2") (pintype "passive"))
      (node (ref "X3") (pin "2") (pinfunction "SK_2") (pintype "passive"))
    )
    (net (code "131") (name "Net-(X3C-SK)") (class "Default")
      (node (ref "L6") (pin "2") (pinfunction "2_2") (pintype "passive"))
      (node (ref "X3") (pin "3") (pinfunction "SK_3") (pintype "passive"))
    )
    (net (code "132") (name "Net-(X3D-SK)") (class "Default")
      (node (ref "L7") (pin "2") (pinfunction "2_2") (pintype "passive"))
      (node (ref "X3") (pin "4") (pinfunction "SK_4") (pintype "passive"))
    )
    (net (code "133") (name "Net-(X4A-SK)") (class "Default")
      (node (ref "K1") (pin "S") (pinfunction "S_S") (pintype "passive"))
      (node (ref "X4") (pin "1") (pinfunction "SK_1") (pintype "passive"))
    )
    (net (code "134") (name "Net-(X4B-SK)") (class "Default")
      (node (ref "K1") (pin "O") (pinfunction "O_O") (pintype "passive"))
      (node (ref "X4") (pin "2") (pinfunction "SK_2") (pintype "passive"))
    )
    (net (code "135") (name "Net-(X4C-SK)") (class "Default")
      (node (ref "K1") (pin "P") (pinfunction "P_P") (pintype "passive"))
      (node (ref "X4") (pin "3") (pinfunction "SK_3") (pintype "passive"))
    )
    (net (code "136") (name "Net-(X5A-SK)") (class "Default")
      (node (ref "R75") (pin "1") (pinfunction "1_1") (pintype "passive"))
      (node (ref "X5") (pin "1") (pinfunction "SK_1") (pintype "passive"))
    )
    (net (code "137") (name "Net-(X5C-SK)") (class "Default")
      (node (ref "R96") (pin "1") (pinfunction "1_1") (pintype "passive"))
      (node (ref "X5") (pin "11") (pinfunction "SK_11") (pintype "passive"))
    )
    (net (code "138") (name "Net-(X5D-SK)") (class "Default")
      (node (ref "C81") (pin "+") (pinfunction "+_+") (pintype "passive"))
      (node (ref "D17") (pin "C") (pinfunction "C_C") (pintype "passive"))
      (node (ref "L8") (pin "2") (pinfunction "2_2") (pintype "passive"))
      (node (ref "X5") (pin "12") (pinfunction "SK_12") (pintype "passive"))
      (node (ref "X5") (pin "8") (pinfunction "SK_8") (pintype "passive"))
    )
    (net (code "139") (name "Net-(X5E-SK)") (class "Default")
      (node (ref "R76") (pin "1") (pinfunction "1_1") (pintype "passive"))
      (node (ref "X5") (pin "2") (pinfunction "SK_2") (pintype "passive"))
    )
    (net (code "140") (name "Net-(X5F-SK)") (class "Default")
      (node (ref "R77") (pin "1") (pinfunction "1_1") (pintype "passive"))
      (node (ref "X5") (pin "3") (pinfunction "SK_3") (pintype "passive"))
    )
    (net (code "141") (name "Net-(X5G-SK)") (class "Default")
      (node (ref "R78") (pin "1") (pinfunction "1_1") (pintype "passive"))
      (node (ref "X5") (pin "4") (pinfunction "SK_4") (pintype "passive"))
    )
    (net (code "142") (name "Net-(X5H-SK)") (class "Default")
      (node (ref "R79") (pin "1") (pinfunction "1_1") (pintype "passive"))
      (node (ref "X5") (pin "5") (pinfunction "SK_5") (pintype "passive"))
    )
    (net (code "143") (name "Net-(X5L-SK)") (class "Default")
      (node (ref "C77") (pin "1") (pinfunction "1_1") (pintype "passive"))
      (node (ref "R97") (pin "2") (pinfunction "2_2") (pintype "passive"))
      (node (ref "R99") (pin "1") (pinfunction "1_1") (pintype "passive"))
      (node (ref "X5") (pin "9") (pinfunction "SK_9") (pintype "passive"))
    )
    (net (code "144") (name "OC_BOOST") (class "Default")
      (node (ref "IC10") (pin "3") (pinfunction "A1_3") (pintype "input"))
      (node (ref "IC22") (pin "53") (pinfunction "PB14_53") (pintype "bidirectional"))
    )
    (net (code "145") (name "OE") (class "Default")
      (node (ref "IC10") (pin "4") (pinfunction "A2_4") (pintype "input"))
      (node (ref "IC22") (pin "52") (pinfunction "PB13_52") (pintype "bidirectional"))
      (node (ref "R54") (pin "2") (pinfunction "2_2") (pintype "passive"))
    )
    (net (code "146") (name "OSC_IN") (class "Default")
      (node (ref "C96") (pin "1") (pinfunction "1_1") (pintype "passive"))
      (node (ref "IC22") (pin "12") (pinfunction "PH0_12") (pintype "bidirectional"))
      (node (ref "XT1") (pin "1") (pinfunction "1_1") (pintype "passive"))
    )
    (net (code "147") (name "OSC_OUT") (class "Default")
      (node (ref "IC22") (pin "13") (pinfunction "PH1_13") (pintype "bidirectional"))
      (node (ref "R110") (pin "2") (pinfunction "2_2") (pintype "passive"))
    )
    (net (code "148") (name "PE") (class "Default")
      (node (ref "CY1") (pin "2") (pinfunction "2_2") (pintype "passive"))
      (node (ref "CY2") (pin "1") (pinfunction "1_1") (pintype "passive"))
      (node (ref "H2") (pin "B3,3") (pinfunction "MOUNT_B3,3") (pintype "passive"))
      (node (ref "X1") (pin "3") (pinfunction "SK_3") (pintype "passive"))
      (node (ref "X3") (pin "1") (pinfunction "SK_1") (pintype "passive"))
    )
    (net (code "149") (name "RELAY") (class "Default")
      (node (ref "IC22") (pin "63") (pinfunction "PC6_63") (pintype "bidirectional"))
      (node (ref "R72") (pin "1") (pinfunction "1_1") (pintype "passive"))
    )
    (net (code "150") (name "SCL") (class "Default")
      (node (ref "IC22") (pin "67") (pinfunction "PA8_67") (pintype "bidirectional"))
      (node (ref "IC23") (pin "6") (pinfunction "SCL_6") (pintype "bidirectional"))
      (node (ref "R114") (pin "1") (pinfunction "1_1") (pintype "passive"))
      (node (ref "X7") (pin "4") (pinfunction "S_4") (pintype "passive"))
    )
    (net (code "151") (name "SDA") (class "Default")
      (node (ref "IC22") (pin "66") (pinfunction "PC9_66") (pintype "bidirectional"))
      (node (ref "IC23") (pin "5") (pinfunction "SDA_5") (pintype "bidirectional"))
      (node (ref "R111") (pin "1") (pinfunction "1_1") (pintype "passive"))
      (node (ref "X7") (pin "3") (pinfunction "S_3") (pintype "passive"))
    )
    (net (code "152") (name "SS_FET") (class "Default")
      (node (ref "Q2") (pin "1") (pinfunction "G_1") (pintype "passive"))
      (node (ref "R7") (pin "1") (pinfunction "1_1") (pintype "passive"))
      (node (ref "R8") (pin "2") (pinfunction "2_2") (pintype "passive"))
    )
    (net (code "153") (name "SWDCLK") (class "Default")
      (node (ref "D18") (pin "4") (pinfunction "IO3_4") (pintype "bidirectional"))
      (node (ref "IC22") (pin "76") (pinfunction "PA14_76") (pintype "bidirectional"))
      (node (ref "R113") (pin "2") (pinfunction "2_2") (pintype "passive"))
      (node (ref "X6") (pin "4") (pinfunction "4_4") (pintype "bidirectional"))
    )
    (net (code "154") (name "SWDIO") (class "Default")
      (node (ref "D18") (pin "5") (pinfunction "IO4_5") (pintype "bidirectional"))
      (node (ref "IC22") (pin "72") (pinfunction "PA13_72") (pintype "bidirectional"))
      (node (ref "R112") (pin "1") (pinfunction "1_1") (pintype "passive"))
      (node (ref "X6") (pin "2") (pinfunction "2_2") (pintype "bidirectional"))
    )
    (net (code "155") (name "SWO") (class "Default")
      (node (ref "D18") (pin "1") (pinfunction "IO1_1") (pintype "bidirectional"))
      (node (ref "IC22") (pin "89") (pinfunction "PB3_89") (pintype "bidirectional"))
      (node (ref "X6") (pin "6") (pinfunction "6_6") (pintype "bidirectional"))
    )
    (net (code "156") (name "UART_RX") (class "Default")
      (node (ref "R109") (pin "2") (pinfunction "2_2") (pintype "passive"))
      (node (ref "X7") (pin "11") (pinfunction "S_11") (pintype "passive"))
    )
    (net (code "157") (name "UART_TX") (class "Default")
      (node (ref "IC22") (pin "87") (pinfunction "PD6_87") (pintype "bidirectional"))
      (node (ref "R108") (pin "2") (pinfunction "2_2") (pintype "passive"))
      (node (ref "X7") (pin "12") (pinfunction "S_12") (pintype "passive"))
    )
    (net (code "158") (name "U_H") (class "Default")
      (node (ref "IC22") (pin "40") (pinfunction "PE9_40") (pintype "bidirectional"))
      (node (ref "R59") (pin "1") (pinfunction "1_1") (pintype "passive"))
    )
    (net (code "159") (name "U_H_ENA") (class "Default")
      (node (ref "IC13") (pin "14") (pinfunction "Y5_14") (pintype "tri_state"))
      (node (ref "R27") (pin "1") (pinfunction "1_1") (pintype "passive"))
    )
    (net (code "160") (name "U_H_FILT") (class "Default")
      (node (ref "C31") (pin "1") (pinfunction "1_1") (pintype "passive"))
      (node (ref "IC8") (pin "14") (pinfunction "HINU_14") (pintype "input"))
      (node (ref "R27") (pin "2") (pinfunction "2_2") (pintype "passive"))
    )
    (net (code "161") (name "U_H_ISO") (class "Default")
      (node (ref "IC11") (pin "11") (pinfunction "B5_11") (pintype "output"))
      (node (ref "IC13") (pin "6") (pinfunction "A5_6") (pintype "input"))
    )
    (net (code "162") (name "U_L") (class "Default")
      (node (ref "IC22") (pin "32") (pinfunction "PA7_32") (pintype "bidirectional"))
      (node (ref "R60") (pin "1") (pinfunction "1_1") (pintype "passive"))
    )
    (net (code "163") (name "U_L_ENA") (class "Default")
      (node (ref "IC13") (pin "13") (pinfunction "Y6_13") (pintype "tri_state"))
      (node (ref "R30") (pin "1") (pinfunction "1_1") (pintype "passive"))
    )
    (net (code "164") (name "U_L_FILT") (class "Default")
      (node (ref "C35") (pin "1") (pinfunction "1_1") (pintype "passive"))
      (node (ref "IC8") (pin "16") (pinfunction "~{LINU}_16") (pintype "input"))
      (node (ref "R30") (pin "2") (pinfunction "2_2") (pintype "passive"))
    )
    (net (code "165") (name "U_L_ISO") (class "Default")
      (node (ref "IC11") (pin "10") (pinfunction "B6_10") (pintype "output"))
      (node (ref "IC13") (pin "7") (pinfunction "A6_7") (pintype "input"))
    )
    (net (code "166") (name "U_OUT") (class "Default")
      (node (ref "C39") (pin "2") (pinfunction "2_2") (pintype "passive"))
      (node (ref "IC8") (pin "19") (pinfunction "U_19") (pintype "output"))
      (node (ref "L5") (pin "1") (pinfunction "1_1") (pintype "passive"))
    )
    (net (code "167") (name "VBUS") (class "Default")
      (node (ref "C45") (pin "1") (pinfunction "1_1") (pintype "passive"))
      (node (ref "C5") (pin "+") (pinfunction "+_+") (pintype "passive"))
      (node (ref "C6") (pin "+") (pinfunction "+_+") (pintype "passive"))
      (node (ref "C7") (pin "+") (pinfunction "+_+") (pintype "passive"))
      (node (ref "D2") (pin "C") (pinfunction "C_C") (pintype "passive"))
      (node (ref "D4") (pin "C") (pinfunction "C_C") (pintype "passive"))
      (node (ref "D6") (pin "A") (pinfunction "A_A") (pintype "passive"))
      (node (ref "IC8") (pin "18") (pinfunction "P_18") (pintype "input"))
      (node (ref "R70") (pin "2") (pinfunction "2_2") (pintype "passive"))
      (node (ref "R9") (pin "2") (pinfunction "2_2") (pintype "passive"))
      (node (ref "TP1") (pin "TP") (pinfunction "TP_TP") (pintype "input"))
    )
    (net (code "168") (name "VCC") (class "Default")
      (node (ref "C42") (pin "1") (pinfunction "1_1") (pintype "passive"))
      (node (ref "C43") (pin "1") (pinfunction "1_1") (pintype "passive"))
      (node (ref "C44") (pin "1") (pinfunction "1_1") (pintype "passive"))
      (node (ref "D13") (pin "C") (pinfunction "C_C") (pintype "passive"))
      (node (ref "IC8") (pin "13") (pinfunction "VCCU_13") (pintype "input"))
      (node (ref "IC8") (pin "3") (pinfunction "VCCW_3") (pintype "input"))
      (node (ref "IC8") (pin "9") (pinfunction "VCCV_9") (pintype "input"))
      (node (ref "R34") (pin "2") (pinfunction "2_2") (pintype "passive"))
    )
    (net (code "169") (name "VIN_ADC") (class "Default")
      (node (ref "C83") (pin "1") (pinfunction "1_1") (pintype "passive"))
      (node (ref "IC22") (pin "24") (pinfunction "PA1_24") (pintype "bidirectional"))
      (node (ref "R105") (pin "2") (pinfunction "2_2") (pintype "passive"))
    )
    (net (code "170") (name "VREF") (class "Default")
      (node (ref "IC6") (pin "2") (pinfunction "VOUT_2") (pintype "input"))
      (node (ref "R107") (pin "1") (pinfunction "1_1") (pintype "passive"))
    )
    (net (code "171") (name "V_BUS_MON") (class "Default")
      (node (ref "C47") (pin "1") (pinfunction "1_1") (pintype "passive"))
      (node (ref "IC22") (pin "29") (pinfunction "PA4_29") (pintype "bidirectional"))
      (node (ref "R47") (pin "2") (pinfunction "2_2") (pintype "passive"))
    )
    (net (code "172") (name "V_H") (class "Default")
      (node (ref "IC22") (pin "42") (pinfunction "PE11_42") (pintype "bidirectional"))
      (node (ref "R57") (pin "1") (pinfunction "1_1") (pintype "passive"))
    )
    (net (code "173") (name "V_H_ENA") (class "Default")
      (node (ref "IC13") (pin "16") (pinfunction "Y3_16") (pintype "tri_state"))
      (node (ref "R28") (pin "1") (pinfunction "1_1") (pintype "passive"))
    )
    (net (code "174") (name "V_H_FILT") (class "Default")
      (node (ref "C30") (pin "1") (pinfunction "1_1") (pintype "passive"))
      (node (ref "IC8") (pin "10") (pinfunction "HINV_10") (pintype "input"))
      (node (ref "R28") (pin "2") (pinfunction "2_2") (pintype "passive"))
    )
    (net (code "175") (name "V_H_ISO") (class "Default")
      (node (ref "IC11") (pin "13") (pinfunction "B3_13") (pintype "output"))
      (node (ref "IC13") (pin "4") (pinfunction "A3_4") (pintype "input"))
    )
    (net (code "176") (name "V_L") (class "Default")
      (node (ref "IC22") (pin "35") (pinfunction "PB0_35") (pintype "bidirectional"))
      (node (ref "R58") (pin "1") (pinfunction "1_1") (pintype "passive"))
    )
    (net (code "177") (name "V_L_ENA") (class "Default")
      (node (ref "IC13") (pin "15") (pinfunction "Y4_15") (pintype "tri_state"))
      (node (ref "R31") (pin "1") (pinfunction "1_1") (pintype "passive"))
    )
    (net (code "178") (name "V_L_FILT") (class "Default")
      (node (ref "C34") (pin "1") (pinfunction "1_1") (pintype "passive"))
      (node (ref "IC8") (pin "11") (pinfunction "~{LINV}_11") (pintype "input"))
      (node (ref "R31") (pin "2") (pinfunction "2_2") (pintype "passive"))
    )
    (net (code "179") (name "V_L_ISO") (class "Default")
      (node (ref "IC11") (pin "12") (pinfunction "B4_12") (pintype "output"))
      (node (ref "IC13") (pin "5") (pinfunction "A4_5") (pintype "input"))
    )
    (net (code "180") (name "V_OUT") (class "Default")
      (node (ref "C40") (pin "2") (pinfunction "2_2") (pintype "passive"))
      (node (ref "IC8") (pin "22") (pinfunction "V_22") (pintype "output"))
      (node (ref "L6") (pin "1") (pinfunction "1_1") (pintype "passive"))
    )
    (net (code "181") (name "W_H") (class "Default")
      (node (ref "IC22") (pin "44") (pinfunction "PE13_44") (pintype "bidirectional"))
      (node (ref "R55") (pin "1") (pinfunction "1_1") (pintype "passive"))
    )
    (net (code "182") (name "W_H_ENA") (class "Default")
      (node (ref "IC13") (pin "18") (pinfunction "Y1_18") (pintype "tri_state"))
      (node (ref "R29") (pin "1") (pinfunction "1_1") (pintype "passive"))
    )
    (net (code "183") (name "W_H_FILT") (class "Default")
      (node (ref "C28") (pin "1") (pinfunction "1_1") (pintype "passive"))
      (node (ref "IC8") (pin "4") (pinfunction "HINW_4") (pintype "input"))
      (node (ref "R29") (pin "2") (pinfunction "2_2") (pintype "passive"))
    )
    (net (code "184") (name "W_H_ISO") (class "Default")
      (node (ref "IC11") (pin "15") (pinfunction "B1_15") (pintype "output"))
      (node (ref "IC13") (pin "2") (pinfunction "A1_2") (pintype "input"))
    )
    (net (code "185") (name "W_L") (class "Default")
      (node (ref "IC22") (pin "43") (pinfunction "PE12_43") (pintype "bidirectional"))
      (node (ref "R56") (pin "1") (pinfunction "1_1") (pintype "passive"))
    )
    (net (code "186") (name "W_L_ENA") (class "Default")
      (node (ref "IC13") (pin "17") (pinfunction "Y2_17") (pintype "tri_state"))
      (node (ref "R32") (pin "1") (pinfunction "1_1") (pintype "passive"))
    )
    (net (code "187") (name "W_L_FILT") (class "Default")
      (node (ref "C32") (pin "1") (pinfunction "1_1") (pintype "passive"))
      (node (ref "IC8") (pin "5") (pinfunction "~{LINW}_5") (pintype "input"))
      (node (ref "R32") (pin "2") (pinfunction "2_2") (pintype "passive"))
    )
    (net (code "188") (name "W_L_ISO") (class "Default")
      (node (ref "IC11") (pin "14") (pinfunction "B2_14") (pintype "output"))
      (node (ref "IC13") (pin "3") (pinfunction "A2_3") (pintype "input"))
    )
    (net (code "189") (name "W_OUT") (class "Default")
      (node (ref "C41") (pin "2") (pinfunction "2_2") (pintype "passive"))
      (node (ref "IC8") (pin "25") (pinfunction "W_25") (pintype "output"))
      (node (ref "L7") (pin "1") (pinfunction "1_1") (pintype "passive"))
    )
    (net (code "190") (name "unconnected-(H1-MOUNT-PadB3,3)") (class "Default")
      (node (ref "H1") (pin "B3,3") (pinfunction "MOUNT_B3,3") (pintype "passive"))
    )
    (net (code "191") (name "unconnected-(H3-MOUNT-PadB3,3)") (class "Default")
      (node (ref "H3") (pin "B3,3") (pinfunction "MOUNT_B3,3") (pintype "passive"))
    )
    (net (code "192") (name "unconnected-(H4-MOUNT-PadB3,3)") (class "Default")
      (node (ref "H4") (pin "B3,3") (pinfunction "MOUNT_B3,3") (pintype "passive"))
    )
    (net (code "193") (name "unconnected-(H5-MOUNT-PadB3,3)") (class "Default")
      (node (ref "H5") (pin "B3,3") (pinfunction "MOUNT_B3,3") (pintype "passive"))
    )
    (net (code "194") (name "unconnected-(H6-MOUNT-PadB3,3)") (class "Default")
      (node (ref "H6") (pin "B3,3") (pinfunction "MOUNT_B3,3") (pintype "passive"))
    )
    (net (code "195") (name "unconnected-(H7-MOUNT-PadB3,3)") (class "Default")
      (node (ref "H7") (pin "B3,3") (pinfunction "MOUNT_B3,3") (pintype "passive"))
    )
    (net (code "196") (name "unconnected-(H8-MOUNT-PadB3,3)") (class "Default")
      (node (ref "H8") (pin "B3,3") (pinfunction "MOUNT_B3,3") (pintype "passive"))
    )
    (net (code "197") (name "unconnected-(IC8-~{SD{slash}OD}-Pad15)") (class "Default")
      (node (ref "IC8") (pin "15") (pinfunction "~{SD/OD}_15") (pintype "bidirectional"))
    )
    (net (code "198") (name "unconnected-(IC13A-Y7-Pad12)") (class "Default")
      (node (ref "IC13") (pin "12") (pinfunction "Y7_12") (pintype "tri_state"))
    )
    (net (code "199") (name "unconnected-(IC13A-Y8-Pad11)") (class "Default")
      (node (ref "IC13") (pin "11") (pinfunction "Y8_11") (pintype "tri_state"))
    )
    (net (code "200") (name "unconnected-(IC19A-O-Pad2)") (class "Default")
      (node (ref "IC19") (pin "2") (pinfunction "O_2") (pintype "output"))
    )
    (net (code "201") (name "unconnected-(IC22-PA0-Pad23)") (class "Default")
      (node (ref "IC22") (pin "23") (pinfunction "PA0_23") (pintype "bidirectional"))
    )
    (net (code "202") (name "unconnected-(IC22-PA5-Pad30)") (class "Default")
      (node (ref "IC22") (pin "30") (pinfunction "PA5_30") (pintype "bidirectional"))
    )
    (net (code "203") (name "unconnected-(IC22-PA9-Pad68)") (class "Default")
      (node (ref "IC22") (pin "68") (pinfunction "PA9_68") (pintype "bidirectional"))
    )
    (net (code "204") (name "unconnected-(IC22-PA10-Pad69)") (class "Default")
      (node (ref "IC22") (pin "69") (pinfunction "PA10_69") (pintype "bidirectional"))
    )
    (net (code "205") (name "unconnected-(IC22-PA11-Pad70)") (class "Default")
      (node (ref "IC22") (pin "70") (pinfunction "PA11_70") (pintype "bidirectional"))
    )
    (net (code "206") (name "unconnected-(IC22-PA12-Pad71)") (class "Default")
      (node (ref "IC22") (pin "71") (pinfunction "PA12_71") (pintype "bidirectional"))
    )
    (net (code "207") (name "unconnected-(IC22-PB1-Pad36)") (class "Default")
      (node (ref "IC22") (pin "36") (pinfunction "PB1_36") (pintype "bidirectional"))
    )
    (net (code "208") (name "unconnected-(IC22-PB2-Pad37)") (class "Default")
      (node (ref "IC22") (pin "37") (pinfunction "PB2_37") (pintype "bidirectional"))
    )
    (net (code "209") (name "unconnected-(IC22-PB4-Pad90)") (class "Default")
      (node (ref "IC22") (pin "90") (pinfunction "PB4_90") (pintype "bidirectional"))
    )
    (net (code "210") (name "unconnected-(IC22-PB5-Pad91)") (class "Default")
      (node (ref "IC22") (pin "91") (pinfunction "PB5_91") (pintype "bidirectional"))
    )
    (net (code "211") (name "unconnected-(IC22-PB10-Pad47)") (class "Default")
      (node (ref "IC22") (pin "47") (pinfunction "PB10_47") (pintype "bidirectional"))
    )
    (net (code "212") (name "unconnected-(IC22-PB11-Pad48)") (class "Default")
      (node (ref "IC22") (pin "48") (pinfunction "PB11_48") (pintype "bidirectional"))
    )
    (net (code "213") (name "unconnected-(IC22-PB15-Pad54)") (class "Default")
      (node (ref "IC22") (pin "54") (pinfunction "PB15_54") (pintype "bidirectional"))
    )
    (net (code "214") (name "unconnected-(IC22-PC0-Pad15)") (class "Default")
      (node (ref "IC22") (pin "15") (pinfunction "PC0_15") (pintype "bidirectional"))
    )
    (net (code "215") (name "unconnected-(IC22-PC1-Pad16)") (class "Default")
      (node (ref "IC22") (pin "16") (pinfunction "PC1_16") (pintype "bidirectional"))
    )
    (net (code "216") (name "unconnected-(IC22-PC3-Pad18)") (class "Default")
      (node (ref "IC22") (pin "18") (pinfunction "PC3_18") (pintype "bidirectional"))
    )
    (net (code "217") (name "unconnected-(IC22-PC4-Pad33)") (class "Default")
      (node (ref "IC22") (pin "33") (pinfunction "PC4_33") (pintype "bidirectional"))
    )
    (net (code "218") (name "unconnected-(IC22-PC5-Pad34)") (class "Default")
      (node (ref "IC22") (pin "34") (pinfunction "PC5_34") (pintype "bidirectional"))
    )
    (net (code "219") (name "unconnected-(IC22-PC7-Pad64)") (class "Default")
      (node (ref "IC22") (pin "64") (pinfunction "PC7_64") (pintype "bidirectional"))
    )
    (net (code "220") (name "unconnected-(IC22-PC8-Pad65)") (class "Default")
      (node (ref "IC22") (pin "65") (pinfunction "PC8_65") (pintype "bidirectional"))
    )
    (net (code "221") (name "unconnected-(IC22-PC13-Pad7)") (class "Default")
      (node (ref "IC22") (pin "7") (pinfunction "PC13_7") (pintype "bidirectional"))
    )
    (net (code "222") (name "unconnected-(IC22-PC14-Pad8)") (class "Default")
      (node (ref "IC22") (pin "8") (pinfunction "PC14_8") (pintype "bidirectional"))
    )
    (net (code "223") (name "unconnected-(IC22-PC15-Pad9)") (class "Default")
      (node (ref "IC22") (pin "9") (pinfunction "PC15_9") (pintype "bidirectional"))
    )
    (net (code "224") (name "unconnected-(IC22-PD4-Pad85)") (class "Default")
      (node (ref "IC22") (pin "85") (pinfunction "PD4_85") (pintype "bidirectional"))
    )
    (net (code "225") (name "unconnected-(IC22-PD7-Pad88)") (class "Default")
      (node (ref "IC22") (pin "88") (pinfunction "PD7_88") (pintype "bidirectional"))
    )
    (net (code "226") (name "unconnected-(IC22-PD8-Pad55)") (class "Default")
      (node (ref "IC22") (pin "55") (pinfunction "PD8_55") (pintype "bidirectional"))
    )
    (net (code "227") (name "unconnected-(IC22-PD9-Pad56)") (class "Default")
      (node (ref "IC22") (pin "56") (pinfunction "PD9_56") (pintype "bidirectional"))
    )
    (net (code "228") (name "unconnected-(IC22-PD10-Pad57)") (class "Default")
      (node (ref "IC22") (pin "57") (pinfunction "PD10_57") (pintype "bidirectional"))
    )
    (net (code "229") (name "unconnected-(IC22-PD11-Pad58)") (class "Default")
      (node (ref "IC22") (pin "58") (pinfunction "PD11_58") (pintype "bidirectional"))
    )
    (net (code "230") (name "unconnected-(IC22-PD12-Pad59)") (class "Default")
      (node (ref "IC22") (pin "59") (pinfunction "PD12_59") (pintype "bidirectional"))
    )
    (net (code "231") (name "unconnected-(IC22-PD13-Pad60)") (class "Default")
      (node (ref "IC22") (pin "60") (pinfunction "PD13_60") (pintype "bidirectional"))
    )
    (net (code "232") (name "unconnected-(IC22-PD14-Pad61)") (class "Default")
      (node (ref "IC22") (pin "61") (pinfunction "PD14_61") (pintype "bidirectional"))
    )
    (net (code "233") (name "unconnected-(IC22-PD15-Pad62)") (class "Default")
      (node (ref "IC22") (pin "62") (pinfunction "PD15_62") (pintype "bidirectional"))
    )
    (net (code "234") (name "unconnected-(IC22-PE0-Pad97)") (class "Default")
      (node (ref "IC22") (pin "97") (pinfunction "PE0_97") (pintype "bidirectional"))
    )
    (net (code "235") (name "unconnected-(IC22-PE1-Pad98)") (class "Default")
      (node (ref "IC22") (pin "98") (pinfunction "PE1_98") (pintype "bidirectional"))
    )
    (net (code "236") (name "unconnected-(IC22-PE2-Pad1)") (class "Default")
      (node (ref "IC22") (pin "1") (pinfunction "PE2_1") (pintype "bidirectional"))
    )
    (net (code "237") (name "unconnected-(IC22-PE3-Pad2)") (class "Default")
      (node (ref "IC22") (pin "2") (pinfunction "PE3_2") (pintype "bidirectional"))
    )
    (net (code "238") (name "unconnected-(IC22-PE4-Pad3)") (class "Default")
      (node (ref "IC22") (pin "3") (pinfunction "PE4_3") (pintype "bidirectional"))
    )
    (net (code "239") (name "unconnected-(IC22-PE5-Pad4)") (class "Default")
      (node (ref "IC22") (pin "4") (pinfunction "PE5_4") (pintype "bidirectional"))
    )
    (net (code "240") (name "unconnected-(IC22-PE6-Pad5)") (class "Default")
      (node (ref "IC22") (pin "5") (pinfunction "PE6_5") (pintype "bidirectional"))
    )
    (net (code "241") (name "unconnected-(IC22-PE7-Pad38)") (class "Default")
      (node (ref "IC22") (pin "38") (pinfunction "PE7_38") (pintype "bidirectional"))
    )
    (net (code "242") (name "unconnected-(IC22-PE8-Pad39)") (class "Default")
      (node (ref "IC22") (pin "39") (pinfunction "PE8_39") (pintype "bidirectional"))
    )
    (net (code "243") (name "unconnected-(IC22-PE10-Pad41)") (class "Default")
      (node (ref "IC22") (pin "41") (pinfunction "PE10_41") (pintype "bidirectional"))
    )
    (net (code "244") (name "unconnected-(IC22-PE14-Pad45)") (class "Default")
      (node (ref "IC22") (pin "45") (pinfunction "PE14_45") (pintype "bidirectional"))
    )
    (net (code "245") (name "unconnected-(IC22-PE15-Pad46)") (class "Default")
      (node (ref "IC22") (pin "46") (pinfunction "PE15_46") (pintype "bidirectional"))
    )
    (net (code "246") (name "unconnected-(X6-Pad7)") (class "Default")
      (node (ref "X6") (pin "7") (pinfunction "7_7") (pintype "bidirectional"))
    )
    (net (code "247") (name "unconnected-(X6-Pad8)") (class "Default")
      (node (ref "X6") (pin "8") (pinfunction "8_8") (pintype "bidirectional"))
    )
    (net (code "248") (name "unconnected-(X6-Pad9)") (class "Default")
      (node (ref "X6") (pin "9") (pinfunction "9_9") (pintype "bidirectional"))
    )
    (net (code "249") (name "~{DISP_CS}") (class "Default")
      (node (ref "IC22") (pin "77") (pinfunction "PA15_77") (pintype "bidirectional"))
      (node (ref "X7") (pin "5") (pinfunction "S_5") (pintype "passive"))
    )
    (net (code "250") (name "~{EMERGENCY_ISO}") (class "Default")
      (node (ref "IC10") (pin "12") (pinfunction "B3_12") (pintype "input"))
      (node (ref "IC8") (pin "2") (pinfunction "~{SD/OD_2}_2") (pintype "bidirectional"))
      (node (ref "R40") (pin "1") (pinfunction "1_1") (pintype "passive"))
    )
    (net (code "251") (name "~{EMERGENCY}") (class "Default")
      (node (ref "IC10") (pin "5") (pinfunction "A3_5") (pintype "output"))
      (node (ref "IC22") (pin "51") (pinfunction "PB12_51") (pintype "bidirectional"))
    )
    (net (code "252") (name "~{INT}") (class "Default")
      (node (ref "IC22") (pin "96") (pinfunction "PB9_96") (pintype "bidirectional"))
      (node (ref "X7") (pin "18") (pinfunction "S_18") (pintype "passive"))
    )
    (net (code "253") (name "~{OC_BOOST}") (class "Default")
      (node (ref "Q3") (pin "3") (pinfunction "D_3") (pintype "passive"))
      (node (ref "R42") (pin "1") (pinfunction "1_1") (pintype "passive"))
    )
    (net (code "254") (name "~{OE_ISO}") (class "Default")
      (node (ref "IC13") (pin "1") (pinfunction "G1_1") (pintype "input"))
      (node (ref "Q4") (pin "3") (pinfunction "D_3") (pintype "passive"))
      (node (ref "R69") (pin "1") (pinfunction "1_1") (pintype "passive"))
    )
  )
)
